# RastoBot-r1.net
KiCad netlist of a schematic drawn in EAGLE
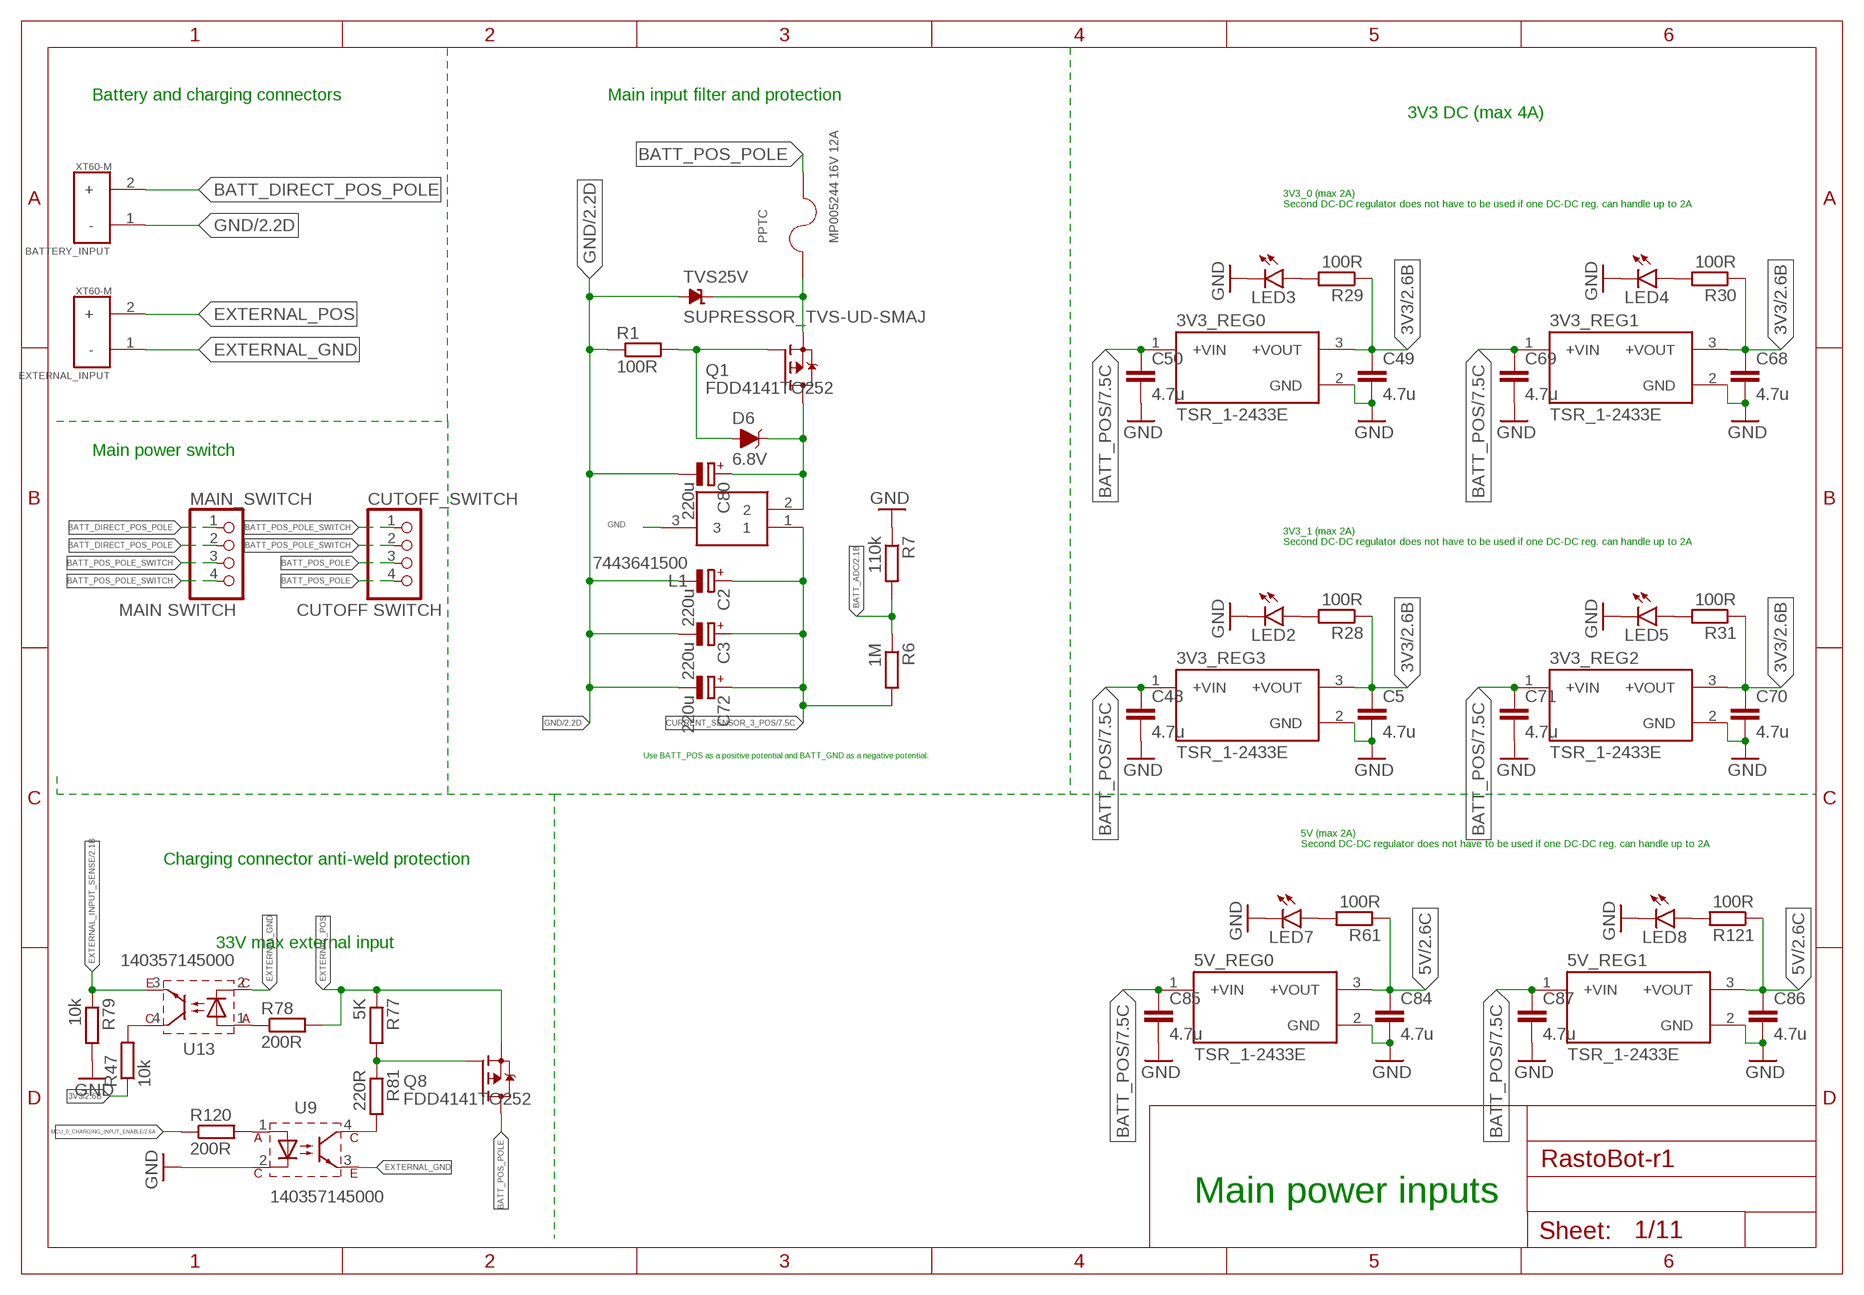
[diagram p0: schematic, sheet 1]
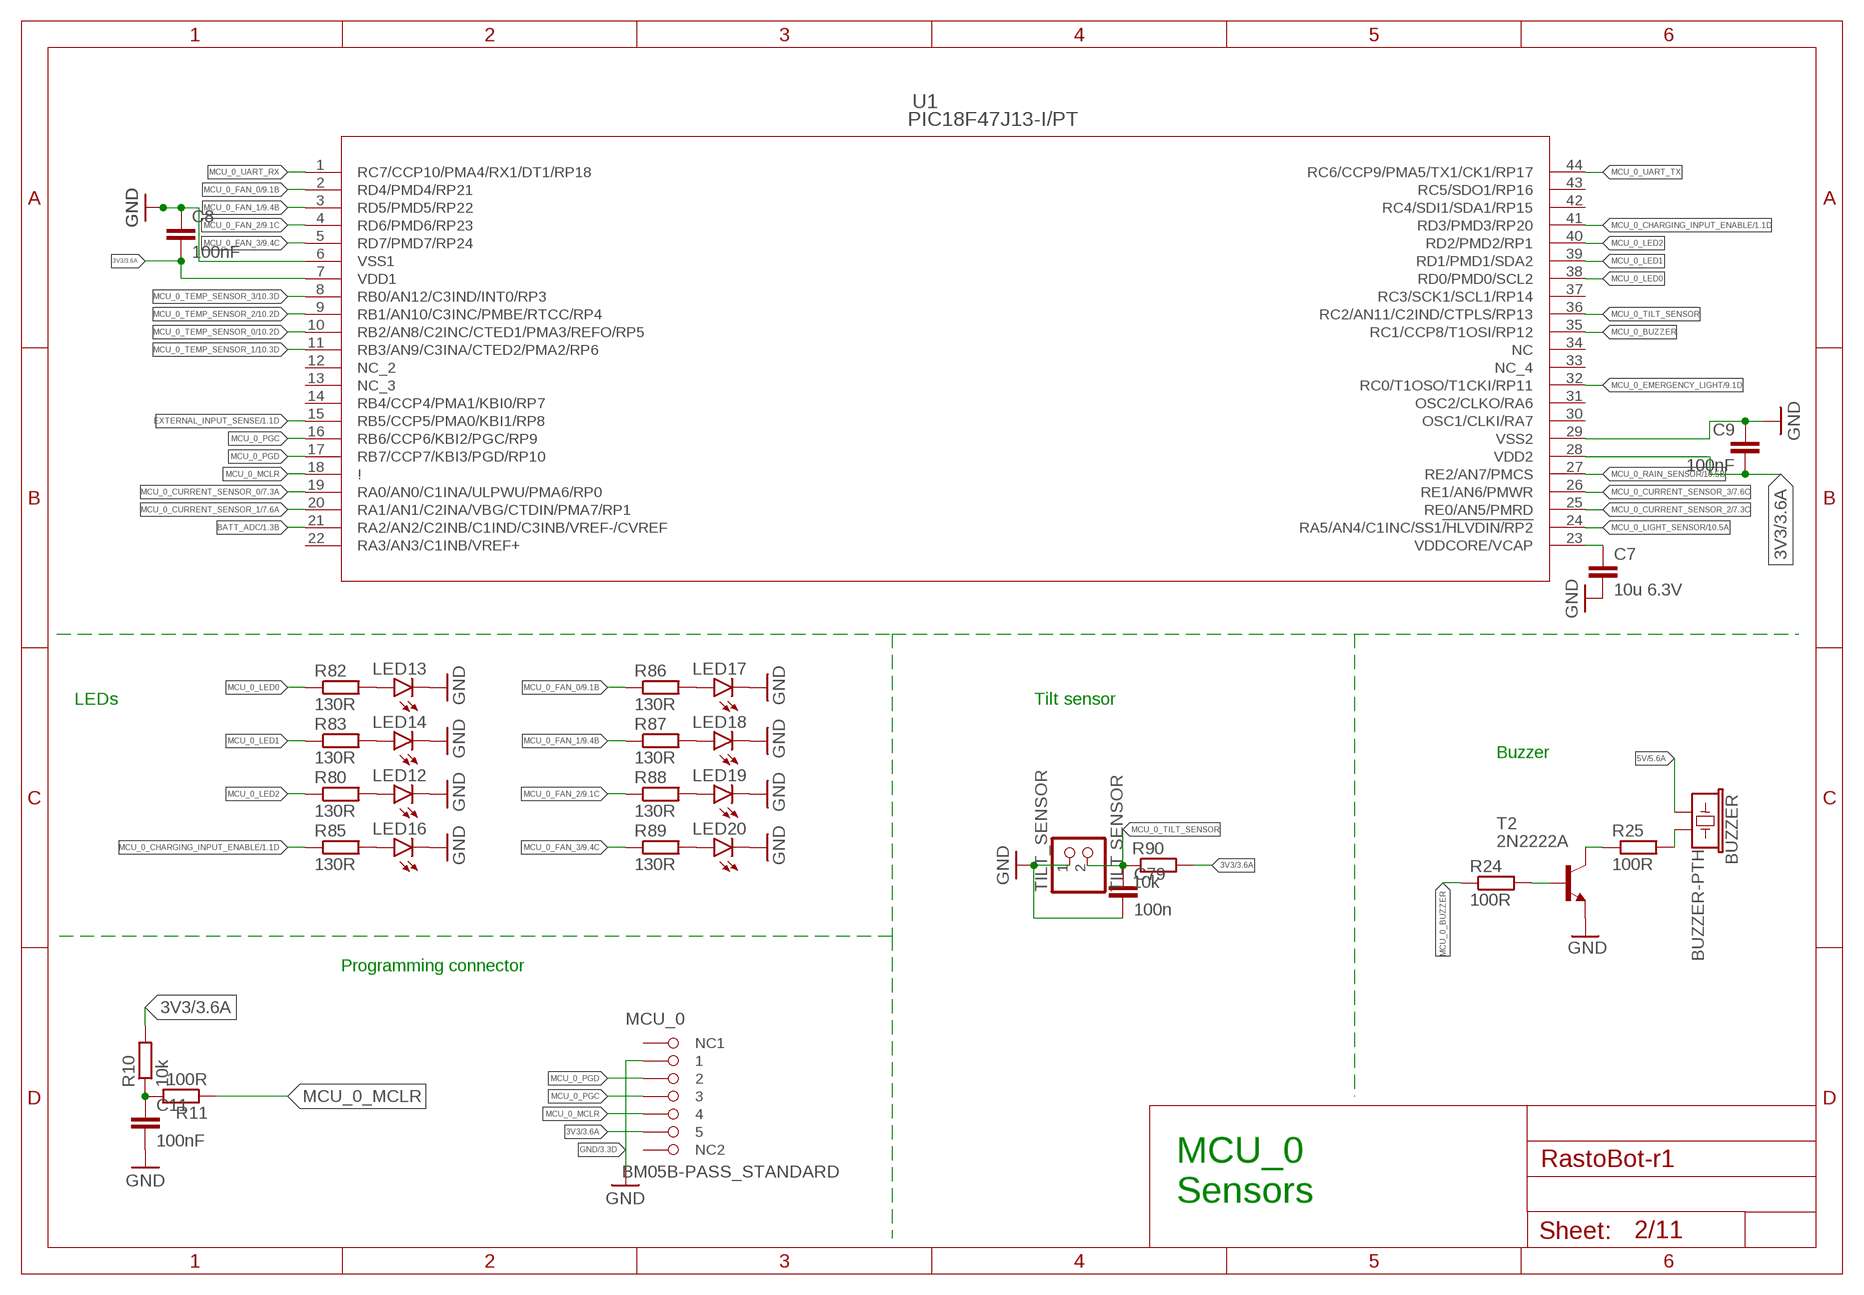
[diagram p1: schematic, sheet 2]
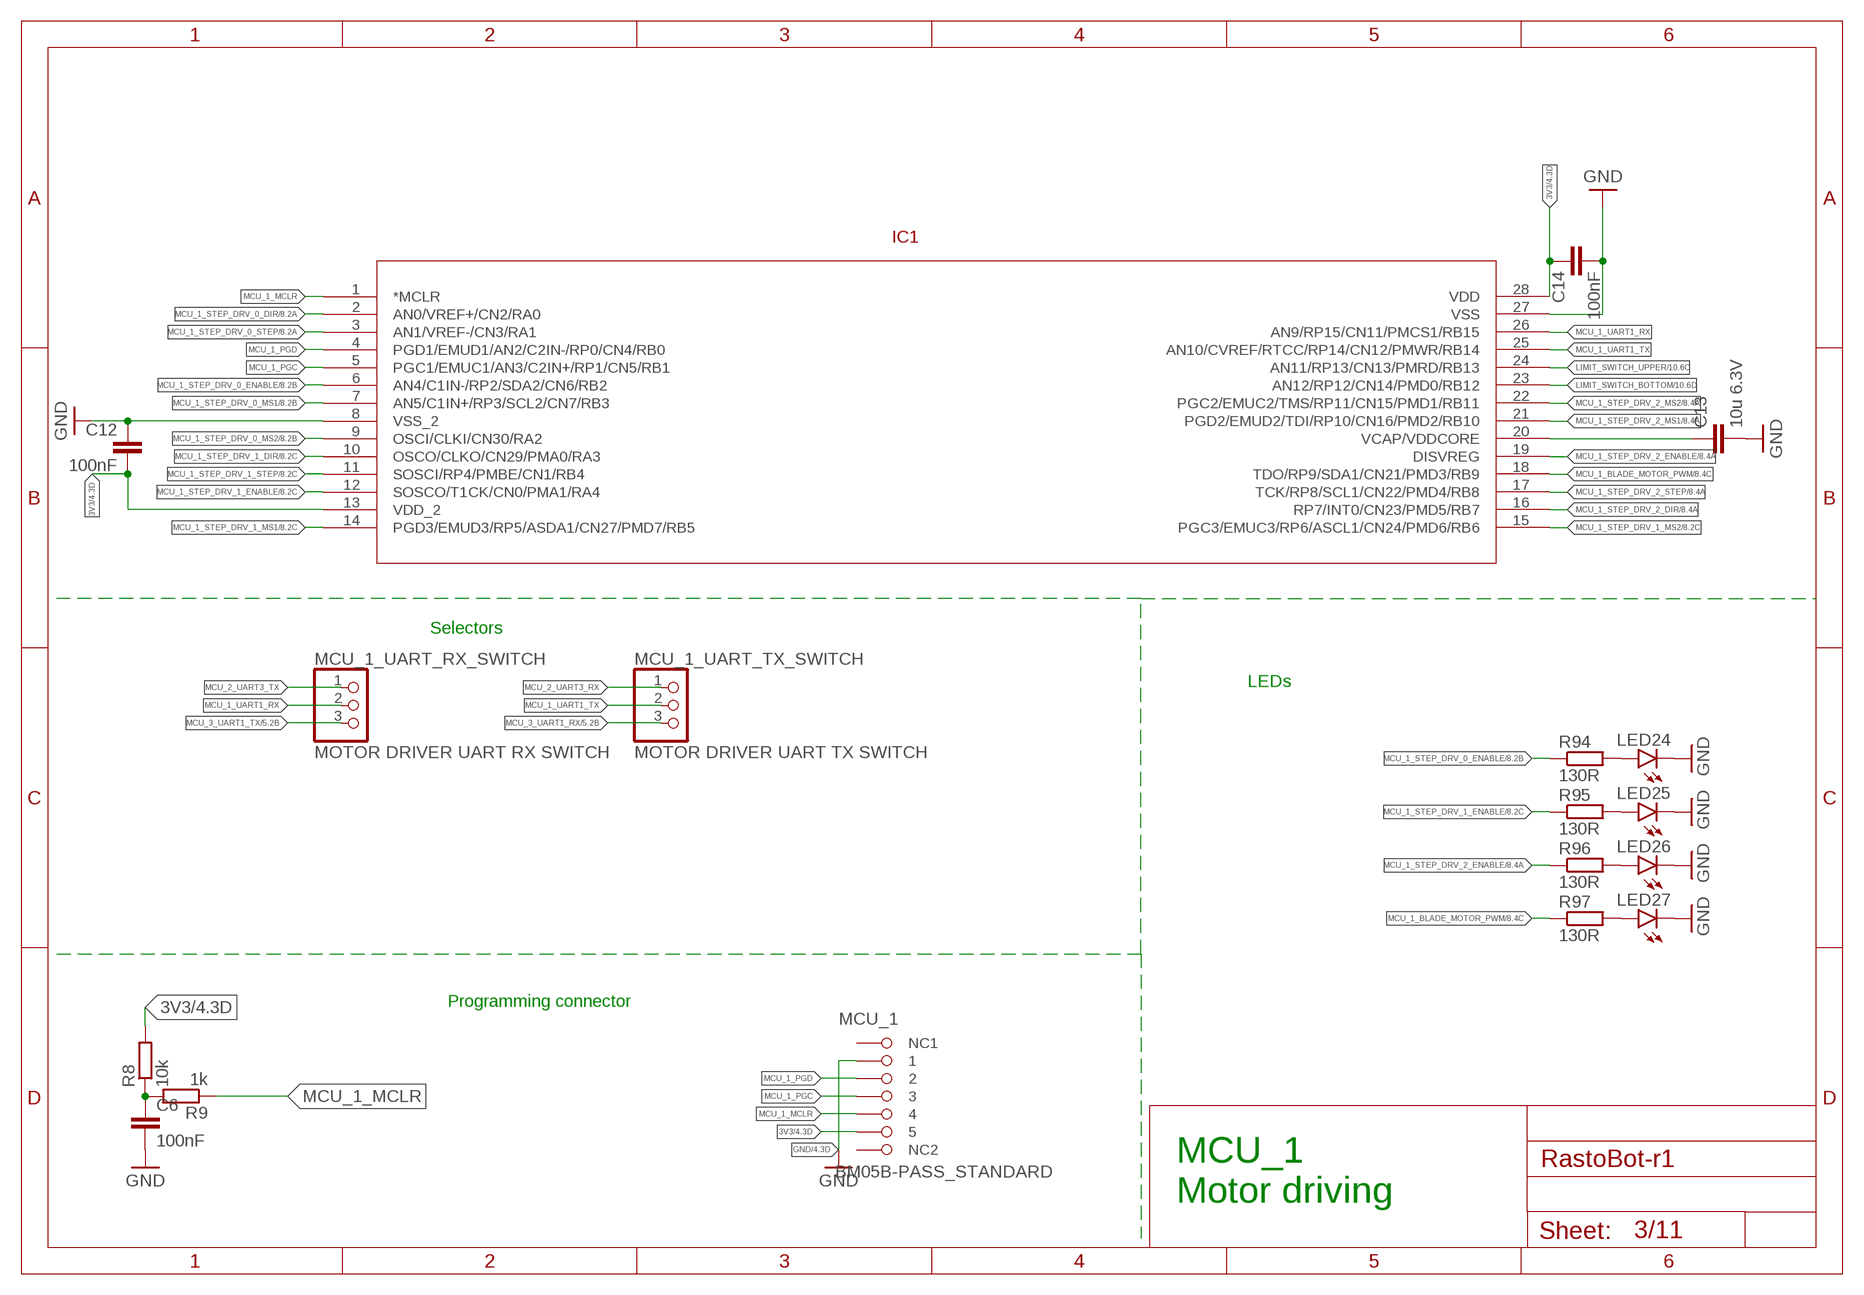
[diagram p2: schematic, sheet 3]
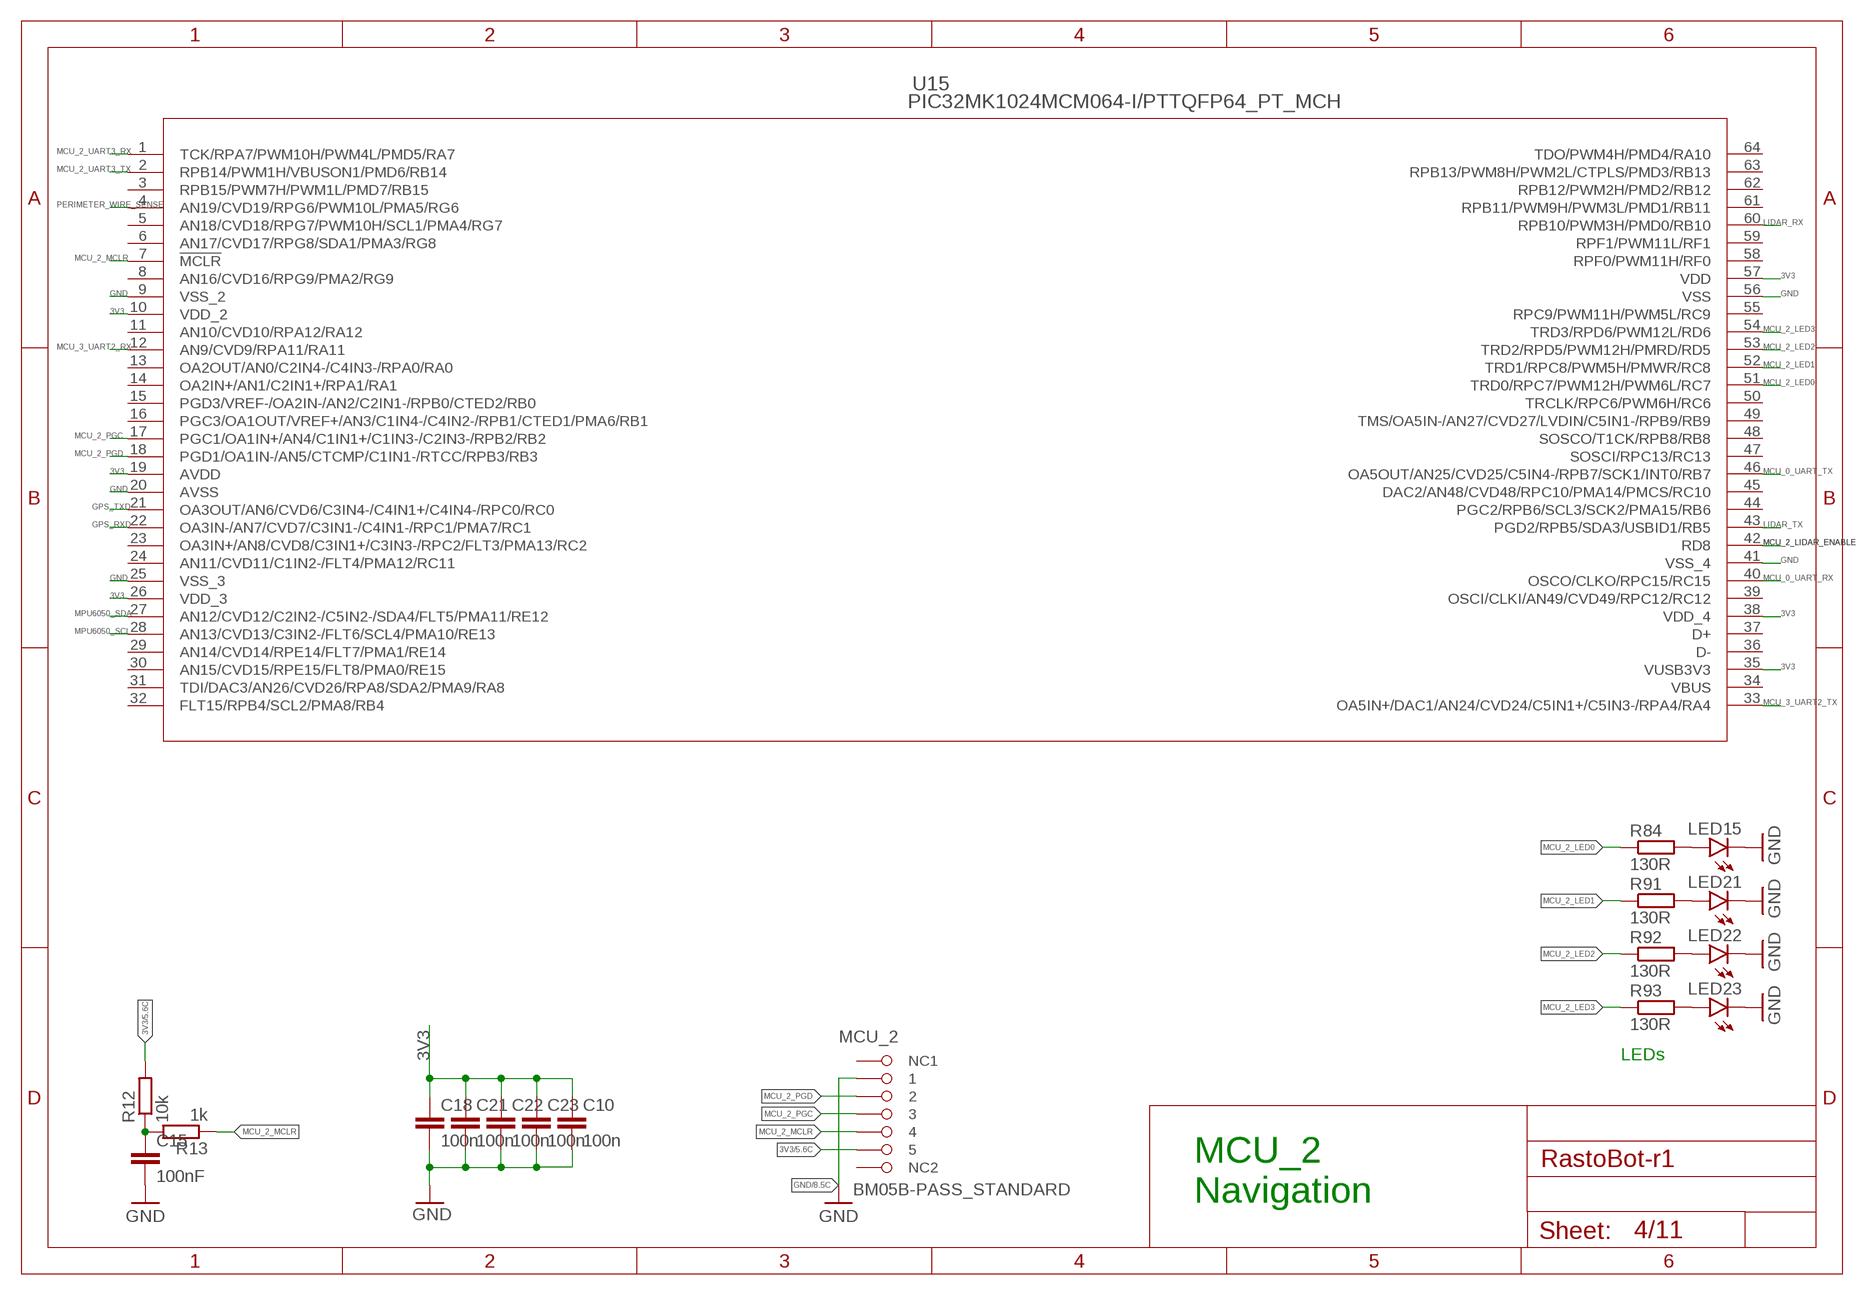
[diagram p3: schematic, sheet 4]
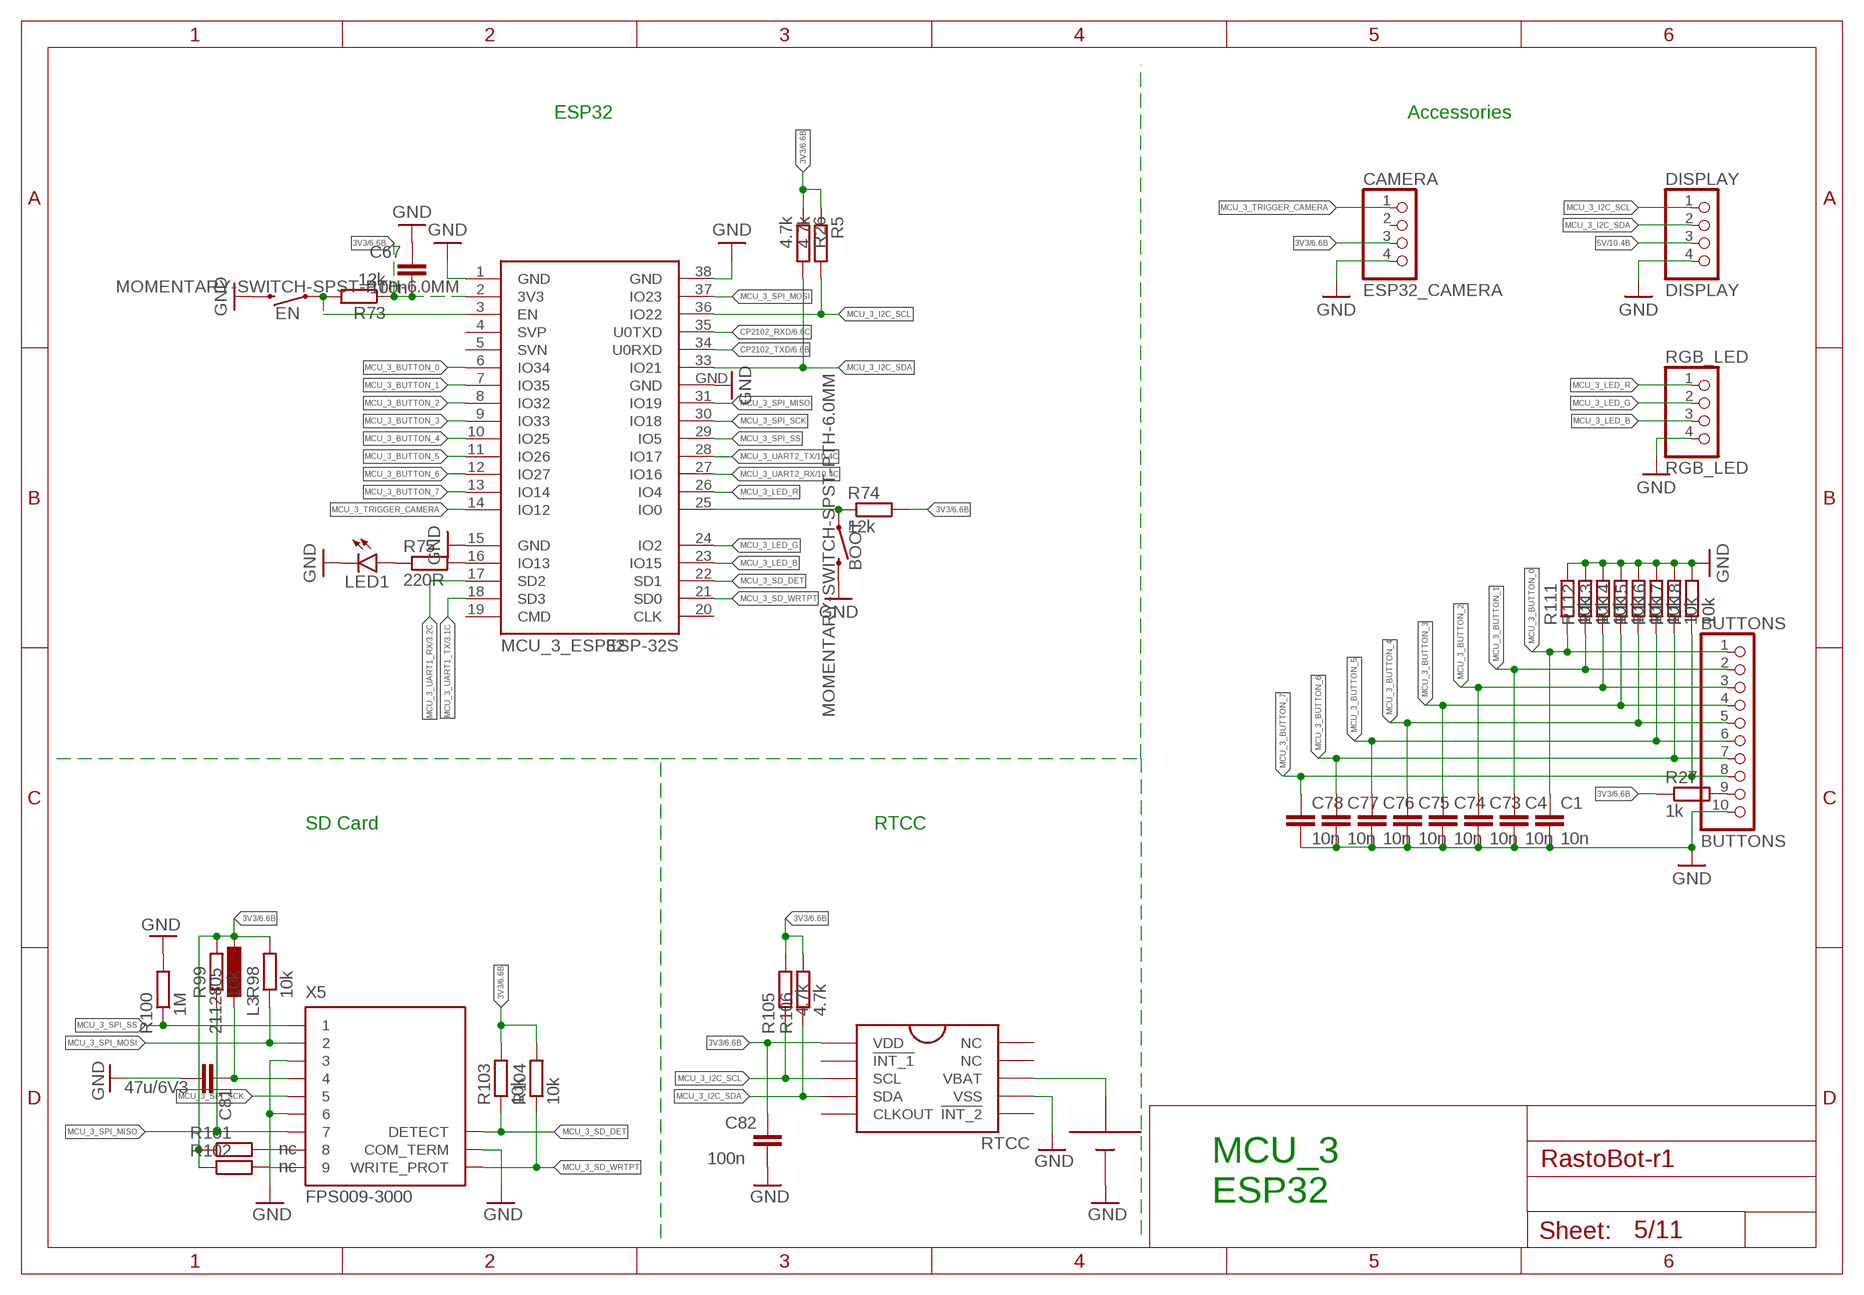
[diagram p4: schematic, sheet 5]
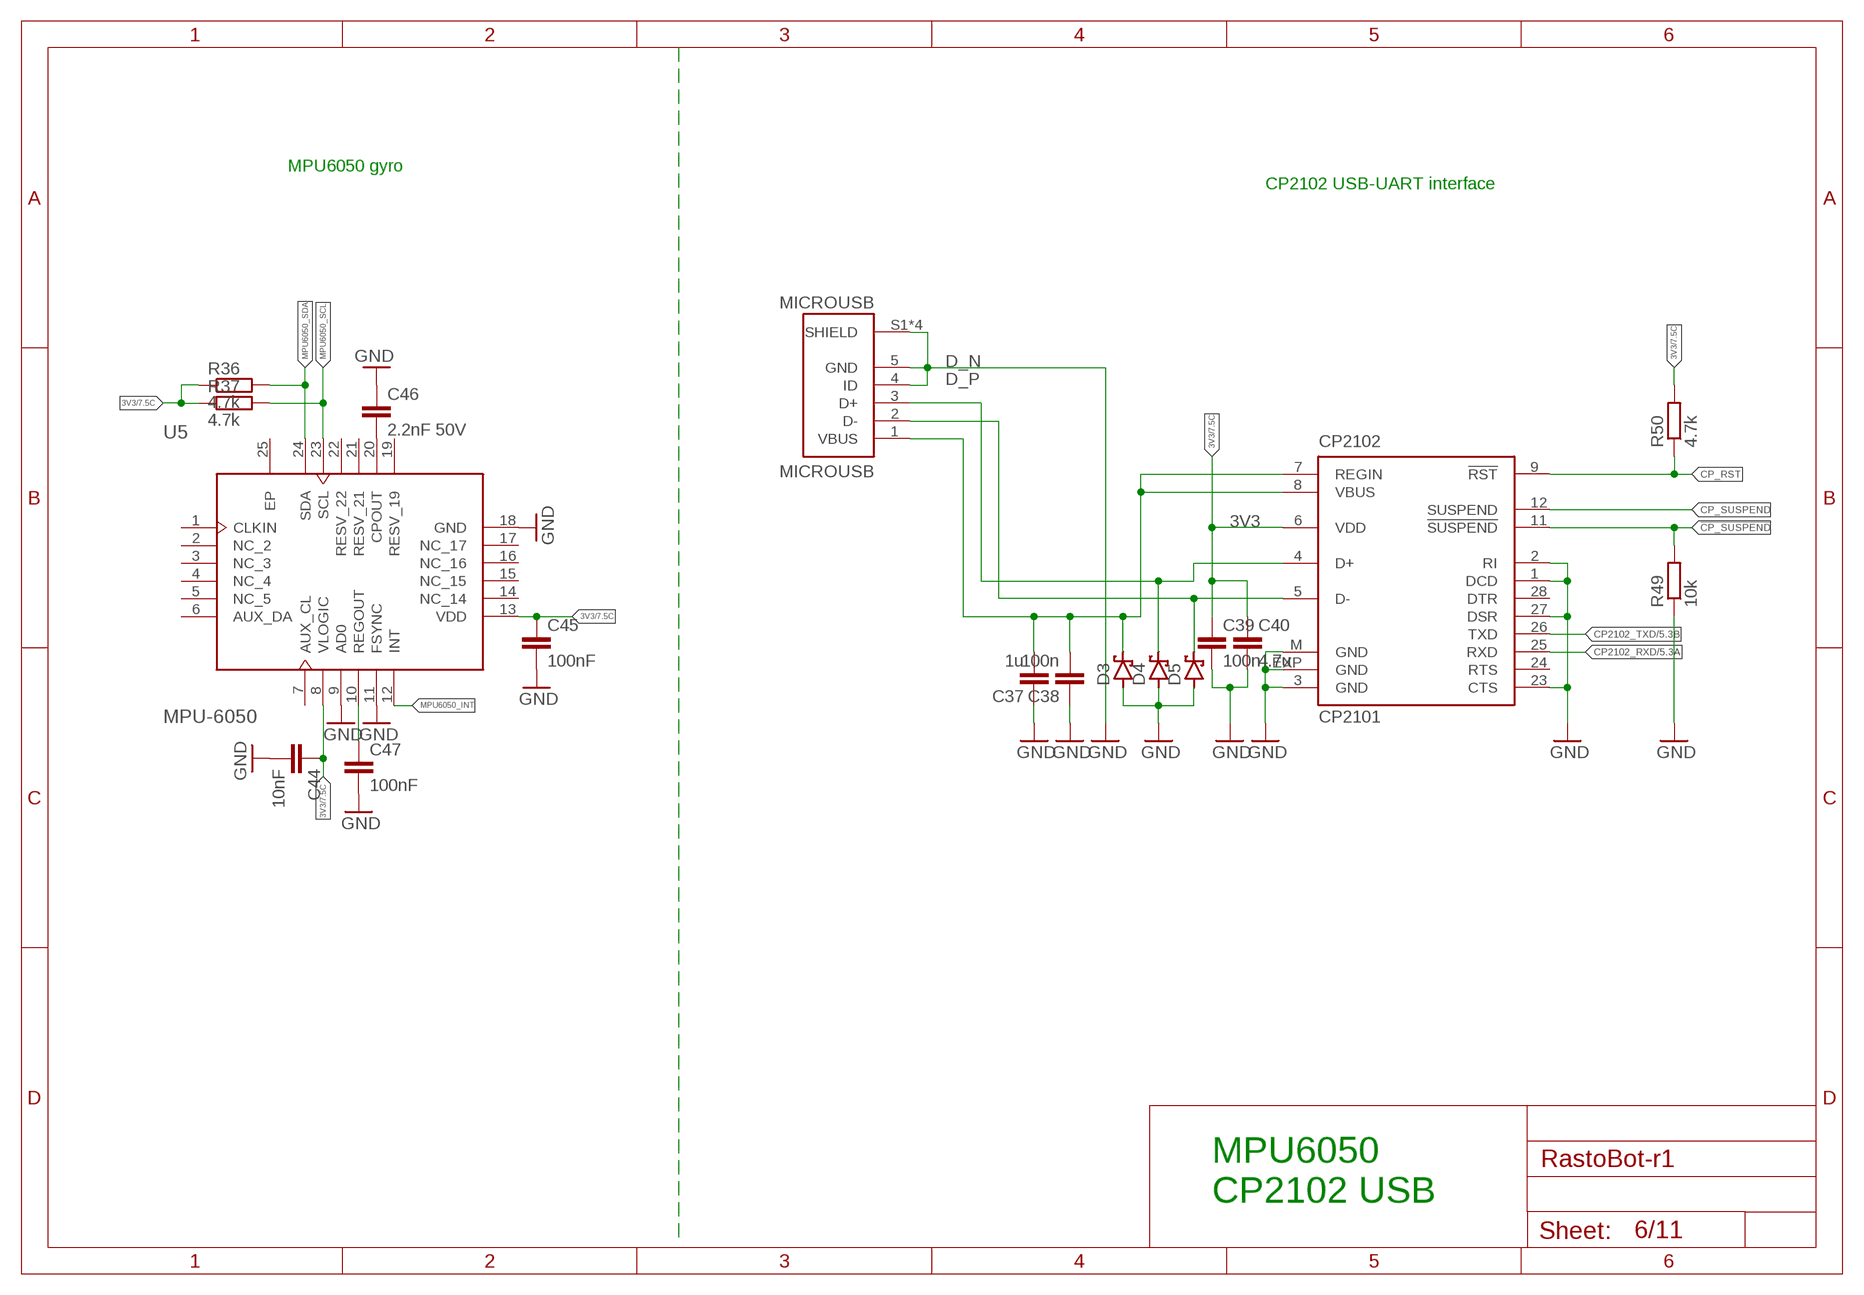
[diagram p5: schematic, sheet 6]
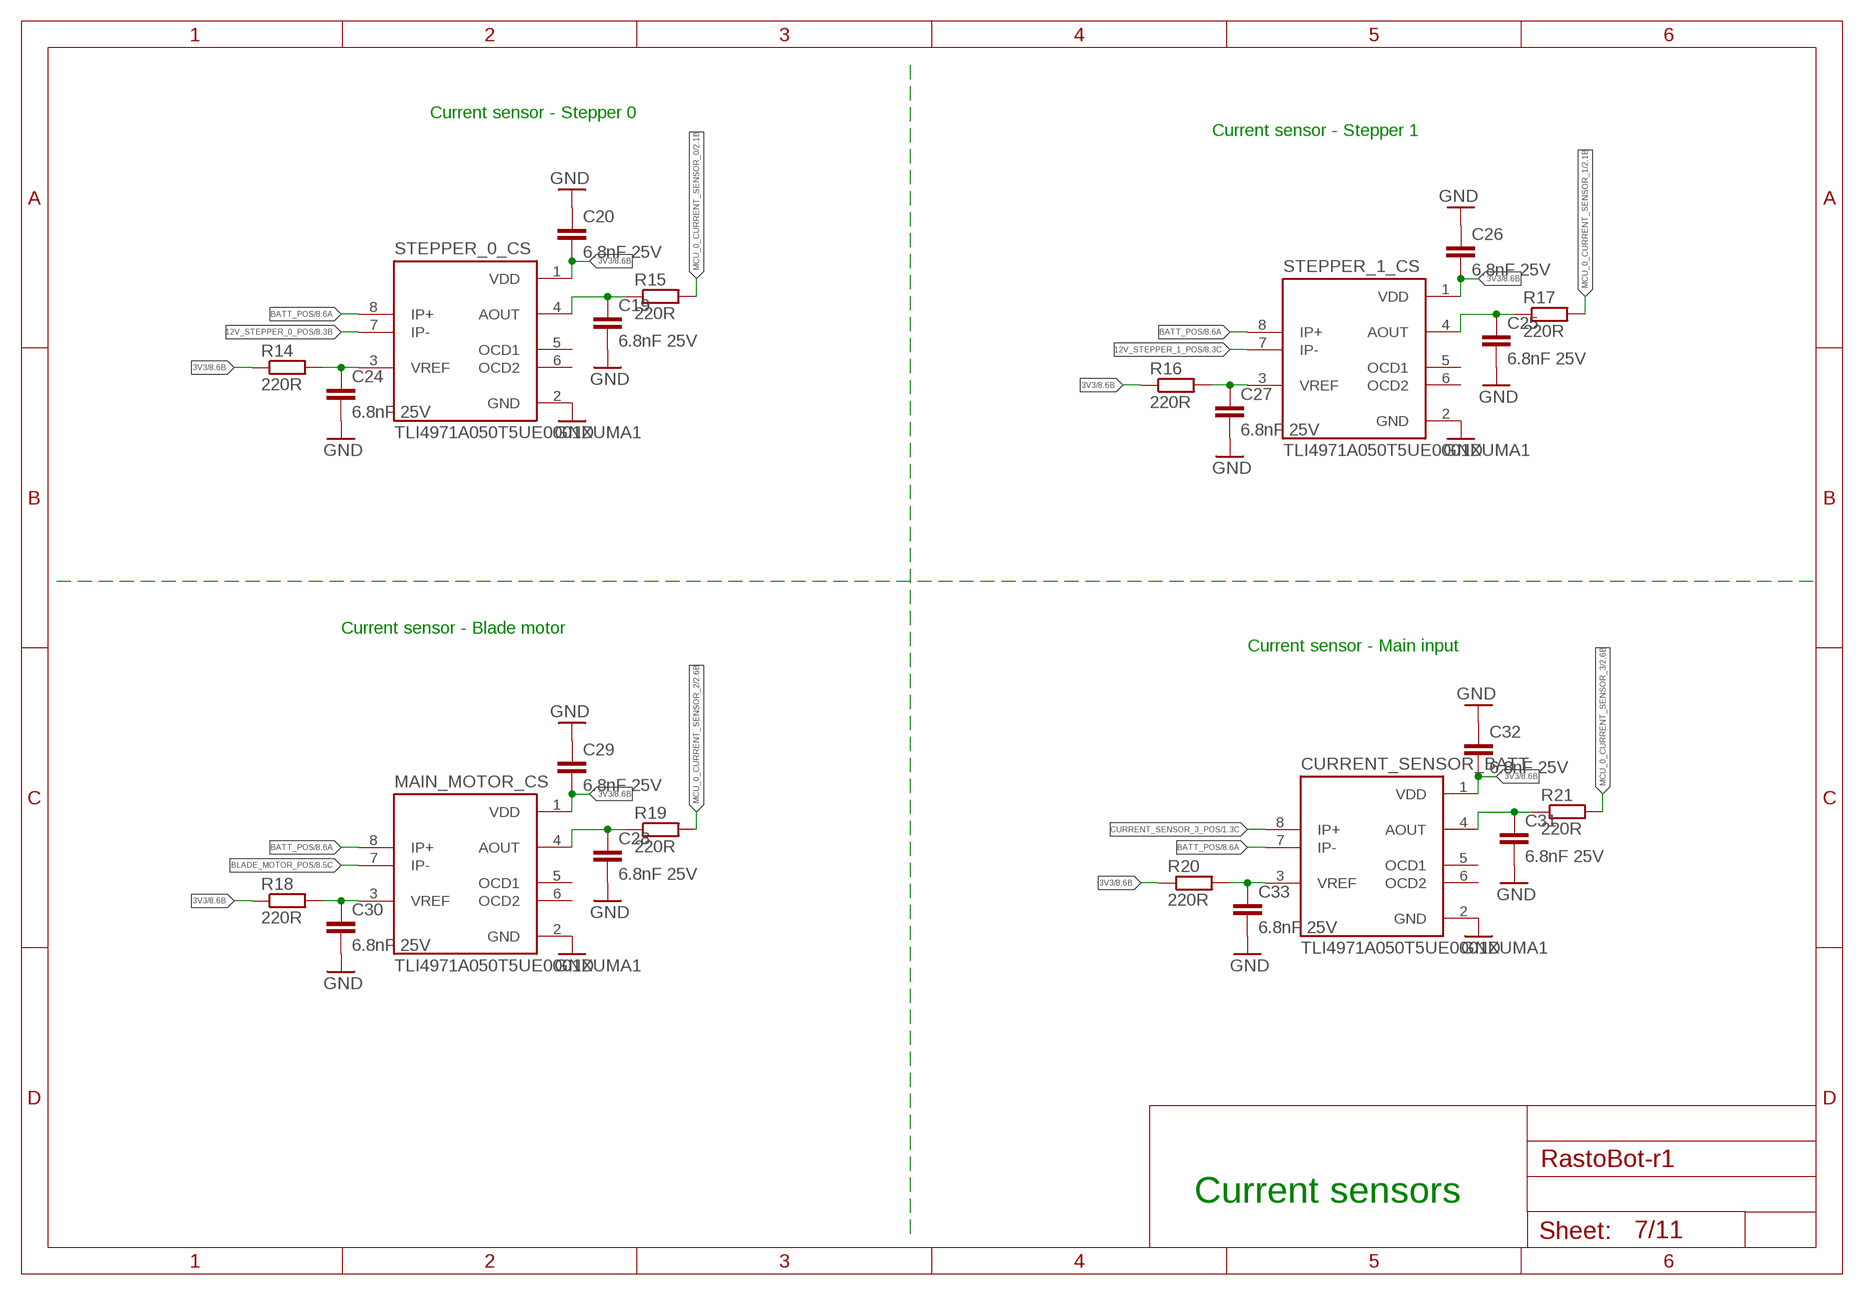
[diagram p6: schematic, sheet 7]
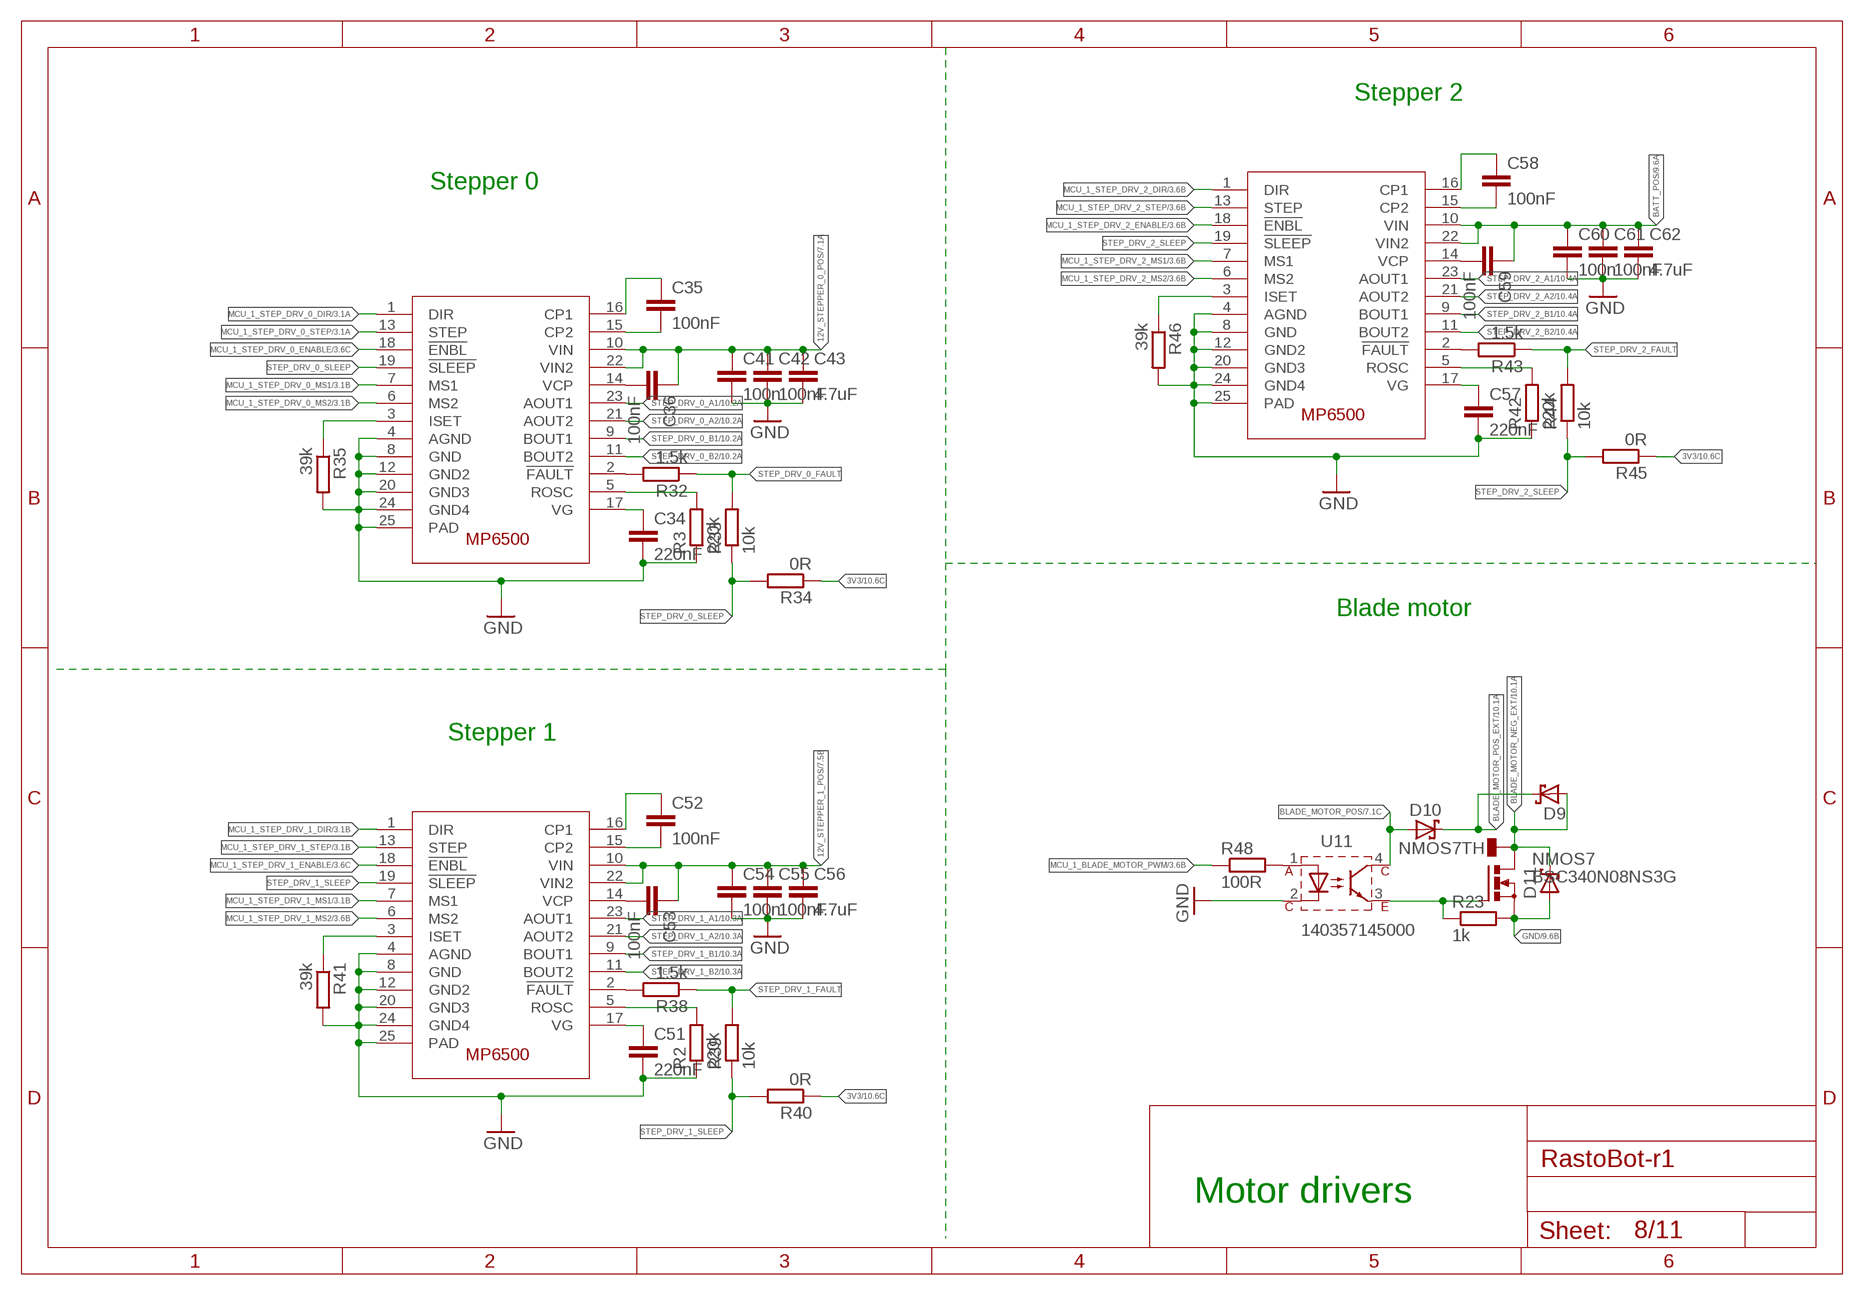
[diagram p7: schematic, sheet 8]
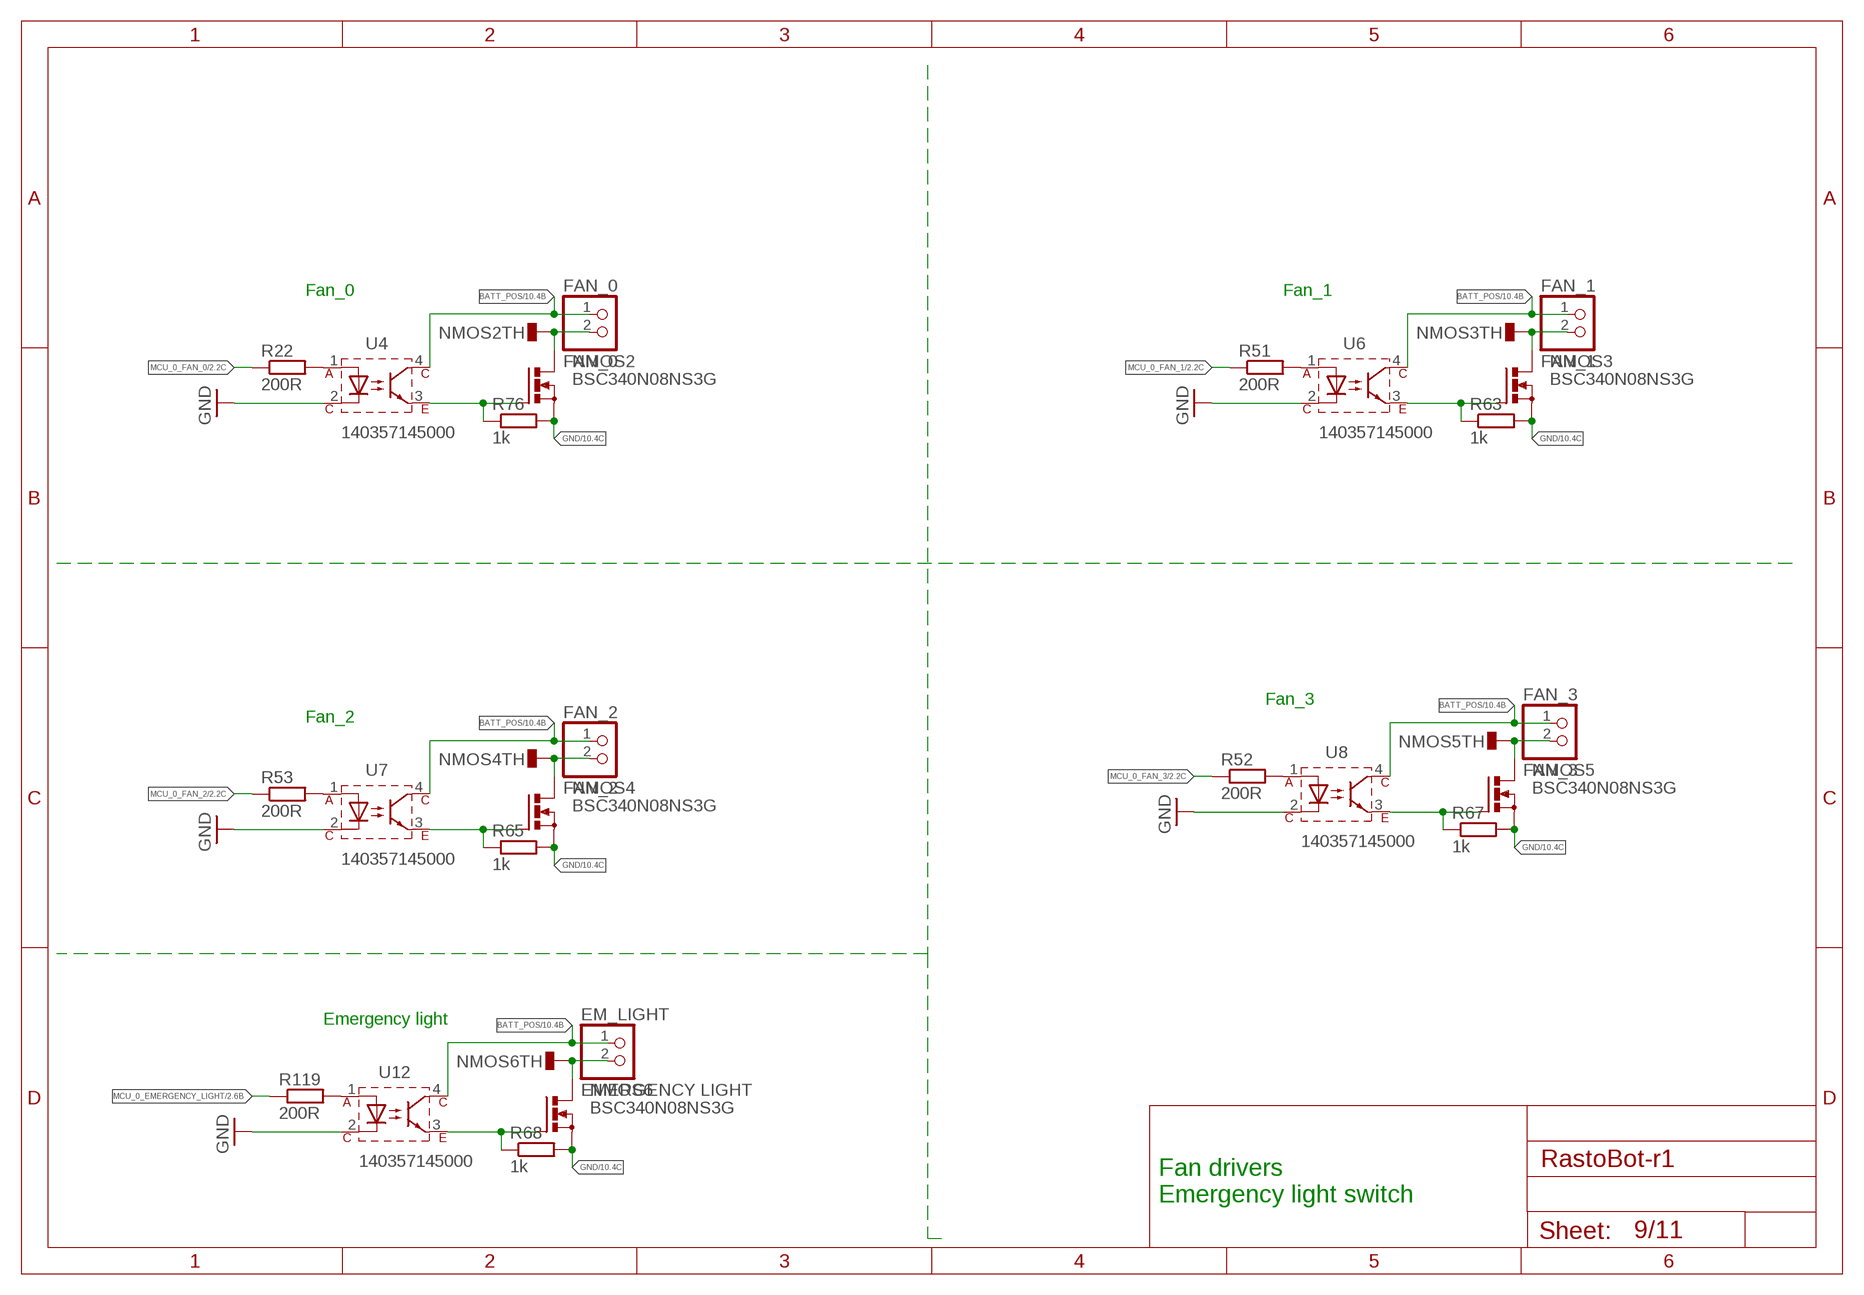
[diagram p8: schematic, sheet 9]
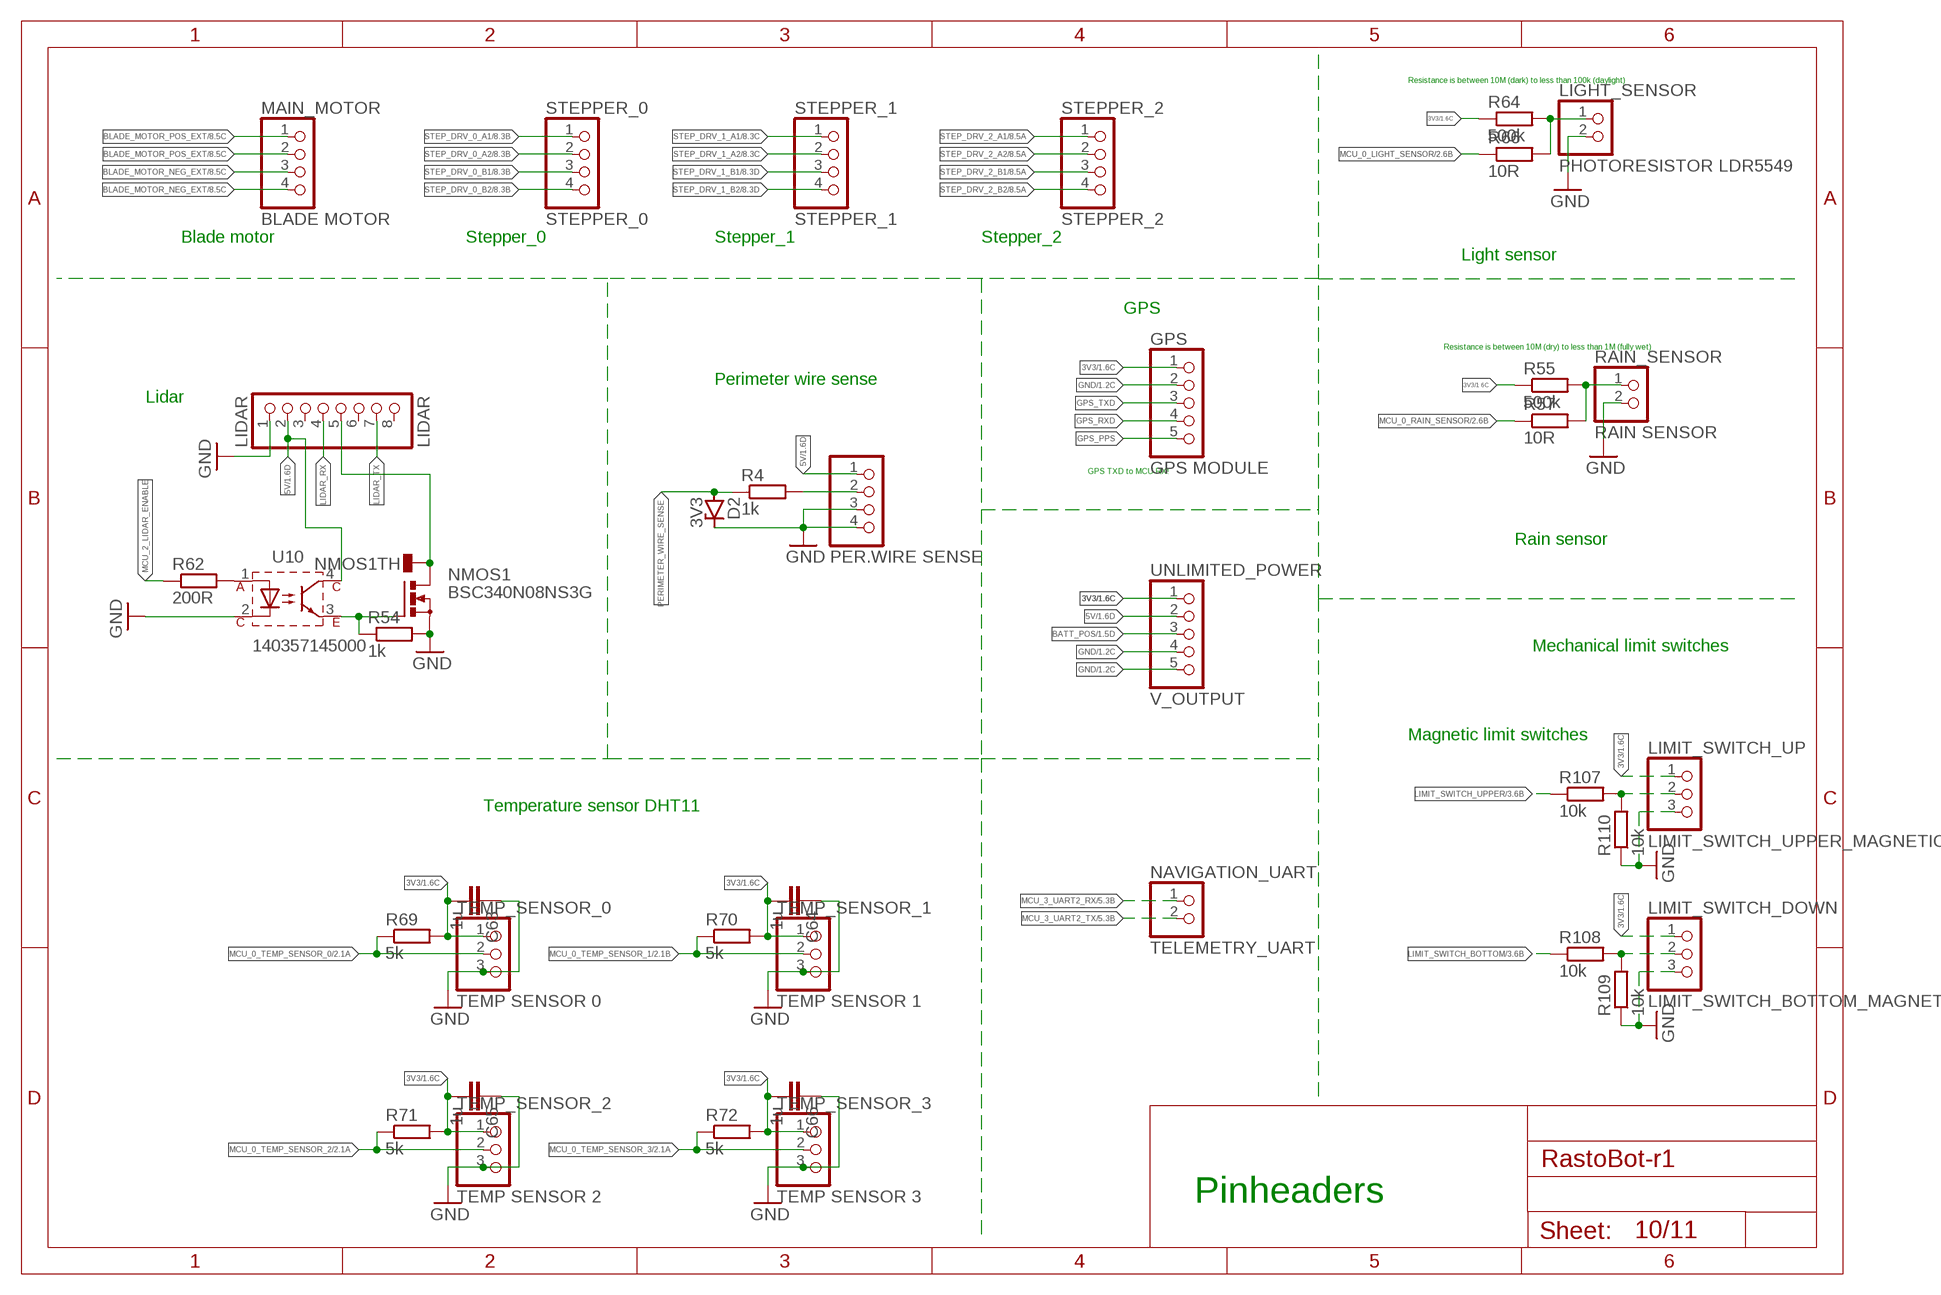
[diagram p9: schematic, sheet 10]
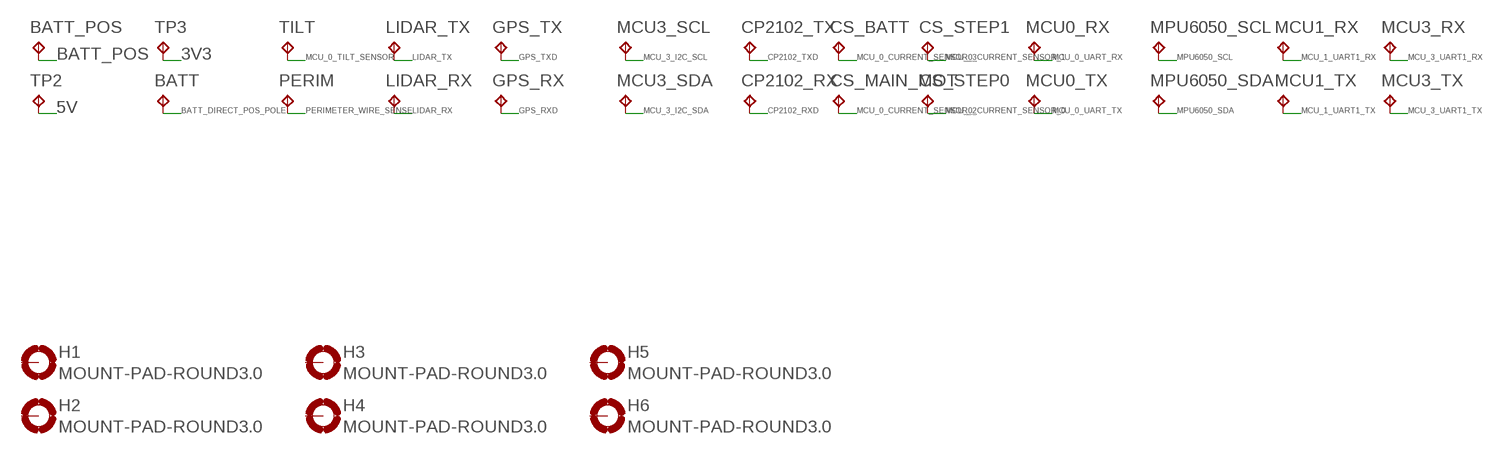
[diagram p10: schematic, sheet 11]

(export (version "E")
  (design (tool "Eeschema 10.0.6"))
  (components
    (comp (ref "BATT")
      (value "TPB1,27")
      (footprint "eagle-import:B1,27")
      (libsource (lib "eagle-import") (part "TPB1,27"))
    )
    (comp (ref "BATT_POS")
      (value "TPB1,27")
      (footprint "eagle-import:B1,27")
      (libsource (lib "eagle-import") (part "TPB1,27"))
    )
    (comp (ref "CP2102_RX")
      (value "TPB1,27")
      (footprint "eagle-import:B1,27")
      (libsource (lib "eagle-import") (part "TPB1,27"))
    )
    (comp (ref "CP2102_TX")
      (value "TPB1,27")
      (footprint "eagle-import:B1,27")
      (libsource (lib "eagle-import") (part "TPB1,27"))
    )
    (comp (ref "CS_BATT")
      (value "TPB1,27")
      (footprint "eagle-import:B1,27")
      (libsource (lib "eagle-import") (part "TPB1,27"))
    )
    (comp (ref "CS_MAIN_MOT")
      (value "TPB1,27")
      (footprint "eagle-import:B1,27")
      (libsource (lib "eagle-import") (part "TPB1,27"))
    )
    (comp (ref "CS_STEP0")
      (value "TPB1,27")
      (footprint "eagle-import:B1,27")
      (libsource (lib "eagle-import") (part "TPB1,27"))
    )
    (comp (ref "CS_STEP1")
      (value "TPB1,27")
      (footprint "eagle-import:B1,27")
      (libsource (lib "eagle-import") (part "TPB1,27"))
    )
    (comp (ref "GPS_RX")
      (value "TPB1,27")
      (footprint "eagle-import:B1,27")
      (libsource (lib "eagle-import") (part "TPB1,27"))
    )
    (comp (ref "GPS_TX")
      (value "TPB1,27")
      (footprint "eagle-import:B1,27")
      (libsource (lib "eagle-import") (part "TPB1,27"))
    )
    (comp (ref "H1")
      (value "MOUNT-PAD-ROUND3.0")
      (footprint "eagle-import:3,0-PAD")
      (libsource (lib "eagle-import") (part "MOUNT-PAD-ROUND3.0"))
    )
    (comp (ref "H2")
      (value "MOUNT-PAD-ROUND3.0")
      (footprint "eagle-import:3,0-PAD")
      (libsource (lib "eagle-import") (part "MOUNT-PAD-ROUND3.0"))
    )
    (comp (ref "H3")
      (value "MOUNT-PAD-ROUND3.0")
      (footprint "eagle-import:3,0-PAD")
      (libsource (lib "eagle-import") (part "MOUNT-PAD-ROUND3.0"))
    )
    (comp (ref "H4")
      (value "MOUNT-PAD-ROUND3.0")
      (footprint "eagle-import:3,0-PAD")
      (libsource (lib "eagle-import") (part "MOUNT-PAD-ROUND3.0"))
    )
    (comp (ref "H5")
      (value "MOUNT-PAD-ROUND3.0")
      (footprint "eagle-import:3,0-PAD")
      (libsource (lib "eagle-import") (part "MOUNT-PAD-ROUND3.0"))
    )
    (comp (ref "H6")
      (value "MOUNT-PAD-ROUND3.0")
      (footprint "eagle-import:3,0-PAD")
      (libsource (lib "eagle-import") (part "MOUNT-PAD-ROUND3.0"))
    )
    (comp (ref "LIDAR_RX")
      (value "TPB1,27")
      (footprint "eagle-import:B1,27")
      (libsource (lib "eagle-import") (part "TPB1,27"))
    )
    (comp (ref "LIDAR_TX")
      (value "TPB1,27")
      (footprint "eagle-import:B1,27")
      (libsource (lib "eagle-import") (part "TPB1,27"))
    )
    (comp (ref "MCU0_RX")
      (value "TPB1,27")
      (footprint "eagle-import:B1,27")
      (libsource (lib "eagle-import") (part "TPB1,27"))
    )
    (comp (ref "MCU0_TX")
      (value "TPB1,27")
      (footprint "eagle-import:B1,27")
      (libsource (lib "eagle-import") (part "TPB1,27"))
    )
    (comp (ref "MCU1_RX")
      (value "TPB1,27")
      (footprint "eagle-import:B1,27")
      (libsource (lib "eagle-import") (part "TPB1,27"))
    )
    (comp (ref "MCU1_TX")
      (value "TPB1,27")
      (footprint "eagle-import:B1,27")
      (libsource (lib "eagle-import") (part "TPB1,27"))
    )
    (comp (ref "MCU3_RX")
      (value "TPB1,27")
      (footprint "eagle-import:B1,27")
      (libsource (lib "eagle-import") (part "TPB1,27"))
    )
    (comp (ref "MCU3_SCL")
      (value "TPB1,27")
      (footprint "eagle-import:B1,27")
      (libsource (lib "eagle-import") (part "TPB1,27"))
    )
    (comp (ref "MCU3_SDA")
      (value "TPB1,27")
      (footprint "eagle-import:B1,27")
      (libsource (lib "eagle-import") (part "TPB1,27"))
    )
    (comp (ref "MCU3_TX")
      (value "TPB1,27")
      (footprint "eagle-import:B1,27")
      (libsource (lib "eagle-import") (part "TPB1,27"))
    )
    (comp (ref "MPU6050_SCL")
      (value "TPB1,27")
      (footprint "eagle-import:B1,27")
      (libsource (lib "eagle-import") (part "TPB1,27"))
    )
    (comp (ref "MPU6050_SDA")
      (value "TPB1,27")
      (footprint "eagle-import:B1,27")
      (libsource (lib "eagle-import") (part "TPB1,27"))
    )
    (comp (ref "PERIM")
      (value "TPB1,27")
      (footprint "eagle-import:B1,27")
      (libsource (lib "eagle-import") (part "TPB1,27"))
    )
    (comp (ref "TILT")
      (value "TPB1,27")
      (footprint "eagle-import:B1,27")
      (libsource (lib "eagle-import") (part "TPB1,27"))
    )
    (comp (ref "TP2")
      (value "TPB1,27")
      (footprint "eagle-import:B1,27")
      (libsource (lib "eagle-import") (part "TPB1,27"))
    )
    (comp (ref "TP3")
      (value "TPB1,27")
      (footprint "eagle-import:B1,27")
      (libsource (lib "eagle-import") (part "TPB1,27"))
    )
    (comp (ref "C34")
      (value "220nF")
      (footprint "eagle-import:C0603")
      (libsource (lib "eagle-import") (part "rcl_334_C-EUC0603"))
    )
    (comp (ref "C35")
      (value "100nF")
      (footprint "eagle-import:C0603")
      (libsource (lib "eagle-import") (part "rcl_334_C-EUC0603"))
    )
    (comp (ref "C36")
      (value "100nF")
      (footprint "eagle-import:C0603")
      (libsource (lib "eagle-import") (part "rcl_334_C-EUC0603"))
    )
    (comp (ref "C41")
      (value "100n")
      (footprint "eagle-import:C0603")
      (libsource (lib "eagle-import") (part "rcl_334_C-EUC0603"))
    )
    (comp (ref "C42")
      (value "100nF")
      (footprint "eagle-import:C0603")
      (libsource (lib "eagle-import") (part "rcl_334_C-EUC0603"))
    )
    (comp (ref "C43")
      (value "4.7uF")
      (footprint "eagle-import:C0603")
      (libsource (lib "eagle-import") (part "rcl_334_C-EUC0603"))
    )
    (comp (ref "C51")
      (value "220nF")
      (footprint "eagle-import:C0603")
      (libsource (lib "eagle-import") (part "rcl_334_C-EUC0603"))
    )
    (comp (ref "C52")
      (value "100nF")
      (footprint "eagle-import:C0603")
      (libsource (lib "eagle-import") (part "rcl_334_C-EUC0603"))
    )
    (comp (ref "C53")
      (value "100nF")
      (footprint "eagle-import:C0603")
      (libsource (lib "eagle-import") (part "rcl_334_C-EUC0603"))
    )
    (comp (ref "C54")
      (value "100n")
      (footprint "eagle-import:C0603")
      (libsource (lib "eagle-import") (part "rcl_334_C-EUC0603"))
    )
    (comp (ref "C55")
      (value "100nF")
      (footprint "eagle-import:C0603")
      (libsource (lib "eagle-import") (part "rcl_334_C-EUC0603"))
    )
    (comp (ref "C56")
      (value "4.7uF")
      (footprint "eagle-import:C0603")
      (libsource (lib "eagle-import") (part "rcl_334_C-EUC0603"))
    )
    (comp (ref "C57")
      (value "220nF")
      (footprint "eagle-import:C0603")
      (libsource (lib "eagle-import") (part "rcl_334_C-EUC0603"))
    )
    (comp (ref "C58")
      (value "100nF")
      (footprint "eagle-import:C0603")
      (libsource (lib "eagle-import") (part "rcl_334_C-EUC0603"))
    )
    (comp (ref "C59")
      (value "100nF")
      (footprint "eagle-import:C0603")
      (libsource (lib "eagle-import") (part "rcl_334_C-EUC0603"))
    )
    (comp (ref "C60")
      (value "100n")
      (footprint "eagle-import:C0603")
      (libsource (lib "eagle-import") (part "rcl_334_C-EUC0603"))
    )
    (comp (ref "C61")
      (value "100nF")
      (footprint "eagle-import:C0603")
      (libsource (lib "eagle-import") (part "rcl_334_C-EUC0603"))
    )
    (comp (ref "C62")
      (value "4.7uF")
      (footprint "eagle-import:C0603")
      (libsource (lib "eagle-import") (part "rcl_334_C-EUC0603"))
    )
    (comp (ref "D9")
      (value "SCHOTTKY-DIODEAG")
      (footprint "eagle-import:AG")
      (libsource (lib "eagle-import") (part "SCHOTTKY-DIODEAG"))
    )
    (comp (ref "D10")
      (value "SCHOTTKY-DIODEAG")
      (footprint "eagle-import:AG")
      (libsource (lib "eagle-import") (part "SCHOTTKY-DIODEAG"))
    )
    (comp (ref "D11")
      (value "SCHOTTKY-DIODEAG")
      (footprint "eagle-import:AG")
      (libsource (lib "eagle-import") (part "SCHOTTKY-DIODEAG"))
    )
    (comp (ref "NMOS7")
      (value "BSC340N08NS3G")
      (footprint "eagle-import:PG-TDSON-8")
      (libsource (lib "eagle-import") (part "BSC340N08NS3G"))
    )
    (comp (ref "R2")
      (value "220k")
      (footprint "eagle-import:R0603")
      (libsource (lib "eagle-import") (part "rcl_334_R-EU_R0603"))
    )
    (comp (ref "R3")
      (value "220k")
      (footprint "eagle-import:R0603")
      (libsource (lib "eagle-import") (part "rcl_334_R-EU_R0603"))
    )
    (comp (ref "R23")
      (value "1k")
      (footprint "eagle-import:R0805")
      (libsource (lib "eagle-import") (part "rcl_334_R-EU_R0805"))
    )
    (comp (ref "R32")
      (value "1.5k")
      (footprint "eagle-import:R0603")
      (libsource (lib "eagle-import") (part "rcl_334_R-EU_R0603"))
    )
    (comp (ref "R33")
      (value "10k")
      (footprint "eagle-import:R0603")
      (libsource (lib "eagle-import") (part "rcl_334_R-EU_R0603"))
    )
    (comp (ref "R34")
      (value "0R")
      (footprint "eagle-import:R0603")
      (libsource (lib "eagle-import") (part "rcl_334_R-EU_R0603"))
    )
    (comp (ref "R35")
      (value "39k")
      (footprint "eagle-import:R0603")
      (libsource (lib "eagle-import") (part "rcl_334_R-EU_R0603"))
    )
    (comp (ref "R38")
      (value "1.5k")
      (footprint "eagle-import:R0603")
      (libsource (lib "eagle-import") (part "rcl_334_R-EU_R0603"))
    )
    (comp (ref "R39")
      (value "10k")
      (footprint "eagle-import:R0603")
      (libsource (lib "eagle-import") (part "rcl_334_R-EU_R0603"))
    )
    (comp (ref "R40")
      (value "0R")
      (footprint "eagle-import:R0603")
      (libsource (lib "eagle-import") (part "rcl_334_R-EU_R0603"))
    )
    (comp (ref "R41")
      (value "39k")
      (footprint "eagle-import:R0603")
      (libsource (lib "eagle-import") (part "rcl_334_R-EU_R0603"))
    )
    (comp (ref "R42")
      (value "220k")
      (footprint "eagle-import:R0603")
      (libsource (lib "eagle-import") (part "rcl_334_R-EU_R0603"))
    )
    (comp (ref "R43")
      (value "1.5k")
      (footprint "eagle-import:R0603")
      (libsource (lib "eagle-import") (part "rcl_334_R-EU_R0603"))
    )
    (comp (ref "R44")
      (value "10k")
      (footprint "eagle-import:R0603")
      (libsource (lib "eagle-import") (part "rcl_334_R-EU_R0603"))
    )
    (comp (ref "R45")
      (value "0R")
      (footprint "eagle-import:R0603")
      (libsource (lib "eagle-import") (part "rcl_334_R-EU_R0603"))
    )
    (comp (ref "R46")
      (value "39k")
      (footprint "eagle-import:R0603")
      (libsource (lib "eagle-import") (part "rcl_334_R-EU_R0603"))
    )
    (comp (ref "R48")
      (value "100R")
      (footprint "eagle-import:R0805")
      (libsource (lib "eagle-import") (part "rcl_334_R-EU_R0805"))
    )
    (comp (ref "SD1")
      (value "MP6500")
      (footprint "eagle-import:QFN65P500X500X100-25N")
      (libsource (lib "eagle-import") (part "MP6500"))
    )
    (comp (ref "SD2")
      (value "MP6500")
      (footprint "eagle-import:QFN65P500X500X100-25N")
      (libsource (lib "eagle-import") (part "MP6500"))
    )
    (comp (ref "SD3")
      (value "MP6500")
      (footprint "eagle-import:QFN65P500X500X100-25N")
      (libsource (lib "eagle-import") (part "MP6500"))
    )
    (comp (ref "U11")
      (value "140357145000")
      (footprint "eagle-import:WL-OCPT_SOP4")
      (libsource (lib "eagle-import") (part "WL-OCPT_SERIES_357_140357145000"))
    )
    (comp (ref "C6")
      (value "100nF")
      (footprint "eagle-import:C0603")
      (libsource (lib "eagle-import") (part "rcl_334_C-EUC0603"))
    )
    (comp (ref "C12")
      (value "100nF")
      (footprint "eagle-import:C0603")
      (libsource (lib "eagle-import") (part "rcl_334_C-EUC0603"))
    )
    (comp (ref "C13")
      (value "10u 6.3V")
      (footprint "eagle-import:C1206")
      (libsource (lib "eagle-import") (part "rcl_334_C-EUC1206"))
    )
    (comp (ref "C14")
      (value "100nF")
      (footprint "eagle-import:C0603")
      (libsource (lib "eagle-import") (part "rcl_334_C-EUC0603"))
    )
    (comp (ref "IC1")
      (value "PIC24FJ32GA002-X")
      (footprint "eagle-import:SPDIP28_300MC")
      (libsource (lib "eagle-import") (part "PIC24FJ32GA002-X"))
    )
    (comp (ref "LED24")
      (value "LEDSML0805")
      (footprint "eagle-import:SML0805")
      (libsource (lib "eagle-import") (part "LEDSML0805"))
    )
    (comp (ref "LED25")
      (value "LEDSML0805")
      (footprint "eagle-import:SML0805")
      (libsource (lib "eagle-import") (part "LEDSML0805"))
    )
    (comp (ref "LED26")
      (value "LEDSML0805")
      (footprint "eagle-import:SML0805")
      (libsource (lib "eagle-import") (part "LEDSML0805"))
    )
    (comp (ref "LED27")
      (value "LEDSML0805")
      (footprint "eagle-import:SML0805")
      (libsource (lib "eagle-import") (part "LEDSML0805"))
    )
    (comp (ref "MCU_1")
      (value "BM05B-PASS_STANDARD")
      (footprint "eagle-import:BM05B-PASS")
      (libsource (lib "eagle-import") (part "BM05B-PASS_STANDARD"))
    )
    (comp (ref "MCU_1_UART_RX_SWITCH")
      (value "MOTOR DRIVER UART RX SWITCH")
      (footprint "eagle-import:1X03")
      (libsource (lib "eagle-import") (part "PINHD-1X3"))
    )
    (comp (ref "MCU_1_UART_TX_SWITCH")
      (value "MOTOR DRIVER UART TX SWITCH")
      (footprint "eagle-import:1X03")
      (libsource (lib "eagle-import") (part "PINHD-1X3"))
    )
    (comp (ref "R8")
      (value "10k")
      (footprint "eagle-import:R0805")
      (libsource (lib "eagle-import") (part "rcl_334_R-EU_R0805"))
    )
    (comp (ref "R9")
      (value "1k")
      (footprint "eagle-import:R0805")
      (libsource (lib "eagle-import") (part "rcl_334_R-EU_R0805"))
    )
    (comp (ref "R94")
      (value "130R")
      (footprint "eagle-import:R0603")
      (libsource (lib "eagle-import") (part "rcl_334_R-EU_R0603"))
    )
    (comp (ref "R95")
      (value "130R")
      (footprint "eagle-import:R0603")
      (libsource (lib "eagle-import") (part "rcl_334_R-EU_R0603"))
    )
    (comp (ref "R96")
      (value "130R")
      (footprint "eagle-import:R0603")
      (libsource (lib "eagle-import") (part "rcl_334_R-EU_R0603"))
    )
    (comp (ref "R97")
      (value "130R")
      (footprint "eagle-import:R0603")
      (libsource (lib "eagle-import") (part "rcl_334_R-EU_R0603"))
    )
    (comp (ref "3V3_REG0")
      (value "TSR_1-2433E")
      (footprint "eagle-import:CONV_TSR_1-2433E")
      (fields (field (name "MF") "Traco Power") (field (name "MP") "TSR 1-2433E"))
      (libsource (lib "eagle-import") (part "TSR_1-2433E"))
    )
    (comp (ref "3V3_REG1")
      (value "TSR_1-2433E")
      (footprint "eagle-import:CONV_TSR_1-2433E")
      (fields (field (name "MF") "Traco Power") (field (name "MP") "TSR 1-2433E"))
      (libsource (lib "eagle-import") (part "TSR_1-2433E"))
    )
    (comp (ref "3V3_REG2")
      (value "TSR_1-2433E")
      (footprint "eagle-import:CONV_TSR_1-2433E")
      (fields (field (name "MF") "Traco Power") (field (name "MP") "TSR 1-2433E"))
      (libsource (lib "eagle-import") (part "TSR_1-2433E"))
    )
    (comp (ref "3V3_REG3")
      (value "TSR_1-2433E")
      (footprint "eagle-import:CONV_TSR_1-2433E")
      (fields (field (name "MF") "Traco Power") (field (name "MP") "TSR 1-2433E"))
      (libsource (lib "eagle-import") (part "TSR_1-2433E"))
    )
    (comp (ref "5V_REG0")
      (value "TSR_1-2433E")
      (footprint "eagle-import:CONV_TSR_1-2433E")
      (fields (field (name "MF") "Traco Power") (field (name "MP") "TSR 1-2433E"))
      (libsource (lib "eagle-import") (part "TSR_1-2433E"))
    )
    (comp (ref "5V_REG1")
      (value "TSR_1-2433E")
      (footprint "eagle-import:CONV_TSR_1-2433E")
      (fields (field (name "MF") "Traco Power") (field (name "MP") "TSR 1-2433E"))
      (libsource (lib "eagle-import") (part "TSR_1-2433E"))
    )
    (comp (ref "BATTERY_INPUT")
      (value "XT60-M")
      (footprint "eagle-import:AMASS_XT60-M")
      (fields (field (name "MF") "AMASS"))
      (libsource (lib "eagle-import") (part "XT60-M"))
    )
    (comp (ref "C2")
      (value "220u")
      (footprint "eagle-import:E2,5-5")
      (libsource (lib "eagle-import") (part "CPOL-EUE2.5-5"))
    )
    (comp (ref "C3")
      (value "220u")
      (footprint "eagle-import:E2,5-5")
      (libsource (lib "eagle-import") (part "CPOL-EUE2.5-5"))
    )
    (comp (ref "C5")
      (value "4.7u")
      (footprint "eagle-import:C1206")
      (libsource (lib "eagle-import") (part "rcl_334_C-EUC1206"))
    )
    (comp (ref "C48")
      (value "4.7u")
      (footprint "eagle-import:C1206")
      (libsource (lib "eagle-import") (part "rcl_334_C-EUC1206"))
    )
    (comp (ref "C49")
      (value "4.7u")
      (footprint "eagle-import:C1206")
      (libsource (lib "eagle-import") (part "rcl_334_C-EUC1206"))
    )
    (comp (ref "C50")
      (value "4.7u")
      (footprint "eagle-import:C1206")
      (libsource (lib "eagle-import") (part "rcl_334_C-EUC1206"))
    )
    (comp (ref "C68")
      (value "4.7u")
      (footprint "eagle-import:C1206")
      (libsource (lib "eagle-import") (part "rcl_334_C-EUC1206"))
    )
    (comp (ref "C69")
      (value "4.7u")
      (footprint "eagle-import:C1206")
      (libsource (lib "eagle-import") (part "rcl_334_C-EUC1206"))
    )
    (comp (ref "C70")
      (value "4.7u")
      (footprint "eagle-import:C1206")
      (libsource (lib "eagle-import") (part "rcl_334_C-EUC1206"))
    )
    (comp (ref "C71")
      (value "4.7u")
      (footprint "eagle-import:C1206")
      (libsource (lib "eagle-import") (part "rcl_334_C-EUC1206"))
    )
    (comp (ref "C72")
      (value "220u")
      (footprint "eagle-import:E2,5-5")
      (libsource (lib "eagle-import") (part "CPOL-EUE2.5-5"))
    )
    (comp (ref "C80")
      (value "220u")
      (footprint "eagle-import:E2,5-5")
      (libsource (lib "eagle-import") (part "CPOL-EUE2.5-5"))
    )
    (comp (ref "C84")
      (value "4.7u")
      (footprint "eagle-import:C1206")
      (libsource (lib "eagle-import") (part "rcl_334_C-EUC1206"))
    )
    (comp (ref "C85")
      (value "4.7u")
      (footprint "eagle-import:C1206")
      (libsource (lib "eagle-import") (part "rcl_334_C-EUC1206"))
    )
    (comp (ref "C86")
      (value "4.7u")
      (footprint "eagle-import:C1206")
      (libsource (lib "eagle-import") (part "rcl_334_C-EUC1206"))
    )
    (comp (ref "C87")
      (value "4.7u")
      (footprint "eagle-import:C1206")
      (libsource (lib "eagle-import") (part "rcl_334_C-EUC1206"))
    )
    (comp (ref "CUTOFF_SWITCH")
      (value "CUTOFF SWITCH")
      (footprint "eagle-import:1X04")
      (libsource (lib "eagle-import") (part "PINHD-1X4"))
    )
    (comp (ref "D6")
      (value "6.8V")
      (footprint "eagle-import:SOD-323")
      (libsource (lib "eagle-import") (part "DIODE-ZENER-BZT52C3V6S"))
    )
    (comp (ref "EXTERNAL_INPUT")
      (value "XT60-M")
      (footprint "eagle-import:AMASS_XT60-M")
      (fields (field (name "MF") "AMASS"))
      (libsource (lib "eagle-import") (part "XT60-M"))
    )
    (comp (ref "L1")
      (value "7443641500")
      (footprint "eagle-import:74436413300")
      (fields (field (name "MOUSER_PART_NUMBER") "710-7443641500"))
      (libsource (lib "eagle-import") (part "7443641500"))
    )
    (comp (ref "LED2")
      (value "LEDSML0805")
      (footprint "eagle-import:SML0805")
      (libsource (lib "eagle-import") (part "LEDSML0805"))
    )
    (comp (ref "LED3")
      (value "LEDSML0805")
      (footprint "eagle-import:SML0805")
      (libsource (lib "eagle-import") (part "LEDSML0805"))
    )
    (comp (ref "LED4")
      (value "LEDSML0805")
      (footprint "eagle-import:SML0805")
      (libsource (lib "eagle-import") (part "LEDSML0805"))
    )
    (comp (ref "LED5")
      (value "LEDSML0805")
      (footprint "eagle-import:SML0805")
      (libsource (lib "eagle-import") (part "LEDSML0805"))
    )
    (comp (ref "LED7")
      (value "LEDSML0805")
      (footprint "eagle-import:SML0805")
      (libsource (lib "eagle-import") (part "LEDSML0805"))
    )
    (comp (ref "LED8")
      (value "LEDSML0805")
      (footprint "eagle-import:SML0805")
      (libsource (lib "eagle-import") (part "LEDSML0805"))
    )
    (comp (ref "MAIN_SWITCH")
      (value "MAIN SWITCH")
      (footprint "eagle-import:1X04")
      (libsource (lib "eagle-import") (part "PINHD-1X4"))
    )
    (comp (ref "PPTC")
      (value "MP005244 16V 12A")
      (footprint "eagle-import:FUSE_0ZCF0075AF2C")
      (fields (field (name "MF") "Bel Fuse") (field (name "MP") "0ZCF0075AF2C"))
      (libsource (lib "eagle-import") (part "0ZCF0075AF2C"))
    )
    (comp (ref "Q1")
      (value "FDD4141TO252")
      (footprint "eagle-import:TO252")
      (libsource (lib "eagle-import") (part "FDD4141TO252"))
    )
    (comp (ref "Q8")
      (value "FDD4141TO252")
      (footprint "eagle-import:TO252")
      (libsource (lib "eagle-import") (part "FDD4141TO252"))
    )
    (comp (ref "R1")
      (value "100R")
      (footprint "eagle-import:R0805")
      (libsource (lib "eagle-import") (part "rcl_334_R-EU_R0805"))
    )
    (comp (ref "R6")
      (value "1M")
      (footprint "eagle-import:R0805")
      (libsource (lib "eagle-import") (part "rcl_334_R-EU_R0805"))
    )
    (comp (ref "R7")
      (value "110k")
      (footprint "eagle-import:R0805")
      (libsource (lib "eagle-import") (part "rcl_334_R-EU_R0805"))
    )
    (comp (ref "R28")
      (value "100R")
      (footprint "eagle-import:R0603")
      (libsource (lib "eagle-import") (part "rcl_334_R-EU_R0603"))
    )
    (comp (ref "R29")
      (value "100R")
      (footprint "eagle-import:R0603")
      (libsource (lib "eagle-import") (part "rcl_334_R-EU_R0603"))
    )
    (comp (ref "R30")
      (value "100R")
      (footprint "eagle-import:R0603")
      (libsource (lib "eagle-import") (part "rcl_334_R-EU_R0603"))
    )
    (comp (ref "R31")
      (value "100R")
      (footprint "eagle-import:R0603")
      (libsource (lib "eagle-import") (part "rcl_334_R-EU_R0603"))
    )
    (comp (ref "R47")
      (value "10k")
      (footprint "eagle-import:R0805")
      (libsource (lib "eagle-import") (part "rcl_334_R-EU_R0805"))
    )
    (comp (ref "R61")
      (value "100R")
      (footprint "eagle-import:R0603")
      (libsource (lib "eagle-import") (part "rcl_334_R-EU_R0603"))
    )
    (comp (ref "R77")
      (value "5K")
      (footprint "eagle-import:R0805")
      (libsource (lib "eagle-import") (part "rcl_334_R-EU_R0805"))
    )
    (comp (ref "R78")
      (value "200R")
      (footprint "eagle-import:R0805")
      (libsource (lib "eagle-import") (part "rcl_334_R-EU_R0805"))
    )
    (comp (ref "R79")
      (value "10k")
      (footprint "eagle-import:R0805")
      (libsource (lib "eagle-import") (part "rcl_334_R-EU_R0805"))
    )
    (comp (ref "R81")
      (value "220R")
      (footprint "eagle-import:R0805")
      (libsource (lib "eagle-import") (part "rcl_334_R-EU_R0805"))
    )
    (comp (ref "R120")
      (value "200R")
      (footprint "eagle-import:R0805")
      (libsource (lib "eagle-import") (part "rcl_334_R-EU_R0805"))
    )
    (comp (ref "R121")
      (value "100R")
      (footprint "eagle-import:R0603")
      (libsource (lib "eagle-import") (part "rcl_334_R-EU_R0603"))
    )
    (comp (ref "TVS25V")
      (value "SUPRESSOR_TVS-UD-SMAJ")
      (footprint "eagle-import:SUPRESSOR_SMAJ")
      (libsource (lib "eagle-import") (part "SUPRESSOR_TVS-UD-SMAJ"))
    )
    (comp (ref "U9")
      (value "140357145000")
      (footprint "eagle-import:WL-OCPT_SOP4")
      (libsource (lib "eagle-import") (part "WL-OCPT_SERIES_357_140357145000"))
    )
    (comp (ref "U13")
      (value "140357145000")
      (footprint "eagle-import:WL-OCPT_SOP4")
      (libsource (lib "eagle-import") (part "WL-OCPT_SERIES_357_140357145000"))
    )
    (comp (ref "BATT1")
      (value "SMTU2032LF")
      (footprint "eagle-import:SMTU2032LF")
      (libsource (lib "eagle-import") (part "SMTU2032LF"))
    )
    (comp (ref "BOOT")
      (value "MOMENTARY-SWITCH-SPST-PTH-6.0MM")
      (footprint "eagle-import:TACTILE_SWITCH_PTH_6.0MM")
      (libsource (lib "eagle-import") (part "MOMENTARY-SWITCH-SPST-PTH-6.0MM"))
    )
    (comp (ref "BUTTONS")
      (value "BUTTONS")
      (footprint "eagle-import:1X10")
      (libsource (lib "eagle-import") (part "PINHD-1X10"))
    )
    (comp (ref "C1")
      (value "10n")
      (footprint "eagle-import:C0603")
      (libsource (lib "eagle-import") (part "rcl_334_C-EUC0603"))
    )
    (comp (ref "C4")
      (value "10n")
      (footprint "eagle-import:C0603")
      (libsource (lib "eagle-import") (part "rcl_334_C-EUC0603"))
    )
    (comp (ref "C67")
      (value "100n")
      (footprint "eagle-import:C0603")
      (libsource (lib "eagle-import") (part "C-EUC0603"))
    )
    (comp (ref "C73")
      (value "10n")
      (footprint "eagle-import:C0603")
      (libsource (lib "eagle-import") (part "rcl_334_C-EUC0603"))
    )
    (comp (ref "C74")
      (value "10n")
      (footprint "eagle-import:C0603")
      (libsource (lib "eagle-import") (part "rcl_334_C-EUC0603"))
    )
    (comp (ref "C75")
      (value "10n")
      (footprint "eagle-import:C0603")
      (libsource (lib "eagle-import") (part "rcl_334_C-EUC0603"))
    )
    (comp (ref "C76")
      (value "10n")
      (footprint "eagle-import:C0603")
      (libsource (lib "eagle-import") (part "rcl_334_C-EUC0603"))
    )
    (comp (ref "C77")
      (value "10n")
      (footprint "eagle-import:C0603")
      (libsource (lib "eagle-import") (part "rcl_334_C-EUC0603"))
    )
    (comp (ref "C78")
      (value "10n")
      (footprint "eagle-import:C0603")
      (libsource (lib "eagle-import") (part "rcl_334_C-EUC0603"))
    )
    (comp (ref "C81")
      (value "47u/6V3")
      (footprint "eagle-import:C1206")
      (libsource (lib "eagle-import") (part "C-EUC1206"))
    )
    (comp (ref "C82")
      (value "100n")
      (footprint "eagle-import:C0603")
      (libsource (lib "eagle-import") (part "C-EUC0603"))
    )
    (comp (ref "CAMERA")
      (value "ESP32_CAMERA")
      (footprint "eagle-import:1X04")
      (libsource (lib "eagle-import") (part "PINHD-1X4"))
    )
    (comp (ref "DISPLAY")
      (value "DISPLAY")
      (footprint "eagle-import:1X04")
      (libsource (lib "eagle-import") (part "PINHD-1X4"))
    )
    (comp (ref "EN")
      (value "MOMENTARY-SWITCH-SPST-PTH-6.0MM")
      (footprint "eagle-import:TACTILE_SWITCH_PTH_6.0MM")
      (libsource (lib "eagle-import") (part "MOMENTARY-SWITCH-SPST-PTH-6.0MM"))
    )
    (comp (ref "L3")
      (value "2112805")
      (footprint "eagle-import:L2825P")
      (libsource (lib "eagle-import") (part "L-EUL2825P"))
    )
    (comp (ref "LED1")
      (value "LEDSML0805")
      (footprint "eagle-import:SML0805")
      (libsource (lib "eagle-import") (part "LEDSML0805"))
    )
    (comp (ref "MCU_3_ESP32")
      (value "ESP-32S")
      (footprint "eagle-import:ESP-32S")
      (fields (field (name "MF") "Olimex LTD"))
      (libsource (lib "eagle-import") (part "ESP-32S"))
    )
    (comp (ref "R5")
      (value "4.7k")
      (footprint "eagle-import:R0603")
      (libsource (lib "eagle-import") (part "rcl_334_R-EU_R0603"))
    )
    (comp (ref "R26")
      (value "4.7k")
      (footprint "eagle-import:R0603")
      (libsource (lib "eagle-import") (part "rcl_334_R-EU_R0603"))
    )
    (comp (ref "R27")
      (value "1k")
      (footprint "eagle-import:R0603")
      (libsource (lib "eagle-import") (part "rcl_334_R-EU_R0603"))
    )
    (comp (ref "R73")
      (value "12k")
      (footprint "eagle-import:R0805")
      (libsource (lib "eagle-import") (part "rcl_334_R-EU_R0805"))
    )
    (comp (ref "R74")
      (value "12k")
      (footprint "eagle-import:R0805")
      (libsource (lib "eagle-import") (part "rcl_334_R-EU_R0805"))
    )
    (comp (ref "R75")
      (value "220R")
      (footprint "eagle-import:R0805")
      (libsource (lib "eagle-import") (part "rcl_334_R-EU_R0805"))
    )
    (comp (ref "R98")
      (value "10k")
      (footprint "eagle-import:R0603")
      (libsource (lib "eagle-import") (part "R-EU_R0603"))
    )
    (comp (ref "R99")
      (value "10k")
      (footprint "eagle-import:R0603")
      (libsource (lib "eagle-import") (part "R-EU_R0603"))
    )
    (comp (ref "R100")
      (value "1M")
      (footprint "eagle-import:R0603")
      (libsource (lib "eagle-import") (part "R-EU_R0603"))
    )
    (comp (ref "R101")
      (value "nc")
      (footprint "eagle-import:R0603")
      (libsource (lib "eagle-import") (part "R-EU_R0603"))
    )
    (comp (ref "R102")
      (value "nc")
      (footprint "eagle-import:R0603")
      (libsource (lib "eagle-import") (part "R-EU_R0603"))
    )
    (comp (ref "R103")
      (value "10k")
      (footprint "eagle-import:R0603")
      (libsource (lib "eagle-import") (part "R-EU_R0603"))
    )
    (comp (ref "R104")
      (value "10k")
      (footprint "eagle-import:R0603")
      (libsource (lib "eagle-import") (part "R-EU_R0603"))
    )
    (comp (ref "R105")
      (value "4.7k")
      (footprint "eagle-import:R0603")
      (libsource (lib "eagle-import") (part "R-EU_R0603"))
    )
    (comp (ref "R106")
      (value "4.7k")
      (footprint "eagle-import:R0603")
      (libsource (lib "eagle-import") (part "R-EU_R0603"))
    )
    (comp (ref "R111")
      (value "10k")
      (footprint "eagle-import:R0603")
      (libsource (lib "eagle-import") (part "rcl_334_R-EU_R0603"))
    )
    (comp (ref "R112")
      (value "10k")
      (footprint "eagle-import:R0603")
      (libsource (lib "eagle-import") (part "rcl_334_R-EU_R0603"))
    )
    (comp (ref "R113")
      (value "10k")
      (footprint "eagle-import:R0603")
      (libsource (lib "eagle-import") (part "rcl_334_R-EU_R0603"))
    )
    (comp (ref "R114")
      (value "10k")
      (footprint "eagle-import:R0603")
      (libsource (lib "eagle-import") (part "rcl_334_R-EU_R0603"))
    )
    (comp (ref "R115")
      (value "10k")
      (footprint "eagle-import:R0603")
      (libsource (lib "eagle-import") (part "rcl_334_R-EU_R0603"))
    )
    (comp (ref "R116")
      (value "10k")
      (footprint "eagle-import:R0603")
      (libsource (lib "eagle-import") (part "rcl_334_R-EU_R0603"))
    )
    (comp (ref "R117")
      (value "10k")
      (footprint "eagle-import:R0603")
      (libsource (lib "eagle-import") (part "rcl_334_R-EU_R0603"))
    )
    (comp (ref "R118")
      (value "10k")
      (footprint "eagle-import:R0603")
      (libsource (lib "eagle-import") (part "rcl_334_R-EU_R0603"))
    )
    (comp (ref "RGB_LED")
      (value "RGB_LED")
      (footprint "eagle-import:1X04")
      (libsource (lib "eagle-import") (part "PINHD-1X4"))
    )
    (comp (ref "RTCC")
      (value "AB-RTCMC-32.768KHZ-B5ZE-S3-T")
      (footprint "eagle-import:AB-RTCMC-32.768KHZ-B5ZE-S3-T")
      (libsource (lib "eagle-import") (part "AB-RTCMC-32.768KHZ-B5ZE-S3-T"))
    )
    (comp (ref "X5")
      (value "FPS009-3000")
      (footprint "eagle-import:FPS009-3000")
      (libsource (lib "eagle-import") (part "FPS009-3000"))
    )
    (comp (ref "C37")
      (value "1u")
      (footprint "eagle-import:C0603")
      (libsource (lib "eagle-import") (part "rcl@1_C-EUC0603"))
    )
    (comp (ref "C38")
      (value "100n")
      (footprint "eagle-import:C0603")
      (libsource (lib "eagle-import") (part "rcl@1_C-EUC0603"))
    )
    (comp (ref "C39")
      (value "100n")
      (footprint "eagle-import:C0603")
      (libsource (lib "eagle-import") (part "rcl@1_C-EUC0603"))
    )
    (comp (ref "C40")
      (value "4.7u")
      (footprint "eagle-import:C0603")
      (libsource (lib "eagle-import") (part "rcl@1_C-EUC0603"))
    )
    (comp (ref "C44")
      (value "10nF")
      (footprint "eagle-import:C0603")
      (libsource (lib "eagle-import") (part "rcl_334_C-EUC0603"))
    )
    (comp (ref "C45")
      (value "100nF")
      (footprint "eagle-import:C0603")
      (libsource (lib "eagle-import") (part "rcl_334_C-EUC0603"))
    )
    (comp (ref "C46")
      (value "2.2nF 50V")
      (footprint "eagle-import:C0603")
      (libsource (lib "eagle-import") (part "rcl_334_C-EUC0603"))
    )
    (comp (ref "C47")
      (value "100nF")
      (footprint "eagle-import:C0603")
      (libsource (lib "eagle-import") (part "rcl_334_C-EUC0603"))
    )
    (comp (ref "CP2102")
      (value "CP2101")
      (footprint "eagle-import:MLP28")
      (fields (field (name "MF") "FARNELL") (field (name "MPN") "CP2102-GM"))
      (libsource (lib "eagle-import") (part "CP2101"))
    )
    (comp (ref "D3")
      (value "BAT60J")
      (footprint "eagle-import:SOD323_ST")
      (libsource (lib "eagle-import") (part "BAT60J"))
    )
    (comp (ref "D4")
      (value "BAT60J")
      (footprint "eagle-import:SOD323_ST")
      (libsource (lib "eagle-import") (part "BAT60J"))
    )
    (comp (ref "D5")
      (value "BAT60J")
      (footprint "eagle-import:SOD323_ST")
      (libsource (lib "eagle-import") (part "BAT60J"))
    )
    (comp (ref "MICROUSB")
      (value "MICROUSB")
      (footprint "eagle-import:MOLEX_47642-0001")
      (fields (field (name "MF") "Molex") (field (name "MP") "47642-0001"))
      (libsource (lib "eagle-import") (part "MICROUSB"))
    )
    (comp (ref "R36")
      (value "4.7k")
      (footprint "eagle-import:R0603")
      (libsource (lib "eagle-import") (part "rcl_334_R-EU_R0603"))
    )
    (comp (ref "R37")
      (value "4.7k")
      (footprint "eagle-import:R0603")
      (libsource (lib "eagle-import") (part "rcl_334_R-EU_R0603"))
    )
    (comp (ref "R49")
      (value "10k")
      (footprint "eagle-import:R0603")
      (libsource (lib "eagle-import") (part "rcl@1_R-EU_R0603"))
    )
    (comp (ref "R50")
      (value "4.7k")
      (footprint "eagle-import:R0603")
      (libsource (lib "eagle-import") (part "rcl@1_R-EU_R0603"))
    )
    (comp (ref "U5")
      (value "MPU-6050")
      (footprint "eagle-import:24-VFQFN")
      (fields
        (field (name "DIGIKEY_PART_NUMBER") "1428-1007-1-ND")
        (field (name "MANUFACTURER") "TDK InvenSense")
        (field (name "CREATED_BY") "PCBLayout.com")
      )
      (libsource (lib "eagle-import") (part "MPU-6050"))
    )
    (comp (ref "C10")
      (value "100n")
      (footprint "eagle-import:C0603")
      (libsource (lib "eagle-import") (part "C-EUC0603"))
    )
    (comp (ref "C15")
      (value "100nF")
      (footprint "eagle-import:C0603")
      (libsource (lib "eagle-import") (part "rcl_334_C-EUC0603"))
    )
    (comp (ref "C18")
      (value "100n")
      (footprint "eagle-import:C0603")
      (libsource (lib "eagle-import") (part "C-EUC0603"))
    )
    (comp (ref "C21")
      (value "100n")
      (footprint "eagle-import:C0603")
      (libsource (lib "eagle-import") (part "C-EUC0603"))
    )
    (comp (ref "C22")
      (value "100n")
      (footprint "eagle-import:C0603")
      (libsource (lib "eagle-import") (part "C-EUC0603"))
    )
    (comp (ref "C23")
      (value "100n")
      (footprint "eagle-import:C0603")
      (libsource (lib "eagle-import") (part "C-EUC0603"))
    )
    (comp (ref "LED15")
      (value "LEDSML0805")
      (footprint "eagle-import:SML0805")
      (libsource (lib "eagle-import") (part "LEDSML0805"))
    )
    (comp (ref "LED21")
      (value "LEDSML0805")
      (footprint "eagle-import:SML0805")
      (libsource (lib "eagle-import") (part "LEDSML0805"))
    )
    (comp (ref "LED22")
      (value "LEDSML0805")
      (footprint "eagle-import:SML0805")
      (libsource (lib "eagle-import") (part "LEDSML0805"))
    )
    (comp (ref "LED23")
      (value "LEDSML0805")
      (footprint "eagle-import:SML0805")
      (libsource (lib "eagle-import") (part "LEDSML0805"))
    )
    (comp (ref "MCU_2")
      (value "BM05B-PASS_STANDARD")
      (footprint "eagle-import:BM05B-PASS")
      (libsource (lib "eagle-import") (part "BM05B-PASS_STANDARD"))
    )
    (comp (ref "R12")
      (value "10k")
      (footprint "eagle-import:R0805")
      (libsource (lib "eagle-import") (part "rcl_334_R-EU_R0805"))
    )
    (comp (ref "R13")
      (value "1k")
      (footprint "eagle-import:R0805")
      (libsource (lib "eagle-import") (part "rcl_334_R-EU_R0805"))
    )
    (comp (ref "R84")
      (value "130R")
      (footprint "eagle-import:R0603")
      (libsource (lib "eagle-import") (part "rcl_334_R-EU_R0603"))
    )
    (comp (ref "R91")
      (value "130R")
      (footprint "eagle-import:R0603")
      (libsource (lib "eagle-import") (part "rcl_334_R-EU_R0603"))
    )
    (comp (ref "R92")
      (value "130R")
      (footprint "eagle-import:R0603")
      (libsource (lib "eagle-import") (part "rcl_334_R-EU_R0603"))
    )
    (comp (ref "R93")
      (value "130R")
      (footprint "eagle-import:R0603")
      (libsource (lib "eagle-import") (part "rcl_334_R-EU_R0603"))
    )
    (comp (ref "U15")
      (value "PIC32MK1024MCM064-I/PTTQFP64_PT_MCH")
      (footprint "eagle-import:TQFP64_PT_MCH")
      (fields
        (field (name "MANUFACTURER_PART_NUMBER") "PIC32MK1024MCM064-I/PT")
        (field (name "COPYRIGHT") "Copyright (C) 2022 Ultra Librarian. All rights reserved.")
      )
      (libsource (lib "eagle-import") (part "PIC32MK1024MCM064-I/PTTQFP64_PT_MCH"))
    )
    (comp (ref "C63")
      (value "1u")
      (footprint "eagle-import:C0603")
      (libsource (lib "eagle-import") (part "rcl@1_C-EUC0603"))
    )
    (comp (ref "C64")
      (value "1u")
      (footprint "eagle-import:C0603")
      (libsource (lib "eagle-import") (part "rcl@1_C-EUC0603"))
    )
    (comp (ref "C65")
      (value "1u")
      (footprint "eagle-import:C0603")
      (libsource (lib "eagle-import") (part "rcl@1_C-EUC0603"))
    )
    (comp (ref "C66")
      (value "1u")
      (footprint "eagle-import:C0603")
      (libsource (lib "eagle-import") (part "rcl@1_C-EUC0603"))
    )
    (comp (ref "D2")
      (value "3V3")
      (footprint "eagle-import:SOD80C")
      (libsource (lib "eagle-import") (part "ZENER-DIODESOD80C"))
    )
    (comp (ref "GPS")
      (value "GPS MODULE")
      (footprint "eagle-import:1X05")
      (libsource (lib "eagle-import") (part "PINHD-1X5"))
    )
    (comp (ref "LIDAR")
      (value "LIDAR")
      (footprint "eagle-import:1X08")
      (libsource (lib "eagle-import") (part "PINHD-1X8"))
    )
    (comp (ref "LIGHT_SENSOR")
      (value "PHOTORESISTOR LDR5549")
      (footprint "eagle-import:1X02")
      (libsource (lib "eagle-import") (part "PINHD-1X2"))
    )
    (comp (ref "LIMIT_SWITCH_DOWN")
      (value "LIMIT_SWITCH_BOTTOM_MAGNETIC")
      (footprint "eagle-import:1X03")
      (libsource (lib "eagle-import") (part "PINHD-1X3"))
    )
    (comp (ref "LIMIT_SWITCH_UP")
      (value "LIMIT_SWITCH_UPPER_MAGNETIC")
      (footprint "eagle-import:1X03")
      (libsource (lib "eagle-import") (part "PINHD-1X3"))
    )
    (comp (ref "MAIN_MOTOR")
      (value "BLADE MOTOR")
      (footprint "eagle-import:1X04")
      (libsource (lib "eagle-import") (part "PINHD-1X4"))
    )
    (comp (ref "NAVIGATION_UART")
      (value "TELEMETRY_UART")
      (footprint "eagle-import:1X02")
      (libsource (lib "eagle-import") (part "PINHD-1X2"))
    )
    (comp (ref "NMOS1")
      (value "BSC340N08NS3G")
      (footprint "eagle-import:PG-TDSON-8")
      (libsource (lib "eagle-import") (part "BSC340N08NS3G"))
    )
    (comp (ref "PERIMETER_WIRE")
      (value "PER.WIRE SENSE")
      (footprint "eagle-import:1X04")
      (libsource (lib "eagle-import") (part "PINHD-1X4"))
    )
    (comp (ref "R4")
      (value "1k")
      (footprint "eagle-import:R0805")
      (libsource (lib "eagle-import") (part "rcl_334_R-EU_R0805"))
    )
    (comp (ref "R54")
      (value "1k")
      (footprint "eagle-import:R0805")
      (libsource (lib "eagle-import") (part "rcl_334_R-EU_R0805"))
    )
    (comp (ref "R55")
      (value "500k")
      (footprint "eagle-import:R0805")
      (libsource (lib "eagle-import") (part "rcl_334_R-EU_R0805"))
    )
    (comp (ref "R57")
      (value "10R")
      (footprint "eagle-import:R0805")
      (libsource (lib "eagle-import") (part "rcl_334_R-EU_R0805"))
    )
    (comp (ref "R62")
      (value "200R")
      (footprint "eagle-import:R0805")
      (libsource (lib "eagle-import") (part "rcl_334_R-EU_R0805"))
    )
    (comp (ref "R64")
      (value "500k")
      (footprint "eagle-import:R0805")
      (libsource (lib "eagle-import") (part "rcl_334_R-EU_R0805"))
    )
    (comp (ref "R66")
      (value "10R")
      (footprint "eagle-import:R0805")
      (libsource (lib "eagle-import") (part "rcl_334_R-EU_R0805"))
    )
    (comp (ref "R69")
      (value "5k")
      (footprint "eagle-import:R0805")
      (libsource (lib "eagle-import") (part "rcl_334_R-EU_R0805"))
    )
    (comp (ref "R70")
      (value "5k")
      (footprint "eagle-import:R0805")
      (libsource (lib "eagle-import") (part "rcl_334_R-EU_R0805"))
    )
    (comp (ref "R71")
      (value "5k")
      (footprint "eagle-import:R0805")
      (libsource (lib "eagle-import") (part "rcl_334_R-EU_R0805"))
    )
    (comp (ref "R72")
      (value "5k")
      (footprint "eagle-import:R0805")
      (libsource (lib "eagle-import") (part "rcl_334_R-EU_R0805"))
    )
    (comp (ref "R107")
      (value "10k")
      (footprint "eagle-import:R0805")
      (libsource (lib "eagle-import") (part "rcl_334_R-EU_R0805"))
    )
    (comp (ref "R108")
      (value "10k")
      (footprint "eagle-import:R0805")
      (libsource (lib "eagle-import") (part "rcl_334_R-EU_R0805"))
    )
    (comp (ref "R109")
      (value "10k")
      (footprint "eagle-import:R0805")
      (libsource (lib "eagle-import") (part "rcl_334_R-EU_R0805"))
    )
    (comp (ref "R110")
      (value "10k")
      (footprint "eagle-import:R0805")
      (libsource (lib "eagle-import") (part "rcl_334_R-EU_R0805"))
    )
    (comp (ref "RAIN_SENSOR")
      (value "RAIN SENSOR")
      (footprint "eagle-import:1X02")
      (libsource (lib "eagle-import") (part "PINHD-1X2"))
    )
    (comp (ref "STEPPER_0")
      (value "STEPPER_0")
      (footprint "eagle-import:1X04")
      (libsource (lib "eagle-import") (part "PINHD-1X4"))
    )
    (comp (ref "STEPPER_1")
      (value "STEPPER_1")
      (footprint "eagle-import:1X04")
      (libsource (lib "eagle-import") (part "PINHD-1X4"))
    )
    (comp (ref "STEPPER_2")
      (value "STEPPER_2")
      (footprint "eagle-import:1X04")
      (libsource (lib "eagle-import") (part "PINHD-1X4"))
    )
    (comp (ref "TEMP_SENSOR_0")
      (value "TEMP SENSOR 0")
      (footprint "eagle-import:1X03")
      (libsource (lib "eagle-import") (part "PINHD-1X3"))
    )
    (comp (ref "TEMP_SENSOR_1")
      (value "TEMP SENSOR 1")
      (footprint "eagle-import:1X03")
      (libsource (lib "eagle-import") (part "PINHD-1X3"))
    )
    (comp (ref "TEMP_SENSOR_2")
      (value "TEMP SENSOR 2")
      (footprint "eagle-import:1X03")
      (libsource (lib "eagle-import") (part "PINHD-1X3"))
    )
    (comp (ref "TEMP_SENSOR_3")
      (value "TEMP SENSOR 3")
      (footprint "eagle-import:1X03")
      (libsource (lib "eagle-import") (part "PINHD-1X3"))
    )
    (comp (ref "U10")
      (value "140357145000")
      (footprint "eagle-import:WL-OCPT_SOP4")
      (libsource (lib "eagle-import") (part "WL-OCPT_SERIES_357_140357145000"))
    )
    (comp (ref "UNLIMITED_POWER")
      (value "V_OUTPUT")
      (footprint "eagle-import:1X05")
      (libsource (lib "eagle-import") (part "PINHD-1X5"))
    )
    (comp (ref "C19")
      (value "6.8nF 25V")
      (footprint "eagle-import:C0603")
      (libsource (lib "eagle-import") (part "rcl_334_C-EUC0603"))
    )
    (comp (ref "C20")
      (value "6.8nF 25V")
      (footprint "eagle-import:C0603")
      (libsource (lib "eagle-import") (part "rcl_334_C-EUC0603"))
    )
    (comp (ref "C24")
      (value "6.8nF 25V")
      (footprint "eagle-import:C0603")
      (libsource (lib "eagle-import") (part "rcl_334_C-EUC0603"))
    )
    (comp (ref "C25")
      (value "6.8nF 25V")
      (footprint "eagle-import:C0603")
      (libsource (lib "eagle-import") (part "rcl_334_C-EUC0603"))
    )
    (comp (ref "C26")
      (value "6.8nF 25V")
      (footprint "eagle-import:C0603")
      (libsource (lib "eagle-import") (part "rcl_334_C-EUC0603"))
    )
    (comp (ref "C27")
      (value "6.8nF 25V")
      (footprint "eagle-import:C0603")
      (libsource (lib "eagle-import") (part "rcl_334_C-EUC0603"))
    )
    (comp (ref "C28")
      (value "6.8nF 25V")
      (footprint "eagle-import:C0603")
      (libsource (lib "eagle-import") (part "rcl_334_C-EUC0603"))
    )
    (comp (ref "C29")
      (value "6.8nF 25V")
      (footprint "eagle-import:C0603")
      (libsource (lib "eagle-import") (part "rcl_334_C-EUC0603"))
    )
    (comp (ref "C30")
      (value "6.8nF 25V")
      (footprint "eagle-import:C0603")
      (libsource (lib "eagle-import") (part "rcl_334_C-EUC0603"))
    )
    (comp (ref "C31")
      (value "6.8nF 25V")
      (footprint "eagle-import:C0603")
      (libsource (lib "eagle-import") (part "rcl_334_C-EUC0603"))
    )
    (comp (ref "C32")
      (value "6.8nF 25V")
      (footprint "eagle-import:C0603")
      (libsource (lib "eagle-import") (part "rcl_334_C-EUC0603"))
    )
    (comp (ref "C33")
      (value "6.8nF 25V")
      (footprint "eagle-import:C0603")
      (libsource (lib "eagle-import") (part "rcl_334_C-EUC0603"))
    )
    (comp (ref "CURRENT_SENSOR_BATT")
      (value "TLI4971A050T5UE0001XUMA1")
      (footprint "eagle-import:IC_TLI4971A050T5UE0001XUMA1")
      (fields (field (name "MF") "Infineon Technologies"))
      (libsource (lib "eagle-import") (part "TLI4971A050T5UE0001XUMA1"))
    )
    (comp (ref "MAIN_MOTOR_CS")
      (value "TLI4971A050T5UE0001XUMA1")
      (footprint "eagle-import:IC_TLI4971A050T5UE0001XUMA1")
      (fields (field (name "MF") "Infineon Technologies"))
      (libsource (lib "eagle-import") (part "TLI4971A050T5UE0001XUMA1"))
    )
    (comp (ref "R14")
      (value "220R")
      (footprint "eagle-import:R0805")
      (libsource (lib "eagle-import") (part "rcl_334_R-EU_R0805"))
    )
    (comp (ref "R15")
      (value "220R")
      (footprint "eagle-import:R0805")
      (libsource (lib "eagle-import") (part "rcl_334_R-EU_R0805"))
    )
    (comp (ref "R16")
      (value "220R")
      (footprint "eagle-import:R0805")
      (libsource (lib "eagle-import") (part "rcl_334_R-EU_R0805"))
    )
    (comp (ref "R17")
      (value "220R")
      (footprint "eagle-import:R0805")
      (libsource (lib "eagle-import") (part "rcl_334_R-EU_R0805"))
    )
    (comp (ref "R18")
      (value "220R")
      (footprint "eagle-import:R0805")
      (libsource (lib "eagle-import") (part "rcl_334_R-EU_R0805"))
    )
    (comp (ref "R19")
      (value "220R")
      (footprint "eagle-import:R0805")
      (libsource (lib "eagle-import") (part "rcl_334_R-EU_R0805"))
    )
    (comp (ref "R20")
      (value "220R")
      (footprint "eagle-import:R0805")
      (libsource (lib "eagle-import") (part "rcl_334_R-EU_R0805"))
    )
    (comp (ref "R21")
      (value "220R")
      (footprint "eagle-import:R0805")
      (libsource (lib "eagle-import") (part "rcl_334_R-EU_R0805"))
    )
    (comp (ref "STEPPER_0_CS")
      (value "TLI4971A050T5UE0001XUMA1")
      (footprint "eagle-import:IC_TLI4971A050T5UE0001XUMA1")
      (fields (field (name "MF") "Infineon Technologies"))
      (libsource (lib "eagle-import") (part "TLI4971A050T5UE0001XUMA1"))
    )
    (comp (ref "STEPPER_1_CS")
      (value "TLI4971A050T5UE0001XUMA1")
      (footprint "eagle-import:IC_TLI4971A050T5UE0001XUMA1")
      (fields (field (name "MF") "Infineon Technologies"))
      (libsource (lib "eagle-import") (part "TLI4971A050T5UE0001XUMA1"))
    )
    (comp (ref "EM_LIGHT")
      (value "EMERGENCY LIGHT")
      (footprint "eagle-import:1X02")
      (libsource (lib "eagle-import") (part "PINHD-1X2"))
    )
    (comp (ref "FAN_0")
      (value "FAN_0")
      (footprint "eagle-import:1X02")
      (libsource (lib "eagle-import") (part "PINHD-1X2"))
    )
    (comp (ref "FAN_1")
      (value "FAN_1")
      (footprint "eagle-import:1X02")
      (libsource (lib "eagle-import") (part "PINHD-1X2"))
    )
    (comp (ref "FAN_2")
      (value "FAN_2")
      (footprint "eagle-import:1X02")
      (libsource (lib "eagle-import") (part "PINHD-1X2"))
    )
    (comp (ref "FAN_3")
      (value "FAN_3")
      (footprint "eagle-import:1X02")
      (libsource (lib "eagle-import") (part "PINHD-1X2"))
    )
    (comp (ref "NMOS2")
      (value "BSC340N08NS3G")
      (footprint "eagle-import:PG-TDSON-8")
      (libsource (lib "eagle-import") (part "BSC340N08NS3G"))
    )
    (comp (ref "NMOS3")
      (value "BSC340N08NS3G")
      (footprint "eagle-import:PG-TDSON-8")
      (libsource (lib "eagle-import") (part "BSC340N08NS3G"))
    )
    (comp (ref "NMOS4")
      (value "BSC340N08NS3G")
      (footprint "eagle-import:PG-TDSON-8")
      (libsource (lib "eagle-import") (part "BSC340N08NS3G"))
    )
    (comp (ref "NMOS5")
      (value "BSC340N08NS3G")
      (footprint "eagle-import:PG-TDSON-8")
      (libsource (lib "eagle-import") (part "BSC340N08NS3G"))
    )
    (comp (ref "NMOS6")
      (value "BSC340N08NS3G")
      (footprint "eagle-import:PG-TDSON-8")
      (libsource (lib "eagle-import") (part "BSC340N08NS3G"))
    )
    (comp (ref "R22")
      (value "200R")
      (footprint "eagle-import:R0805")
      (libsource (lib "eagle-import") (part "rcl_334_R-EU_R0805"))
    )
    (comp (ref "R51")
      (value "200R")
      (footprint "eagle-import:R0805")
      (libsource (lib "eagle-import") (part "rcl_334_R-EU_R0805"))
    )
    (comp (ref "R52")
      (value "200R")
      (footprint "eagle-import:R0805")
      (libsource (lib "eagle-import") (part "rcl_334_R-EU_R0805"))
    )
    (comp (ref "R53")
      (value "200R")
      (footprint "eagle-import:R0805")
      (libsource (lib "eagle-import") (part "rcl_334_R-EU_R0805"))
    )
    (comp (ref "R63")
      (value "1k")
      (footprint "eagle-import:R0805")
      (libsource (lib "eagle-import") (part "rcl_334_R-EU_R0805"))
    )
    (comp (ref "R65")
      (value "1k")
      (footprint "eagle-import:R0805")
      (libsource (lib "eagle-import") (part "rcl_334_R-EU_R0805"))
    )
    (comp (ref "R67")
      (value "1k")
      (footprint "eagle-import:R0805")
      (libsource (lib "eagle-import") (part "rcl_334_R-EU_R0805"))
    )
    (comp (ref "R68")
      (value "1k")
      (footprint "eagle-import:R0805")
      (libsource (lib "eagle-import") (part "rcl_334_R-EU_R0805"))
    )
    (comp (ref "R76")
      (value "1k")
      (footprint "eagle-import:R0805")
      (libsource (lib "eagle-import") (part "rcl_334_R-EU_R0805"))
    )
    (comp (ref "R119")
      (value "200R")
      (footprint "eagle-import:R0805")
      (libsource (lib "eagle-import") (part "rcl_334_R-EU_R0805"))
    )
    (comp (ref "U4")
      (value "140357145000")
      (footprint "eagle-import:WL-OCPT_SOP4")
      (libsource (lib "eagle-import") (part "WL-OCPT_SERIES_357_140357145000"))
    )
    (comp (ref "U6")
      (value "140357145000")
      (footprint "eagle-import:WL-OCPT_SOP4")
      (libsource (lib "eagle-import") (part "WL-OCPT_SERIES_357_140357145000"))
    )
    (comp (ref "U7")
      (value "140357145000")
      (footprint "eagle-import:WL-OCPT_SOP4")
      (libsource (lib "eagle-import") (part "WL-OCPT_SERIES_357_140357145000"))
    )
    (comp (ref "U8")
      (value "140357145000")
      (footprint "eagle-import:WL-OCPT_SOP4")
      (libsource (lib "eagle-import") (part "WL-OCPT_SERIES_357_140357145000"))
    )
    (comp (ref "U12")
      (value "140357145000")
      (footprint "eagle-import:WL-OCPT_SOP4")
      (libsource (lib "eagle-import") (part "WL-OCPT_SERIES_357_140357145000"))
    )
    (comp (ref "BUZZER")
      (value "BUZZER-PTH")
      (footprint "eagle-import:BUZZER-12MM")
      (libsource (lib "eagle-import") (part "BUZZER-PTH"))
    )
    (comp (ref "C7")
      (value "10u 6.3V")
      (footprint "eagle-import:C1206")
      (libsource (lib "eagle-import") (part "rcl_334_C-EUC1206"))
    )
    (comp (ref "C8")
      (value "100nF")
      (footprint "eagle-import:C0603")
      (libsource (lib "eagle-import") (part "rcl_334_C-EUC0603"))
    )
    (comp (ref "C9")
      (value "100nF")
      (footprint "eagle-import:C0603")
      (libsource (lib "eagle-import") (part "rcl_334_C-EUC0603"))
    )
    (comp (ref "C11")
      (value "100nF")
      (footprint "eagle-import:C0603")
      (libsource (lib "eagle-import") (part "rcl_334_C-EUC0603"))
    )
    (comp (ref "C79")
      (value "100n")
      (footprint "eagle-import:C1206")
      (libsource (lib "eagle-import") (part "rcl_334_C-EUC1206"))
    )
    (comp (ref "LED12")
      (value "LEDSML0805")
      (footprint "eagle-import:SML0805")
      (libsource (lib "eagle-import") (part "LEDSML0805"))
    )
    (comp (ref "LED13")
      (value "LEDSML0805")
      (footprint "eagle-import:SML0805")
      (libsource (lib "eagle-import") (part "LEDSML0805"))
    )
    (comp (ref "LED14")
      (value "LEDSML0805")
      (footprint "eagle-import:SML0805")
      (libsource (lib "eagle-import") (part "LEDSML0805"))
    )
    (comp (ref "LED16")
      (value "LEDSML0805")
      (footprint "eagle-import:SML0805")
      (libsource (lib "eagle-import") (part "LEDSML0805"))
    )
    (comp (ref "LED17")
      (value "LEDSML0805")
      (footprint "eagle-import:SML0805")
      (libsource (lib "eagle-import") (part "LEDSML0805"))
    )
    (comp (ref "LED18")
      (value "LEDSML0805")
      (footprint "eagle-import:SML0805")
      (libsource (lib "eagle-import") (part "LEDSML0805"))
    )
    (comp (ref "LED19")
      (value "LEDSML0805")
      (footprint "eagle-import:SML0805")
      (libsource (lib "eagle-import") (part "LEDSML0805"))
    )
    (comp (ref "LED20")
      (value "LEDSML0805")
      (footprint "eagle-import:SML0805")
      (libsource (lib "eagle-import") (part "LEDSML0805"))
    )
    (comp (ref "MCU_0")
      (value "BM05B-PASS_STANDARD")
      (footprint "eagle-import:BM05B-PASS")
      (libsource (lib "eagle-import") (part "BM05B-PASS_STANDARD"))
    )
    (comp (ref "R10")
      (value "10k")
      (footprint "eagle-import:R0805")
      (libsource (lib "eagle-import") (part "rcl_334_R-EU_R0805"))
    )
    (comp (ref "R11")
      (value "100R")
      (footprint "eagle-import:R0805")
      (libsource (lib "eagle-import") (part "rcl_334_R-EU_R0805"))
    )
    (comp (ref "R24")
      (value "100R")
      (footprint "eagle-import:R0805")
      (libsource (lib "eagle-import") (part "rcl_334_R-EU_R0805"))
    )
    (comp (ref "R25")
      (value "100R")
      (footprint "eagle-import:R0805")
      (libsource (lib "eagle-import") (part "rcl_334_R-EU_R0805"))
    )
    (comp (ref "R80")
      (value "130R")
      (footprint "eagle-import:R0603")
      (libsource (lib "eagle-import") (part "rcl_334_R-EU_R0603"))
    )
    (comp (ref "R82")
      (value "130R")
      (footprint "eagle-import:R0603")
      (libsource (lib "eagle-import") (part "rcl_334_R-EU_R0603"))
    )
    (comp (ref "R83")
      (value "130R")
      (footprint "eagle-import:R0603")
      (libsource (lib "eagle-import") (part "rcl_334_R-EU_R0603"))
    )
    (comp (ref "R85")
      (value "130R")
      (footprint "eagle-import:R0603")
      (libsource (lib "eagle-import") (part "rcl_334_R-EU_R0603"))
    )
    (comp (ref "R86")
      (value "130R")
      (footprint "eagle-import:R0603")
      (libsource (lib "eagle-import") (part "rcl_334_R-EU_R0603"))
    )
    (comp (ref "R87")
      (value "130R")
      (footprint "eagle-import:R0603")
      (libsource (lib "eagle-import") (part "rcl_334_R-EU_R0603"))
    )
    (comp (ref "R88")
      (value "130R")
      (footprint "eagle-import:R0603")
      (libsource (lib "eagle-import") (part "rcl_334_R-EU_R0603"))
    )
    (comp (ref "R89")
      (value "130R")
      (footprint "eagle-import:R0603")
      (libsource (lib "eagle-import") (part "rcl_334_R-EU_R0603"))
    )
    (comp (ref "R90")
      (value "10k")
      (footprint "eagle-import:R0603")
      (libsource (lib "eagle-import") (part "rcl_334_R-EU_R0603"))
    )
    (comp (ref "T2")
      (value "2N2222A")
      (footprint "eagle-import:TO92-CBE")
      (libsource (lib "eagle-import") (part "-NPN-TO92-CBEBC547"))
    )
    (comp (ref "TILT_SENSOR")
      (value "TILT SENSOR")
      (footprint "eagle-import:1X02")
      (libsource (lib "eagle-import") (part "PINHD-1X2"))
    )
    (comp (ref "U1")
      (value "PIC18F47J13-I/PT")
      (footprint "eagle-import:TQFP44_10X10MC_MCH")
      (fields
        (field (name "MANUFACTURER_PART_NUMBER") "pic18f47j13-i/pt")
        (field (name "COPYRIGHT") "Copyright (C) 2022 Ultra Librarian. All rights reserved.")
      )
      (libsource (lib "eagle-import") (part "PIC18F47J13-I/PT"))
    )
  )
  (nets
    (net (code "1") (name "3V3") (class "Default")
      (node (ref "3V3_REG0") (pin "3") (pinfunction "+VOUT_3") (pintype "output"))
      (node (ref "3V3_REG1") (pin "3") (pinfunction "+VOUT_3") (pintype "output"))
      (node (ref "3V3_REG2") (pin "3") (pinfunction "+VOUT_3") (pintype "output"))
      (node (ref "3V3_REG3") (pin "3") (pinfunction "+VOUT_3") (pintype "output"))
      (node (ref "C10") (pin "1") (pinfunction "1_1") (pintype "passive"))
      (node (ref "C12") (pin "2") (pinfunction "2_2") (pintype "passive"))
      (node (ref "C14") (pin "1") (pinfunction "1_1") (pintype "passive"))
      (node (ref "C18") (pin "1") (pinfunction "1_1") (pintype "passive"))
      (node (ref "C20") (pin "2") (pinfunction "2_2") (pintype "passive"))
      (node (ref "C21") (pin "1") (pinfunction "1_1") (pintype "passive"))
      (node (ref "C22") (pin "1") (pinfunction "1_1") (pintype "passive"))
      (node (ref "C23") (pin "1") (pinfunction "1_1") (pintype "passive"))
      (node (ref "C26") (pin "2") (pinfunction "2_2") (pintype "passive"))
      (node (ref "C29") (pin "2") (pinfunction "2_2") (pintype "passive"))
      (node (ref "C32") (pin "2") (pinfunction "2_2") (pintype "passive"))
      (node (ref "C39") (pin "1") (pinfunction "1_1") (pintype "passive"))
      (node (ref "C40") (pin "1") (pinfunction "1_1") (pintype "passive"))
      (node (ref "C44") (pin "1") (pinfunction "1_1") (pintype "passive"))
      (node (ref "C45") (pin "1") (pinfunction "1_1") (pintype "passive"))
      (node (ref "C49") (pin "1") (pinfunction "1_1") (pintype "passive"))
      (node (ref "C5") (pin "1") (pinfunction "1_1") (pintype "passive"))
      (node (ref "C63") (pin "2") (pinfunction "2_2") (pintype "passive"))
      (node (ref "C64") (pin "2") (pinfunction "2_2") (pintype "passive"))
      (node (ref "C65") (pin "2") (pinfunction "2_2") (pintype "passive"))
      (node (ref "C66") (pin "2") (pinfunction "2_2") (pintype "passive"))
      (node (ref "C67") (pin "2") (pinfunction "2_2") (pintype "passive"))
      (node (ref "C68") (pin "1") (pinfunction "1_1") (pintype "passive"))
      (node (ref "C70") (pin "1") (pinfunction "1_1") (pintype "passive"))
      (node (ref "C8") (pin "2") (pinfunction "2_2") (pintype "passive"))
      (node (ref "C82") (pin "1") (pinfunction "1_1") (pintype "passive"))
      (node (ref "C9") (pin "2") (pinfunction "2_2") (pintype "passive"))
      (node (ref "CAMERA") (pin "3") (pinfunction "3_3") (pintype "passive"))
      (node (ref "CP2102") (pin "6") (pinfunction "VDD_6") (pintype "power_in"))
      (node (ref "CURRENT_SENSOR_BATT") (pin "1") (pinfunction "VDD_1") (pintype "power_in"))
      (node (ref "GPS") (pin "1") (pinfunction "1_1") (pintype "passive"))
      (node (ref "IC1") (pin "13") (pinfunction "VDD_2_13") (pintype "passive"))
      (node (ref "IC1") (pin "28") (pinfunction "VDD_28") (pintype "passive"))
      (node (ref "L3") (pin "2") (pinfunction "2_2") (pintype "passive"))
      (node (ref "LIMIT_SWITCH_DOWN") (pin "1") (pinfunction "1_1") (pintype "passive"))
      (node (ref "LIMIT_SWITCH_UP") (pin "1") (pinfunction "1_1") (pintype "passive"))
      (node (ref "MAIN_MOTOR_CS") (pin "1") (pinfunction "VDD_1") (pintype "power_in"))
      (node (ref "MCU_0") (pin "P$5") (pinfunction "5_P$5") (pintype "bidirectional"))
      (node (ref "MCU_1") (pin "P$5") (pinfunction "5_P$5") (pintype "bidirectional"))
      (node (ref "MCU_2") (pin "P$5") (pinfunction "5_P$5") (pintype "bidirectional"))
      (node (ref "MCU_3_ESP32") (pin "2") (pinfunction "3V3_2") (pintype "power_in"))
      (node (ref "R10") (pin "2") (pinfunction "2_2") (pintype "passive"))
      (node (ref "R101") (pin "1") (pinfunction "1_1") (pintype "passive"))
      (node (ref "R102") (pin "1") (pinfunction "1_1") (pintype "passive"))
      (node (ref "R103") (pin "2") (pinfunction "2_2") (pintype "passive"))
      (node (ref "R104") (pin "2") (pinfunction "2_2") (pintype "passive"))
      (node (ref "R105") (pin "2") (pinfunction "2_2") (pintype "passive"))
      (node (ref "R106") (pin "2") (pinfunction "2_2") (pintype "passive"))
      (node (ref "R12") (pin "2") (pinfunction "2_2") (pintype "passive"))
      (node (ref "R14") (pin "1") (pinfunction "1_1") (pintype "passive"))
      (node (ref "R16") (pin "1") (pinfunction "1_1") (pintype "passive"))
      (node (ref "R18") (pin "1") (pinfunction "1_1") (pintype "passive"))
      (node (ref "R20") (pin "1") (pinfunction "1_1") (pintype "passive"))
      (node (ref "R26") (pin "1") (pinfunction "1_1") (pintype "passive"))
      (node (ref "R27") (pin "1") (pinfunction "1_1") (pintype "passive"))
      (node (ref "R28") (pin "1") (pinfunction "1_1") (pintype "passive"))
      (node (ref "R29") (pin "1") (pinfunction "1_1") (pintype "passive"))
      (node (ref "R30") (pin "1") (pinfunction "1_1") (pintype "passive"))
      (node (ref "R31") (pin "1") (pinfunction "1_1") (pintype "passive"))
      (node (ref "R34") (pin "1") (pinfunction "1_1") (pintype "passive"))
      (node (ref "R36") (pin "1") (pinfunction "1_1") (pintype "passive"))
      (node (ref "R37") (pin "1") (pinfunction "1_1") (pintype "passive"))
      (node (ref "R40") (pin "1") (pinfunction "1_1") (pintype "passive"))
      (node (ref "R45") (pin "1") (pinfunction "1_1") (pintype "passive"))
      (node (ref "R47") (pin "1") (pinfunction "1_1") (pintype "passive"))
      (node (ref "R5") (pin "1") (pinfunction "1_1") (pintype "passive"))
      (node (ref "R50") (pin "2") (pinfunction "2_2") (pintype "passive"))
      (node (ref "R55") (pin "1") (pinfunction "1_1") (pintype "passive"))
      (node (ref "R64") (pin "1") (pinfunction "1_1") (pintype "passive"))
      (node (ref "R69") (pin "2") (pinfunction "2_2") (pintype "passive"))
      (node (ref "R70") (pin "2") (pinfunction "2_2") (pintype "passive"))
      (node (ref "R71") (pin "2") (pinfunction "2_2") (pintype "passive"))
      (node (ref "R72") (pin "2") (pinfunction "2_2") (pintype "passive"))
      (node (ref "R73") (pin "1") (pinfunction "1_1") (pintype "passive"))
      (node (ref "R74") (pin "2") (pinfunction "2_2") (pintype "passive"))
      (node (ref "R8") (pin "2") (pinfunction "2_2") (pintype "passive"))
      (node (ref "R90") (pin "2") (pinfunction "2_2") (pintype "passive"))
      (node (ref "R98") (pin "2") (pinfunction "2_2") (pintype "passive"))
      (node (ref "R99") (pin "2") (pinfunction "2_2") (pintype "passive"))
      (node (ref "RTCC") (pin "1") (pinfunction "VDD_1") (pintype "bidirectional"))
      (node (ref "STEPPER_0_CS") (pin "1") (pinfunction "VDD_1") (pintype "power_in"))
      (node (ref "STEPPER_1_CS") (pin "1") (pinfunction "VDD_1") (pintype "power_in"))
      (node (ref "TEMP_SENSOR_0") (pin "1") (pinfunction "1_1") (pintype "passive"))
      (node (ref "TEMP_SENSOR_1") (pin "1") (pinfunction "1_1") (pintype "passive"))
      (node (ref "TEMP_SENSOR_2") (pin "1") (pinfunction "1_1") (pintype "passive"))
      (node (ref "TEMP_SENSOR_3") (pin "1") (pinfunction "1_1") (pintype "passive"))
      (node (ref "TP3") (pin "TP") (pinfunction "TP_TP") (pintype "input"))
      (node (ref "U1") (pin "28") (pinfunction "VDD2_28") (pintype "power_in"))
      (node (ref "U1") (pin "7") (pinfunction "VDD1_7") (pintype "power_in"))
      (node (ref "U15") (pin "10") (pinfunction "VDD_2_10") (pintype "power_in"))
      (node (ref "U15") (pin "19") (pinfunction "AVDD_19") (pintype "power_in"))
      (node (ref "U15") (pin "26") (pinfunction "VDD_3_26") (pintype "power_in"))
      (node (ref "U15") (pin "35") (pinfunction "VUSB3V3_35") (pintype "power_in"))
      (node (ref "U15") (pin "38") (pinfunction "VDD_4_38") (pintype "power_in"))
      (node (ref "U15") (pin "57") (pinfunction "VDD_57") (pintype "power_in"))
      (node (ref "U5") (pin "13") (pinfunction "VDD_13") (pintype "power_in"))
      (node (ref "U5") (pin "8") (pinfunction "VLOGIC_8") (pintype "power_in"))
      (node (ref "UNLIMITED_POWER") (pin "1") (pinfunction "1_1") (pintype "passive"))
    )
    (net (code "2") (name "5V") (class "Default")
      (node (ref "5V_REG0") (pin "3") (pinfunction "+VOUT_3") (pintype "output"))
      (node (ref "5V_REG1") (pin "3") (pinfunction "+VOUT_3") (pintype "output"))
      (node (ref "BUZZER") (pin "+") (pinfunction "1_+") (pintype "passive"))
      (node (ref "C84") (pin "1") (pinfunction "1_1") (pintype "passive"))
      (node (ref "C86") (pin "1") (pinfunction "1_1") (pintype "passive"))
      (node (ref "DISPLAY") (pin "3") (pinfunction "3_3") (pintype "passive"))
      (node (ref "LIDAR") (pin "2") (pinfunction "2_2") (pintype "passive"))
      (node (ref "PERIMETER_WIRE") (pin "1") (pinfunction "1_1") (pintype "passive"))
      (node (ref "R121") (pin "1") (pinfunction "1_1") (pintype "passive"))
      (node (ref "R61") (pin "1") (pinfunction "1_1") (pintype "passive"))
      (node (ref "TP2") (pin "TP") (pinfunction "TP_TP") (pintype "input"))
      (node (ref "U10") (pin "4") (pinfunction "4_4") (pintype "passive"))
      (node (ref "UNLIMITED_POWER") (pin "2") (pinfunction "2_2") (pintype "passive"))
    )
    (net (code "3") (name "12V_STEPPER_0_POS") (class "Default")
      (node (ref "C36") (pin "1") (pinfunction "1_1") (pintype "passive"))
      (node (ref "C41") (pin "1") (pinfunction "1_1") (pintype "passive"))
      (node (ref "C42") (pin "1") (pinfunction "1_1") (pintype "passive"))
      (node (ref "C43") (pin "1") (pinfunction "1_1") (pintype "passive"))
      (node (ref "SD1") (pin "10") (pinfunction "VIN_10") (pintype "bidirectional"))
      (node (ref "SD1") (pin "22") (pinfunction "VIN2_22") (pintype "bidirectional"))
      (node (ref "STEPPER_0_CS") (pin "7") (pinfunction "IP-_7") (pintype "input"))
    )
    (net (code "4") (name "12V_STEPPER_1_POS") (class "Default")
      (node (ref "C53") (pin "1") (pinfunction "1_1") (pintype "passive"))
      (node (ref "C54") (pin "1") (pinfunction "1_1") (pintype "passive"))
      (node (ref "C55") (pin "1") (pinfunction "1_1") (pintype "passive"))
      (node (ref "C56") (pin "1") (pinfunction "1_1") (pintype "passive"))
      (node (ref "SD2") (pin "10") (pinfunction "VIN_10") (pintype "bidirectional"))
      (node (ref "SD2") (pin "22") (pinfunction "VIN2_22") (pintype "bidirectional"))
      (node (ref "STEPPER_1_CS") (pin "7") (pinfunction "IP-_7") (pintype "input"))
    )
    (net (code "5") (name "BATT_ADC") (class "Default")
      (node (ref "R6") (pin "1") (pinfunction "1_1") (pintype "passive"))
      (node (ref "R7") (pin "2") (pinfunction "2_2") (pintype "passive"))
      (node (ref "U1") (pin "21") (pinfunction "RA2/AN2/C2INB/C1IND/C3INB/VREF-/CVREF_21") (pintype "bidirectional"))
    )
    (net (code "6") (name "BATT_DIRECT_POS_POLE") (class "Default")
      (node (ref "BATT") (pin "TP") (pinfunction "TP_TP") (pintype "input"))
      (node (ref "BATTERY_INPUT") (pin "2") (pinfunction "+_2") (pintype "passive"))
      (node (ref "MAIN_SWITCH") (pin "1") (pinfunction "1_1") (pintype "passive"))
      (node (ref "MAIN_SWITCH") (pin "2") (pinfunction "2_2") (pintype "passive"))
    )
    (net (code "7") (name "BATT_POS") (class "Default")
      (node (ref "3V3_REG0") (pin "1") (pinfunction "+VIN_1") (pintype "input"))
      (node (ref "3V3_REG1") (pin "1") (pinfunction "+VIN_1") (pintype "input"))
      (node (ref "3V3_REG2") (pin "1") (pinfunction "+VIN_1") (pintype "input"))
      (node (ref "3V3_REG3") (pin "1") (pinfunction "+VIN_1") (pintype "input"))
      (node (ref "5V_REG0") (pin "1") (pinfunction "+VIN_1") (pintype "input"))
      (node (ref "5V_REG1") (pin "1") (pinfunction "+VIN_1") (pintype "input"))
      (node (ref "BATT_POS") (pin "TP") (pinfunction "TP_TP") (pintype "input"))
      (node (ref "C48") (pin "1") (pinfunction "1_1") (pintype "passive"))
      (node (ref "C50") (pin "1") (pinfunction "1_1") (pintype "passive"))
      (node (ref "C59") (pin "1") (pinfunction "1_1") (pintype "passive"))
      (node (ref "C60") (pin "1") (pinfunction "1_1") (pintype "passive"))
      (node (ref "C61") (pin "1") (pinfunction "1_1") (pintype "passive"))
      (node (ref "C62") (pin "1") (pinfunction "1_1") (pintype "passive"))
      (node (ref "C69") (pin "1") (pinfunction "1_1") (pintype "passive"))
      (node (ref "C71") (pin "1") (pinfunction "1_1") (pintype "passive"))
      (node (ref "C85") (pin "1") (pinfunction "1_1") (pintype "passive"))
      (node (ref "C87") (pin "1") (pinfunction "1_1") (pintype "passive"))
      (node (ref "CURRENT_SENSOR_BATT") (pin "7") (pinfunction "IP-_7") (pintype "input"))
      (node (ref "EM_LIGHT") (pin "1") (pinfunction "1_1") (pintype "passive"))
      (node (ref "FAN_0") (pin "1") (pinfunction "1_1") (pintype "passive"))
      (node (ref "FAN_1") (pin "1") (pinfunction "1_1") (pintype "passive"))
      (node (ref "FAN_2") (pin "1") (pinfunction "1_1") (pintype "passive"))
      (node (ref "FAN_3") (pin "1") (pinfunction "1_1") (pintype "passive"))
      (node (ref "MAIN_MOTOR_CS") (pin "8") (pinfunction "IP+_8") (pintype "input"))
      (node (ref "SD3") (pin "10") (pinfunction "VIN_10") (pintype "bidirectional"))
      (node (ref "SD3") (pin "22") (pinfunction "VIN2_22") (pintype "bidirectional"))
      (node (ref "STEPPER_0_CS") (pin "8") (pinfunction "IP+_8") (pintype "input"))
      (node (ref "STEPPER_1_CS") (pin "8") (pinfunction "IP+_8") (pintype "input"))
      (node (ref "U12") (pin "4") (pinfunction "4_4") (pintype "passive"))
      (node (ref "U4") (pin "4") (pinfunction "4_4") (pintype "passive"))
      (node (ref "U6") (pin "4") (pinfunction "4_4") (pintype "passive"))
      (node (ref "U7") (pin "4") (pinfunction "4_4") (pintype "passive"))
      (node (ref "U8") (pin "4") (pinfunction "4_4") (pintype "passive"))
      (node (ref "UNLIMITED_POWER") (pin "3") (pinfunction "3_3") (pintype "passive"))
    )
    (net (code "8") (name "BATT_POS_POLE") (class "Default")
      (node (ref "CUTOFF_SWITCH") (pin "3") (pinfunction "3_3") (pintype "passive"))
      (node (ref "CUTOFF_SWITCH") (pin "4") (pinfunction "4_4") (pintype "passive"))
      (node (ref "PPTC") (pin "2") (pinfunction "2_2") (pintype "passive"))
      (node (ref "Q8") (pin "3") (pinfunction "D_3") (pintype "passive"))
    )
    (net (code "9") (name "BATT_POS_POLE_SWITCH") (class "Default")
      (node (ref "CUTOFF_SWITCH") (pin "1") (pinfunction "1_1") (pintype "passive"))
      (node (ref "CUTOFF_SWITCH") (pin "2") (pinfunction "2_2") (pintype "passive"))
      (node (ref "MAIN_SWITCH") (pin "3") (pinfunction "3_3") (pintype "passive"))
      (node (ref "MAIN_SWITCH") (pin "4") (pinfunction "4_4") (pintype "passive"))
    )
    (net (code "10") (name "BLADE_MOTOR_NEG_EXT") (class "Default")
      (node (ref "D11") (pin "C") (pinfunction "C_C") (pintype "passive"))
      (node (ref "D9") (pin "A") (pinfunction "A_A") (pintype "passive"))
      (node (ref "MAIN_MOTOR") (pin "3") (pinfunction "3_3") (pintype "passive"))
      (node (ref "MAIN_MOTOR") (pin "4") (pinfunction "4_4") (pintype "passive"))
      (node (ref "NMOS7") (pin "5") (pinfunction "D_5") (pintype "passive"))
      (node (ref "NMOS7") (pin "6") (pinfunction "D_6") (pintype "passive"))
      (node (ref "NMOS7") (pin "7") (pinfunction "D_7") (pintype "passive"))
      (node (ref "NMOS7") (pin "8") (pinfunction "D_8") (pintype "passive"))
      (node (ref "NMOS7") (pin "TH") (pinfunction "TH_TH") (pintype "passive"))
    )
    (net (code "11") (name "BLADE_MOTOR_POS") (class "Default")
      (node (ref "D10") (pin "A") (pinfunction "A_A") (pintype "passive"))
      (node (ref "MAIN_MOTOR_CS") (pin "7") (pinfunction "IP-_7") (pintype "input"))
      (node (ref "U11") (pin "4") (pinfunction "4_4") (pintype "passive"))
    )
    (net (code "12") (name "BLADE_MOTOR_POS_EXT") (class "Default")
      (node (ref "D10") (pin "C") (pinfunction "C_C") (pintype "passive"))
      (node (ref "D9") (pin "C") (pinfunction "C_C") (pintype "passive"))
      (node (ref "MAIN_MOTOR") (pin "1") (pinfunction "1_1") (pintype "passive"))
      (node (ref "MAIN_MOTOR") (pin "2") (pinfunction "2_2") (pintype "passive"))
    )
    (net (code "13") (name "CP2102_RXD") (class "Default")
      (node (ref "CP2102") (pin "25") (pinfunction "RXD_25") (pintype "input"))
      (node (ref "CP2102_RX") (pin "TP") (pinfunction "TP_TP") (pintype "input"))
      (node (ref "MCU_3_ESP32") (pin "35") (pinfunction "U0TXD_35") (pintype "bidirectional"))
    )
    (net (code "14") (name "CP2102_TXD") (class "Default")
      (node (ref "CP2102") (pin "26") (pinfunction "TXD_26") (pintype "output"))
      (node (ref "CP2102_TX") (pin "TP") (pinfunction "TP_TP") (pintype "input"))
      (node (ref "MCU_3_ESP32") (pin "34") (pinfunction "U0RXD_34") (pintype "bidirectional"))
    )
    (net (code "15") (name "CP_RST") (class "Default")
      (node (ref "CP2102") (pin "9") (pinfunction "~{RST}_9") (pintype "bidirectional"))
      (node (ref "R50") (pin "1") (pinfunction "1_1") (pintype "passive"))
    )
    (net (code "16") (name "CP_SUSPEND") (class "Default")
      (node (ref "CP2102") (pin "12") (pinfunction "SUSPEND_12") (pintype "output"))
    )
    (net (code "17") (name "CURRENT_SENSOR_3_POS") (class "Default")
      (node (ref "C2") (pin "+") (pinfunction "+_+") (pintype "passive"))
      (node (ref "C3") (pin "+") (pinfunction "+_+") (pintype "passive"))
      (node (ref "C72") (pin "+") (pinfunction "+_+") (pintype "passive"))
      (node (ref "CURRENT_SENSOR_BATT") (pin "8") (pinfunction "IP+_8") (pintype "input"))
      (node (ref "L1") (pin "1") (pinfunction "1_1") (pintype "bidirectional"))
      (node (ref "R6") (pin "2") (pinfunction "2_2") (pintype "passive"))
    )
    (net (code "18") (name "D_N") (class "Default")
      (node (ref "CP2102") (pin "5") (pinfunction "D-_5") (pintype "bidirectional"))
      (node (ref "D5") (pin "C") (pinfunction "C_C") (pintype "passive"))
      (node (ref "MICROUSB") (pin "2") (pinfunction "D-_2") (pintype "bidirectional"))
    )
    (net (code "19") (name "D_P") (class "Default")
      (node (ref "CP2102") (pin "4") (pinfunction "D+_4") (pintype "bidirectional"))
      (node (ref "D4") (pin "C") (pinfunction "C_C") (pintype "passive"))
      (node (ref "MICROUSB") (pin "3") (pinfunction "D+_3") (pintype "bidirectional"))
    )
    (net (code "20") (name "EP") (class "Default")
      (node (ref "U5") (pin "25") (pinfunction "EP_25") (pintype "power_in"))
    )
    (net (code "21") (name "EXTERNAL_GND") (class "Default")
      (node (ref "EXTERNAL_INPUT") (pin "1") (pinfunction "-_1") (pintype "passive"))
      (node (ref "U13") (pin "2") (pinfunction "2_2") (pintype "passive"))
      (node (ref "U9") (pin "3") (pinfunction "3_3") (pintype "passive"))
    )
    (net (code "22") (name "EXTERNAL_INPUT_SENSE") (class "Default")
      (node (ref "R79") (pin "1") (pinfunction "1_1") (pintype "passive"))
      (node (ref "U1") (pin "15") (pinfunction "RB5/CCP5/PMA0/KBI1/RP8_15") (pintype "bidirectional"))
      (node (ref "U13") (pin "3") (pinfunction "3_3") (pintype "passive"))
    )
    (net (code "23") (name "EXTERNAL_POS") (class "Default")
      (node (ref "EXTERNAL_INPUT") (pin "2") (pinfunction "+_2") (pintype "passive"))
      (node (ref "Q8") (pin "2") (pinfunction "S_2") (pintype "passive"))
      (node (ref "R77") (pin "1") (pinfunction "1_1") (pintype "passive"))
      (node (ref "R78") (pin "2") (pinfunction "2_2") (pintype "passive"))
    )
    (net (code "24") (name "GND") (class "Default")
      (node (ref "3V3_REG0") (pin "2") (pinfunction "GND_2") (pintype "power_in"))
      (node (ref "3V3_REG1") (pin "2") (pinfunction "GND_2") (pintype "power_in"))
      (node (ref "3V3_REG2") (pin "2") (pinfunction "GND_2") (pintype "power_in"))
      (node (ref "3V3_REG3") (pin "2") (pinfunction "GND_2") (pintype "power_in"))
      (node (ref "5V_REG0") (pin "2") (pinfunction "GND_2") (pintype "power_in"))
      (node (ref "5V_REG1") (pin "2") (pinfunction "GND_2") (pintype "power_in"))
      (node (ref "BATT1") (pin "MINUS") (pinfunction "MINUS_MINUS") (pintype "bidirectional"))
      (node (ref "BATTERY_INPUT") (pin "1") (pinfunction "-_1") (pintype "passive"))
      (node (ref "BOOT") (pin "3") (pinfunction "2_3") (pintype "passive"))
      (node (ref "BUTTONS") (pin "10") (pinfunction "10_10") (pintype "passive"))
      (node (ref "C1") (pin "2") (pinfunction "2_2") (pintype "passive"))
      (node (ref "C10") (pin "2") (pinfunction "2_2") (pintype "passive"))
      (node (ref "C11") (pin "2") (pinfunction "2_2") (pintype "passive"))
      (node (ref "C12") (pin "1") (pinfunction "1_1") (pintype "passive"))
      (node (ref "C13") (pin "2") (pinfunction "2_2") (pintype "passive"))
      (node (ref "C14") (pin "2") (pinfunction "2_2") (pintype "passive"))
      (node (ref "C15") (pin "2") (pinfunction "2_2") (pintype "passive"))
      (node (ref "C18") (pin "2") (pinfunction "2_2") (pintype "passive"))
      (node (ref "C19") (pin "2") (pinfunction "2_2") (pintype "passive"))
      (node (ref "C2") (pin "-") (pinfunction "-_-") (pintype "passive"))
      (node (ref "C20") (pin "1") (pinfunction "1_1") (pintype "passive"))
      (node (ref "C21") (pin "2") (pinfunction "2_2") (pintype "passive"))
      (node (ref "C22") (pin "2") (pinfunction "2_2") (pintype "passive"))
      (node (ref "C23") (pin "2") (pinfunction "2_2") (pintype "passive"))
      (node (ref "C24") (pin "2") (pinfunction "2_2") (pintype "passive"))
      (node (ref "C25") (pin "2") (pinfunction "2_2") (pintype "passive"))
      (node (ref "C26") (pin "1") (pinfunction "1_1") (pintype "passive"))
      (node (ref "C27") (pin "2") (pinfunction "2_2") (pintype "passive"))
      (node (ref "C28") (pin "2") (pinfunction "2_2") (pintype "passive"))
      (node (ref "C29") (pin "1") (pinfunction "1_1") (pintype "passive"))
      (node (ref "C3") (pin "-") (pinfunction "-_-") (pintype "passive"))
      (node (ref "C30") (pin "2") (pinfunction "2_2") (pintype "passive"))
      (node (ref "C31") (pin "2") (pinfunction "2_2") (pintype "passive"))
      (node (ref "C32") (pin "1") (pinfunction "1_1") (pintype "passive"))
      (node (ref "C33") (pin "2") (pinfunction "2_2") (pintype "passive"))
      (node (ref "C34") (pin "2") (pinfunction "2_2") (pintype "passive"))
      (node (ref "C37") (pin "1") (pinfunction "1_1") (pintype "passive"))
      (node (ref "C38") (pin "1") (pinfunction "1_1") (pintype "passive"))
      (node (ref "C39") (pin "2") (pinfunction "2_2") (pintype "passive"))
      (node (ref "C4") (pin "2") (pinfunction "2_2") (pintype "passive"))
      (node (ref "C40") (pin "2") (pinfunction "2_2") (pintype "passive"))
      (node (ref "C41") (pin "2") (pinfunction "2_2") (pintype "passive"))
      (node (ref "C42") (pin "2") (pinfunction "2_2") (pintype "passive"))
      (node (ref "C43") (pin "2") (pinfunction "2_2") (pintype "passive"))
      (node (ref "C44") (pin "2") (pinfunction "2_2") (pintype "passive"))
      (node (ref "C45") (pin "2") (pinfunction "2_2") (pintype "passive"))
      (node (ref "C46") (pin "1") (pinfunction "1_1") (pintype "passive"))
      (node (ref "C47") (pin "2") (pinfunction "2_2") (pintype "passive"))
      (node (ref "C48") (pin "2") (pinfunction "2_2") (pintype "passive"))
      (node (ref "C49") (pin "2") (pinfunction "2_2") (pintype "passive"))
      (node (ref "C5") (pin "2") (pinfunction "2_2") (pintype "passive"))
      (node (ref "C50") (pin "2") (pinfunction "2_2") (pintype "passive"))
      (node (ref "C51") (pin "2") (pinfunction "2_2") (pintype "passive"))
      (node (ref "C54") (pin "2") (pinfunction "2_2") (pintype "passive"))
      (node (ref "C55") (pin "2") (pinfunction "2_2") (pintype "passive"))
      (node (ref "C56") (pin "2") (pinfunction "2_2") (pintype "passive"))
      (node (ref "C57") (pin "2") (pinfunction "2_2") (pintype "passive"))
      (node (ref "C6") (pin "2") (pinfunction "2_2") (pintype "passive"))
      (node (ref "C60") (pin "2") (pinfunction "2_2") (pintype "passive"))
      (node (ref "C61") (pin "2") (pinfunction "2_2") (pintype "passive"))
      (node (ref "C62") (pin "2") (pinfunction "2_2") (pintype "passive"))
      (node (ref "C63") (pin "1") (pinfunction "1_1") (pintype "passive"))
      (node (ref "C64") (pin "1") (pinfunction "1_1") (pintype "passive"))
      (node (ref "C65") (pin "1") (pinfunction "1_1") (pintype "passive"))
      (node (ref "C66") (pin "1") (pinfunction "1_1") (pintype "passive"))
      (node (ref "C67") (pin "1") (pinfunction "1_1") (pintype "passive"))
      (node (ref "C68") (pin "2") (pinfunction "2_2") (pintype "passive"))
      (node (ref "C69") (pin "2") (pinfunction "2_2") (pintype "passive"))
      (node (ref "C7") (pin "2") (pinfunction "2_2") (pintype "passive"))
      (node (ref "C70") (pin "2") (pinfunction "2_2") (pintype "passive"))
      (node (ref "C71") (pin "2") (pinfunction "2_2") (pintype "passive"))
      (node (ref "C72") (pin "-") (pinfunction "-_-") (pintype "passive"))
      (node (ref "C73") (pin "2") (pinfunction "2_2") (pintype "passive"))
      (node (ref "C74") (pin "2") (pinfunction "2_2") (pintype "passive"))
      (node (ref "C75") (pin "2") (pinfunction "2_2") (pintype "passive"))
      (node (ref "C76") (pin "2") (pinfunction "2_2") (pintype "passive"))
      (node (ref "C77") (pin "2") (pinfunction "2_2") (pintype "passive"))
      (node (ref "C78") (pin "2") (pinfunction "2_2") (pintype "passive"))
      (node (ref "C79") (pin "2") (pinfunction "2_2") (pintype "passive"))
      (node (ref "C8") (pin "1") (pinfunction "1_1") (pintype "passive"))
      (node (ref "C80") (pin "-") (pinfunction "-_-") (pintype "passive"))
      (node (ref "C81") (pin "2") (pinfunction "2_2") (pintype "passive"))
      (node (ref "C82") (pin "2") (pinfunction "2_2") (pintype "passive"))
      (node (ref "C84") (pin "2") (pinfunction "2_2") (pintype "passive"))
      (node (ref "C85") (pin "2") (pinfunction "2_2") (pintype "passive"))
      (node (ref "C86") (pin "2") (pinfunction "2_2") (pintype "passive"))
      (node (ref "C87") (pin "2") (pinfunction "2_2") (pintype "passive"))
      (node (ref "C9") (pin "1") (pinfunction "1_1") (pintype "passive"))
      (node (ref "CAMERA") (pin "4") (pinfunction "4_4") (pintype "passive"))
      (node (ref "CP2102") (pin "1") (pinfunction "DCD_1") (pintype "input"))
      (node (ref "CP2102") (pin "2") (pinfunction "RI_2") (pintype "input"))
      (node (ref "CP2102") (pin "23") (pinfunction "CTS_23") (pintype "input"))
      (node (ref "CP2102") (pin "27") (pinfunction "DSR_27") (pintype "input"))
      (node (ref "CP2102") (pin "3") (pinfunction "GND_3") (pintype "power_in"))
      (node (ref "CP2102") (pin "EXP") (pinfunction "GND_EXP") (pintype "power_in"))
      (node (ref "CP2102") (pin "M") (pinfunction "GND_M") (pintype "power_in"))
      (node (ref "CURRENT_SENSOR_BATT") (pin "2") (pinfunction "GND_2") (pintype "power_in"))
      (node (ref "D11") (pin "A") (pinfunction "A_A") (pintype "passive"))
      (node (ref "D2") (pin "C") (pinfunction "C_C") (pintype "passive"))
      (node (ref "D3") (pin "A") (pinfunction "A_A") (pintype "passive"))
      (node (ref "D4") (pin "A") (pinfunction "A_A") (pintype "passive"))
      (node (ref "D5") (pin "A") (pinfunction "A_A") (pintype "passive"))
      (node (ref "DISPLAY") (pin "4") (pinfunction "4_4") (pintype "passive"))
      (node (ref "EN") (pin "3") (pinfunction "2_3") (pintype "passive"))
      (node (ref "GPS") (pin "2") (pinfunction "2_2") (pintype "passive"))
      (node (ref "IC1") (pin "27") (pinfunction "VSS_27") (pintype "passive"))
      (node (ref "IC1") (pin "8") (pinfunction "VSS_2_8") (pintype "passive"))
      (node (ref "L1") (pin "3") (pinfunction "3_3") (pintype "bidirectional"))
      (node (ref "LED1") (pin "C") (pinfunction "C_C") (pintype "passive"))
      (node (ref "LED12") (pin "C") (pinfunction "C_C") (pintype "passive"))
      (node (ref "LED13") (pin "C") (pinfunction "C_C") (pintype "passive"))
      (node (ref "LED14") (pin "C") (pinfunction "C_C") (pintype "passive"))
      (node (ref "LED15") (pin "C") (pinfunction "C_C") (pintype "passive"))
      (node (ref "LED16") (pin "C") (pinfunction "C_C") (pintype "passive"))
      (node (ref "LED17") (pin "C") (pinfunction "C_C") (pintype "passive"))
      (node (ref "LED18") (pin "C") (pinfunction "C_C") (pintype "passive"))
      (node (ref "LED19") (pin "C") (pinfunction "C_C") (pintype "passive"))
      (node (ref "LED2") (pin "C") (pinfunction "C_C") (pintype "passive"))
      (node (ref "LED20") (pin "C") (pinfunction "C_C") (pintype "passive"))
      (node (ref "LED21") (pin "C") (pinfunction "C_C") (pintype "passive"))
      (node (ref "LED22") (pin "C") (pinfunction "C_C") (pintype "passive"))
      (node (ref "LED23") (pin "C") (pinfunction "C_C") (pintype "passive"))
      (node (ref "LED24") (pin "C") (pinfunction "C_C") (pintype "passive"))
      (node (ref "LED25") (pin "C") (pinfunction "C_C") (pintype "passive"))
      (node (ref "LED26") (pin "C") (pinfunction "C_C") (pintype "passive"))
      (node (ref "LED27") (pin "C") (pinfunction "C_C") (pintype "passive"))
      (node (ref "LED3") (pin "C") (pinfunction "C_C") (pintype "passive"))
      (node (ref "LED4") (pin "C") (pinfunction "C_C") (pintype "passive"))
      (node (ref "LED5") (pin "C") (pinfunction "C_C") (pintype "passive"))
      (node (ref "LED7") (pin "C") (pinfunction "C_C") (pintype "passive"))
      (node (ref "LED8") (pin "C") (pinfunction "C_C") (pintype "passive"))
      (node (ref "LIDAR") (pin "1") (pinfunction "1_1") (pintype "passive"))
      (node (ref "LIGHT_SENSOR") (pin "2") (pinfunction "2_2") (pintype "passive"))
      (node (ref "LIMIT_SWITCH_DOWN") (pin "3") (pinfunction "3_3") (pintype "passive"))
      (node (ref "LIMIT_SWITCH_UP") (pin "3") (pinfunction "3_3") (pintype "passive"))
      (node (ref "MAIN_MOTOR_CS") (pin "2") (pinfunction "GND_2") (pintype "power_in"))
      (node (ref "MCU_0") (pin "P$1") (pinfunction "1_P$1") (pintype "bidirectional"))
      (node (ref "MCU_1") (pin "P$1") (pinfunction "1_P$1") (pintype "bidirectional"))
      (node (ref "MCU_2") (pin "P$1") (pinfunction "1_P$1") (pintype "bidirectional"))
      (node (ref "MCU_3_ESP32") (pin "1") (pinfunction "GND_1") (pintype "power_in"))
      (node (ref "MCU_3_ESP32") (pin "15") (pinfunction "GND_15") (pintype "power_in"))
      (node (ref "MCU_3_ESP32") (pin "38") (pinfunction "GND_38") (pintype "power_in"))
      (node (ref "MCU_3_ESP32") (pin "GND") (pinfunction "GND_GND") (pintype "power_in"))
      (node (ref "MICROUSB") (pin "4") (pinfunction "ID_4") (pintype "bidirectional"))
      (node (ref "MICROUSB") (pin "5") (pinfunction "GND_5") (pintype "power_in"))
      (node (ref "MICROUSB") (pin "S1") (pinfunction "SHIELD_S1") (pintype "power_in"))
      (node (ref "MICROUSB") (pin "S2") (pinfunction "SHIELD_S2") (pintype "power_in"))
      (node (ref "MICROUSB") (pin "S3") (pinfunction "SHIELD_S3") (pintype "power_in"))
      (node (ref "MICROUSB") (pin "S4") (pinfunction "SHIELD_S4") (pintype "power_in"))
      (node (ref "NMOS1") (pin "1") (pinfunction "S_1") (pintype "passive"))
      (node (ref "NMOS1") (pin "2") (pinfunction "S_2") (pintype "passive"))
      (node (ref "NMOS1") (pin "3") (pinfunction "S_3") (pintype "passive"))
      (node (ref "NMOS2") (pin "1") (pinfunction "S_1") (pintype "passive"))
      (node (ref "NMOS2") (pin "2") (pinfunction "S_2") (pintype "passive"))
      (node (ref "NMOS2") (pin "3") (pinfunction "S_3") (pintype "passive"))
      (node (ref "NMOS3") (pin "1") (pinfunction "S_1") (pintype "passive"))
      (node (ref "NMOS3") (pin "2") (pinfunction "S_2") (pintype "passive"))
      (node (ref "NMOS3") (pin "3") (pinfunction "S_3") (pintype "passive"))
      (node (ref "NMOS4") (pin "1") (pinfunction "S_1") (pintype "passive"))
      (node (ref "NMOS4") (pin "2") (pinfunction "S_2") (pintype "passive"))
      (node (ref "NMOS4") (pin "3") (pinfunction "S_3") (pintype "passive"))
      (node (ref "NMOS5") (pin "1") (pinfunction "S_1") (pintype "passive"))
      (node (ref "NMOS5") (pin "2") (pinfunction "S_2") (pintype "passive"))
      (node (ref "NMOS5") (pin "3") (pinfunction "S_3") (pintype "passive"))
      (node (ref "NMOS6") (pin "1") (pinfunction "S_1") (pintype "passive"))
      (node (ref "NMOS6") (pin "2") (pinfunction "S_2") (pintype "passive"))
      (node (ref "NMOS6") (pin "3") (pinfunction "S_3") (pintype "passive"))
      (node (ref "NMOS7") (pin "1") (pinfunction "S_1") (pintype "passive"))
      (node (ref "NMOS7") (pin "2") (pinfunction "S_2") (pintype "passive"))
      (node (ref "NMOS7") (pin "3") (pinfunction "S_3") (pintype "passive"))
      (node (ref "PERIMETER_WIRE") (pin "3") (pinfunction "3_3") (pintype "passive"))
      (node (ref "PERIMETER_WIRE") (pin "4") (pinfunction "4_4") (pintype "passive"))
      (node (ref "R1") (pin "1") (pinfunction "1_1") (pintype "passive"))
      (node (ref "R100") (pin "2") (pinfunction "2_2") (pintype "passive"))
      (node (ref "R109") (pin "1") (pinfunction "1_1") (pintype "passive"))
      (node (ref "R110") (pin "1") (pinfunction "1_1") (pintype "passive"))
      (node (ref "R111") (pin "2") (pinfunction "2_2") (pintype "passive"))
      (node (ref "R112") (pin "2") (pinfunction "2_2") (pintype "passive"))
      (node (ref "R113") (pin "2") (pinfunction "2_2") (pintype "passive"))
      (node (ref "R114") (pin "2") (pinfunction "2_2") (pintype "passive"))
      (node (ref "R115") (pin "2") (pinfunction "2_2") (pintype "passive"))
      (node (ref "R116") (pin "2") (pinfunction "2_2") (pintype "passive"))
      (node (ref "R117") (pin "2") (pinfunction "2_2") (pintype "passive"))
      (node (ref "R118") (pin "2") (pinfunction "2_2") (pintype "passive"))
      (node (ref "R2") (pin "1") (pinfunction "1_1") (pintype "passive"))
      (node (ref "R23") (pin "2") (pinfunction "2_2") (pintype "passive"))
      (node (ref "R3") (pin "1") (pinfunction "1_1") (pintype "passive"))
      (node (ref "R35") (pin "2") (pinfunction "2_2") (pintype "passive"))
      (node (ref "R41") (pin "2") (pinfunction "2_2") (pintype "passive"))
      (node (ref "R42") (pin "1") (pinfunction "1_1") (pintype "passive"))
      (node (ref "R46") (pin "2") (pinfunction "2_2") (pintype "passive"))
      (node (ref "R49") (pin "1") (pinfunction "1_1") (pintype "passive"))
      (node (ref "R54") (pin "2") (pinfunction "2_2") (pintype "passive"))
      (node (ref "R63") (pin "2") (pinfunction "2_2") (pintype "passive"))
      (node (ref "R65") (pin "2") (pinfunction "2_2") (pintype "passive"))
      (node (ref "R67") (pin "2") (pinfunction "2_2") (pintype "passive"))
      (node (ref "R68") (pin "2") (pinfunction "2_2") (pintype "passive"))
      (node (ref "R7") (pin "1") (pinfunction "1_1") (pintype "passive"))
      (node (ref "R76") (pin "2") (pinfunction "2_2") (pintype "passive"))
      (node (ref "R79") (pin "2") (pinfunction "2_2") (pintype "passive"))
      (node (ref "RAIN_SENSOR") (pin "2") (pinfunction "2_2") (pintype "passive"))
      (node (ref "RGB_LED") (pin "4") (pinfunction "4_4") (pintype "passive"))
      (node (ref "RTCC") (pin "7") (pinfunction "VSS_7") (pintype "bidirectional"))
      (node (ref "SD1") (pin "12") (pinfunction "GND2_12") (pintype "bidirectional"))
      (node (ref "SD1") (pin "20") (pinfunction "GND3_20") (pintype "bidirectional"))
      (node (ref "SD1") (pin "24") (pinfunction "GND4_24") (pintype "bidirectional"))
      (node (ref "SD1") (pin "25") (pinfunction "PAD_25") (pintype "bidirectional"))
      (node (ref "SD1") (pin "4") (pinfunction "AGND_4") (pintype "bidirectional"))
      (node (ref "SD1") (pin "8") (pinfunction "GND_8") (pintype "bidirectional"))
      (node (ref "SD2") (pin "12") (pinfunction "GND2_12") (pintype "bidirectional"))
      (node (ref "SD2") (pin "20") (pinfunction "GND3_20") (pintype "bidirectional"))
      (node (ref "SD2") (pin "24") (pinfunction "GND4_24") (pintype "bidirectional"))
      (node (ref "SD2") (pin "25") (pinfunction "PAD_25") (pintype "bidirectional"))
      (node (ref "SD2") (pin "4") (pinfunction "AGND_4") (pintype "bidirectional"))
      (node (ref "SD2") (pin "8") (pinfunction "GND_8") (pintype "bidirectional"))
      (node (ref "SD3") (pin "12") (pinfunction "GND2_12") (pintype "bidirectional"))
      (node (ref "SD3") (pin "20") (pinfunction "GND3_20") (pintype "bidirectional"))
      (node (ref "SD3") (pin "24") (pinfunction "GND4_24") (pintype "bidirectional"))
      (node (ref "SD3") (pin "25") (pinfunction "PAD_25") (pintype "bidirectional"))
      (node (ref "SD3") (pin "4") (pinfunction "AGND_4") (pintype "bidirectional"))
      (node (ref "SD3") (pin "8") (pinfunction "GND_8") (pintype "bidirectional"))
      (node (ref "STEPPER_0_CS") (pin "2") (pinfunction "GND_2") (pintype "power_in"))
      (node (ref "STEPPER_1_CS") (pin "2") (pinfunction "GND_2") (pintype "power_in"))
      (node (ref "T2") (pin "E") (pinfunction "E_E") (pintype "passive"))
      (node (ref "TEMP_SENSOR_0") (pin "3") (pinfunction "3_3") (pintype "passive"))
      (node (ref "TEMP_SENSOR_1") (pin "3") (pinfunction "3_3") (pintype "passive"))
      (node (ref "TEMP_SENSOR_2") (pin "3") (pinfunction "3_3") (pintype "passive"))
      (node (ref "TEMP_SENSOR_3") (pin "3") (pinfunction "3_3") (pintype "passive"))
      (node (ref "TILT_SENSOR") (pin "1") (pinfunction "1_1") (pintype "passive"))
      (node (ref "TVS25V") (pin "A") (pinfunction "A_A") (pintype "passive"))
      (node (ref "U1") (pin "29") (pinfunction "VSS2_29") (pintype "power_in"))
      (node (ref "U1") (pin "6") (pinfunction "VSS1_6") (pintype "power_in"))
      (node (ref "U10") (pin "2") (pinfunction "2_2") (pintype "passive"))
      (node (ref "U11") (pin "2") (pinfunction "2_2") (pintype "passive"))
      (node (ref "U12") (pin "2") (pinfunction "2_2") (pintype "passive"))
      (node (ref "U15") (pin "20") (pinfunction "AVSS_20") (pintype "passive"))
      (node (ref "U15") (pin "25") (pinfunction "VSS_3_25") (pintype "passive"))
      (node (ref "U15") (pin "41") (pinfunction "VSS_4_41") (pintype "passive"))
      (node (ref "U15") (pin "56") (pinfunction "VSS_56") (pintype "passive"))
      (node (ref "U15") (pin "9") (pinfunction "VSS_2_9") (pintype "passive"))
      (node (ref "U4") (pin "2") (pinfunction "2_2") (pintype "passive"))
      (node (ref "U5") (pin "11") (pinfunction "FSYNC_11") (pintype "input"))
      (node (ref "U5") (pin "18") (pinfunction "GND_18") (pintype "power_in"))
      (node (ref "U5") (pin "9") (pinfunction "AD0_9") (pintype "bidirectional"))
      (node (ref "U6") (pin "2") (pinfunction "2_2") (pintype "passive"))
      (node (ref "U7") (pin "2") (pinfunction "2_2") (pintype "passive"))
      (node (ref "U8") (pin "2") (pinfunction "2_2") (pintype "passive"))
      (node (ref "U9") (pin "2") (pinfunction "2_2") (pintype "passive"))
      (node (ref "UNLIMITED_POWER") (pin "4") (pinfunction "4_4") (pintype "passive"))
      (node (ref "UNLIMITED_POWER") (pin "5") (pinfunction "5_5") (pintype "passive"))
      (node (ref "X5") (pin "3") (pinfunction "3_3") (pintype "input"))
      (node (ref "X5") (pin "6") (pinfunction "6_6") (pintype "input"))
      (node (ref "X5") (pin "COM_TERM") (pinfunction "COM_TERM_COM_TERM") (pintype "input"))
    )
    (net (code "25") (name "GPS_PPS") (class "Default")
      (node (ref "GPS") (pin "5") (pinfunction "5_5") (pintype "passive"))
    )
    (net (code "26") (name "GPS_RXD") (class "Default")
      (node (ref "GPS") (pin "4") (pinfunction "4_4") (pintype "passive"))
      (node (ref "GPS_RX") (pin "TP") (pinfunction "TP_TP") (pintype "input"))
      (node (ref "U15") (pin "22") (pinfunction "OA3IN-/AN7/CVD7/C3IN1-/C4IN1-/RPC1/PMA7/RC1_22") (pintype "bidirectional"))
    )
    (net (code "27") (name "GPS_TXD") (class "Default")
      (node (ref "GPS") (pin "3") (pinfunction "3_3") (pintype "passive"))
      (node (ref "GPS_TX") (pin "TP") (pinfunction "TP_TP") (pintype "input"))
      (node (ref "U15") (pin "21") (pinfunction "OA3OUT/AN6/CVD6/C3IN4-/C4IN1+/C4IN4-/RPC0/RC0_21") (pintype "bidirectional"))
    )
    (net (code "28") (name "LIDAR_RX") (class "Default")
      (node (ref "LIDAR") (pin "4") (pinfunction "4_4") (pintype "passive"))
      (node (ref "LIDAR_RX") (pin "TP") (pinfunction "TP_TP") (pintype "input"))
      (node (ref "U15") (pin "60") (pinfunction "RPB10/PWM3H/PMD0/RB10_60") (pintype "bidirectional"))
    )
    (net (code "29") (name "LIDAR_TX") (class "Default")
      (node (ref "LIDAR") (pin "7") (pinfunction "7_7") (pintype "passive"))
      (node (ref "LIDAR_TX") (pin "TP") (pinfunction "TP_TP") (pintype "input"))
      (node (ref "U15") (pin "43") (pinfunction "PGD2/RPB5/SDA3/USBID1/RB5_43") (pintype "bidirectional"))
    )
    (net (code "30") (name "LIMIT_SWITCH_BOTTOM") (class "Default")
      (node (ref "IC1") (pin "23") (pinfunction "AN12/RP12/CN14/PMD0/RB12_23") (pintype "passive"))
      (node (ref "R108") (pin "1") (pinfunction "1_1") (pintype "passive"))
    )
    (net (code "31") (name "LIMIT_SWITCH_UPPER") (class "Default")
      (node (ref "IC1") (pin "24") (pinfunction "AN11/RP13/CN13/PMRD/RB13_24") (pintype "passive"))
      (node (ref "R107") (pin "1") (pinfunction "1_1") (pintype "passive"))
    )
    (net (code "32") (name "MCU_0_BUZZER") (class "Default")
      (node (ref "R24") (pin "1") (pinfunction "1_1") (pintype "passive"))
      (node (ref "U1") (pin "35") (pinfunction "RC1/CCP8/T1OSI/RP12_35") (pintype "bidirectional"))
    )
    (net (code "33") (name "MCU_0_CHARGING_INPUT_ENABLE") (class "Default")
      (node (ref "R120") (pin "1") (pinfunction "1_1") (pintype "passive"))
      (node (ref "R85") (pin "1") (pinfunction "1_1") (pintype "passive"))
      (node (ref "U1") (pin "41") (pinfunction "RD3/PMD3/RP20_41") (pintype "bidirectional"))
    )
    (net (code "34") (name "MCU_0_CURRENT_SENSOR_0") (class "Default")
      (node (ref "CS_STEP0") (pin "TP") (pinfunction "TP_TP") (pintype "input"))
      (node (ref "R15") (pin "2") (pinfunction "2_2") (pintype "passive"))
      (node (ref "U1") (pin "19") (pinfunction "RA0/AN0/C1INA/ULPWU/PMA6/RP0_19") (pintype "bidirectional"))
    )
    (net (code "35") (name "MCU_0_CURRENT_SENSOR_1") (class "Default")
      (node (ref "CS_STEP1") (pin "TP") (pinfunction "TP_TP") (pintype "input"))
      (node (ref "R17") (pin "2") (pinfunction "2_2") (pintype "passive"))
      (node (ref "U1") (pin "20") (pinfunction "RA1/AN1/C2INA/VBG/CTDIN/PMA7/RP1_20") (pintype "bidirectional"))
    )
    (net (code "36") (name "MCU_0_CURRENT_SENSOR_2") (class "Default")
      (node (ref "CS_MAIN_MOT") (pin "TP") (pinfunction "TP_TP") (pintype "input"))
      (node (ref "R19") (pin "2") (pinfunction "2_2") (pintype "passive"))
      (node (ref "U1") (pin "25") (pinfunction "RE0/AN5/PMRD_25") (pintype "bidirectional"))
    )
    (net (code "37") (name "MCU_0_CURRENT_SENSOR_3") (class "Default")
      (node (ref "CS_BATT") (pin "TP") (pinfunction "TP_TP") (pintype "input"))
      (node (ref "R21") (pin "2") (pinfunction "2_2") (pintype "passive"))
      (node (ref "U1") (pin "26") (pinfunction "RE1/AN6/PMWR_26") (pintype "bidirectional"))
    )
    (net (code "38") (name "MCU_0_EMERGENCY_LIGHT") (class "Default")
      (node (ref "R119") (pin "1") (pinfunction "1_1") (pintype "passive"))
      (node (ref "U1") (pin "32") (pinfunction "RC0/T1OSO/T1CKI/RP11_32") (pintype "bidirectional"))
    )
    (net (code "39") (name "MCU_0_FAN_0") (class "Default")
      (node (ref "R22") (pin "1") (pinfunction "1_1") (pintype "passive"))
      (node (ref "R86") (pin "1") (pinfunction "1_1") (pintype "passive"))
      (node (ref "U1") (pin "2") (pinfunction "RD4/PMD4/RP21_2") (pintype "bidirectional"))
    )
    (net (code "40") (name "MCU_0_FAN_1") (class "Default")
      (node (ref "R51") (pin "1") (pinfunction "1_1") (pintype "passive"))
      (node (ref "R87") (pin "1") (pinfunction "1_1") (pintype "passive"))
      (node (ref "U1") (pin "3") (pinfunction "RD5/PMD5/RP22_3") (pintype "bidirectional"))
    )
    (net (code "41") (name "MCU_0_FAN_2") (class "Default")
      (node (ref "R53") (pin "1") (pinfunction "1_1") (pintype "passive"))
      (node (ref "R88") (pin "1") (pinfunction "1_1") (pintype "passive"))
      (node (ref "U1") (pin "4") (pinfunction "RD6/PMD6/RP23_4") (pintype "bidirectional"))
    )
    (net (code "42") (name "MCU_0_FAN_3") (class "Default")
      (node (ref "R52") (pin "1") (pinfunction "1_1") (pintype "passive"))
      (node (ref "R89") (pin "1") (pinfunction "1_1") (pintype "passive"))
      (node (ref "U1") (pin "5") (pinfunction "RD7/PMD7/RP24_5") (pintype "bidirectional"))
    )
    (net (code "43") (name "MCU_0_LED0") (class "Default")
      (node (ref "R82") (pin "1") (pinfunction "1_1") (pintype "passive"))
      (node (ref "U1") (pin "38") (pinfunction "RD0/PMD0/SCL2_38") (pintype "bidirectional"))
    )
    (net (code "44") (name "MCU_0_LED1") (class "Default")
      (node (ref "R83") (pin "1") (pinfunction "1_1") (pintype "passive"))
      (node (ref "U1") (pin "39") (pinfunction "RD1/PMD1/SDA2_39") (pintype "bidirectional"))
    )
    (net (code "45") (name "MCU_0_LED2") (class "Default")
      (node (ref "R80") (pin "1") (pinfunction "1_1") (pintype "passive"))
      (node (ref "U1") (pin "40") (pinfunction "RD2/PMD2/RP1_40") (pintype "bidirectional"))
    )
    (net (code "46") (name "MCU_0_LIGHT_SENSOR") (class "Default")
      (node (ref "R66") (pin "1") (pinfunction "1_1") (pintype "passive"))
      (node (ref "U1") (pin "24") (pinfunction "RA5/AN4/C1INC/SS1~{/HLVDIN/RP2}_24") (pintype "bidirectional"))
    )
    (net (code "47") (name "MCU_0_MCLR") (class "Default")
      (node (ref "MCU_0") (pin "P$4") (pinfunction "4_P$4") (pintype "bidirectional"))
      (node (ref "R11") (pin "1") (pinfunction "1_1") (pintype "passive"))
      (node (ref "U1") (pin "18") (pinfunction "~_18") (pintype "input"))
    )
    (net (code "48") (name "MCU_0_PGC") (class "Default")
      (node (ref "MCU_0") (pin "P$3") (pinfunction "3_P$3") (pintype "bidirectional"))
      (node (ref "U1") (pin "16") (pinfunction "RB6/CCP6/KBI2/PGC/RP9_16") (pintype "bidirectional"))
    )
    (net (code "49") (name "MCU_0_PGD") (class "Default")
      (node (ref "MCU_0") (pin "P$2") (pinfunction "2_P$2") (pintype "bidirectional"))
      (node (ref "U1") (pin "17") (pinfunction "RB7/CCP7/KBI3/PGD/RP10_17") (pintype "bidirectional"))
    )
    (net (code "50") (name "MCU_0_RAIN_SENSOR") (class "Default")
      (node (ref "R57") (pin "1") (pinfunction "1_1") (pintype "passive"))
      (node (ref "U1") (pin "27") (pinfunction "RE2/AN7/PMCS_27") (pintype "bidirectional"))
    )
    (net (code "51") (name "MCU_0_TEMP_SENSOR_0") (class "Default")
      (node (ref "R69") (pin "1") (pinfunction "1_1") (pintype "passive"))
      (node (ref "TEMP_SENSOR_0") (pin "2") (pinfunction "2_2") (pintype "passive"))
      (node (ref "U1") (pin "10") (pinfunction "RB2/AN8/C2INC/CTED1/PMA3/REFO/RP5_10") (pintype "bidirectional"))
    )
    (net (code "52") (name "MCU_0_TEMP_SENSOR_1") (class "Default")
      (node (ref "R70") (pin "1") (pinfunction "1_1") (pintype "passive"))
      (node (ref "TEMP_SENSOR_1") (pin "2") (pinfunction "2_2") (pintype "passive"))
      (node (ref "U1") (pin "11") (pinfunction "RB3/AN9/C3INA/CTED2/PMA2/RP6_11") (pintype "bidirectional"))
    )
    (net (code "53") (name "MCU_0_TEMP_SENSOR_2") (class "Default")
      (node (ref "R71") (pin "1") (pinfunction "1_1") (pintype "passive"))
      (node (ref "TEMP_SENSOR_2") (pin "2") (pinfunction "2_2") (pintype "passive"))
      (node (ref "U1") (pin "9") (pinfunction "RB1/AN10/C3INC/PMBE/RTCC/RP4_9") (pintype "bidirectional"))
    )
    (net (code "54") (name "MCU_0_TEMP_SENSOR_3") (class "Default")
      (node (ref "R72") (pin "1") (pinfunction "1_1") (pintype "passive"))
      (node (ref "TEMP_SENSOR_3") (pin "2") (pinfunction "2_2") (pintype "passive"))
      (node (ref "U1") (pin "8") (pinfunction "RB0/AN12/C3IND/INT0/RP3_8") (pintype "bidirectional"))
    )
    (net (code "55") (name "MCU_0_TILT_SENSOR") (class "Default")
      (node (ref "C79") (pin "1") (pinfunction "1_1") (pintype "passive"))
      (node (ref "R90") (pin "1") (pinfunction "1_1") (pintype "passive"))
      (node (ref "TILT") (pin "TP") (pinfunction "TP_TP") (pintype "input"))
      (node (ref "TILT_SENSOR") (pin "2") (pinfunction "2_2") (pintype "passive"))
      (node (ref "U1") (pin "36") (pinfunction "RC2/AN11/C2IND/CTPLS/RP13_36") (pintype "bidirectional"))
    )
    (net (code "56") (name "MCU_0_UART_RX") (class "Default")
      (node (ref "MCU0_RX") (pin "TP") (pinfunction "TP_TP") (pintype "input"))
      (node (ref "U1") (pin "1") (pinfunction "RC7/CCP10/PMA4/RX1/DT1/RP18_1") (pintype "bidirectional"))
      (node (ref "U15") (pin "40") (pinfunction "OSCO/CLKO/RPC15/RC15_40") (pintype "bidirectional"))
    )
    (net (code "57") (name "MCU_0_UART_TX") (class "Default")
      (node (ref "MCU0_TX") (pin "TP") (pinfunction "TP_TP") (pintype "input"))
      (node (ref "U1") (pin "44") (pinfunction "RC6/CCP9/PMA5/TX1/CK1/RP17_44") (pintype "bidirectional"))
      (node (ref "U15") (pin "46") (pinfunction "OA5OUT/AN25/CVD25/C5IN4-/RPB7/SCK1/INT0/RB7_46") (pintype "bidirectional"))
    )
    (net (code "58") (name "MCU_1_BLADE_MOTOR_PWM") (class "Default")
      (node (ref "IC1") (pin "18") (pinfunction "TDO/RP9/SDA1/CN21/PMD3/RB9_18") (pintype "passive"))
      (node (ref "R48") (pin "1") (pinfunction "1_1") (pintype "passive"))
      (node (ref "R97") (pin "1") (pinfunction "1_1") (pintype "passive"))
    )
    (net (code "59") (name "MCU_1_MCLR") (class "Default")
      (node (ref "IC1") (pin "1") (pinfunction "*MCLR_1") (pintype "passive"))
      (node (ref "MCU_1") (pin "P$4") (pinfunction "4_P$4") (pintype "bidirectional"))
      (node (ref "R9") (pin "1") (pinfunction "1_1") (pintype "passive"))
    )
    (net (code "60") (name "MCU_1_PGC") (class "Default")
      (node (ref "IC1") (pin "5") (pinfunction "PGC1/EMUC1/AN3/C2IN+/RP1/CN5/RB1_5") (pintype "passive"))
      (node (ref "MCU_1") (pin "P$3") (pinfunction "3_P$3") (pintype "bidirectional"))
    )
    (net (code "61") (name "MCU_1_PGD") (class "Default")
      (node (ref "IC1") (pin "4") (pinfunction "PGD1/EMUD1/AN2/C2IN-/RP0/CN4/RB0_4") (pintype "passive"))
      (node (ref "MCU_1") (pin "P$2") (pinfunction "2_P$2") (pintype "bidirectional"))
    )
    (net (code "62") (name "MCU_1_STEP_DRV_0_DIR") (class "Default")
      (node (ref "IC1") (pin "2") (pinfunction "AN0/VREF+/CN2/RA0_2") (pintype "passive"))
      (node (ref "SD1") (pin "1") (pinfunction "DIR_1") (pintype "bidirectional"))
    )
    (net (code "63") (name "MCU_1_STEP_DRV_0_ENABLE") (class "Default")
      (node (ref "IC1") (pin "6") (pinfunction "AN4/C1IN-/RP2/SDA2/CN6/RB2_6") (pintype "passive"))
      (node (ref "R94") (pin "1") (pinfunction "1_1") (pintype "passive"))
      (node (ref "SD1") (pin "18") (pinfunction "~{ENBL}_18") (pintype "bidirectional"))
    )
    (net (code "64") (name "MCU_1_STEP_DRV_0_MS1") (class "Default")
      (node (ref "IC1") (pin "7") (pinfunction "AN5/C1IN+/RP3/SCL2/CN7/RB3_7") (pintype "passive"))
      (node (ref "SD1") (pin "7") (pinfunction "MS1_7") (pintype "bidirectional"))
    )
    (net (code "65") (name "MCU_1_STEP_DRV_0_MS2") (class "Default")
      (node (ref "IC1") (pin "9") (pinfunction "OSCI/CLKI/CN30/RA2_9") (pintype "passive"))
      (node (ref "SD1") (pin "6") (pinfunction "MS2_6") (pintype "bidirectional"))
    )
    (net (code "66") (name "MCU_1_STEP_DRV_0_STEP") (class "Default")
      (node (ref "IC1") (pin "3") (pinfunction "AN1/VREF-/CN3/RA1_3") (pintype "passive"))
      (node (ref "SD1") (pin "13") (pinfunction "STEP_13") (pintype "bidirectional"))
    )
    (net (code "67") (name "MCU_1_STEP_DRV_1_DIR") (class "Default")
      (node (ref "IC1") (pin "10") (pinfunction "OSCO/CLKO/CN29/PMA0/RA3_10") (pintype "passive"))
      (node (ref "SD2") (pin "1") (pinfunction "DIR_1") (pintype "bidirectional"))
    )
    (net (code "68") (name "MCU_1_STEP_DRV_1_ENABLE") (class "Default")
      (node (ref "IC1") (pin "12") (pinfunction "SOSCO/T1CK/CN0/PMA1/RA4_12") (pintype "passive"))
      (node (ref "R95") (pin "1") (pinfunction "1_1") (pintype "passive"))
      (node (ref "SD2") (pin "18") (pinfunction "~{ENBL}_18") (pintype "bidirectional"))
    )
    (net (code "69") (name "MCU_1_STEP_DRV_1_MS1") (class "Default")
      (node (ref "IC1") (pin "14") (pinfunction "PGD3/EMUD3/RP5/ASDA1/CN27/PMD7/RB5_14") (pintype "passive"))
      (node (ref "SD2") (pin "7") (pinfunction "MS1_7") (pintype "bidirectional"))
    )
    (net (code "70") (name "MCU_1_STEP_DRV_1_MS2") (class "Default")
      (node (ref "IC1") (pin "15") (pinfunction "PGC3/EMUC3/RP6/ASCL1/CN24/PMD6/RB6_15") (pintype "passive"))
      (node (ref "SD2") (pin "6") (pinfunction "MS2_6") (pintype "bidirectional"))
    )
    (net (code "71") (name "MCU_1_STEP_DRV_1_STEP") (class "Default")
      (node (ref "IC1") (pin "11") (pinfunction "SOSCI/RP4/PMBE/CN1/RB4_11") (pintype "passive"))
      (node (ref "SD2") (pin "13") (pinfunction "STEP_13") (pintype "bidirectional"))
    )
    (net (code "72") (name "MCU_1_STEP_DRV_2_DIR") (class "Default")
      (node (ref "IC1") (pin "16") (pinfunction "RP7/INT0/CN23/PMD5/RB7_16") (pintype "passive"))
      (node (ref "SD3") (pin "1") (pinfunction "DIR_1") (pintype "bidirectional"))
    )
    (net (code "73") (name "MCU_1_STEP_DRV_2_ENABLE") (class "Default")
      (node (ref "IC1") (pin "19") (pinfunction "DISVREG_19") (pintype "passive"))
      (node (ref "R96") (pin "1") (pinfunction "1_1") (pintype "passive"))
      (node (ref "SD3") (pin "18") (pinfunction "~{ENBL}_18") (pintype "bidirectional"))
    )
    (net (code "74") (name "MCU_1_STEP_DRV_2_MS1") (class "Default")
      (node (ref "IC1") (pin "21") (pinfunction "PGD2/EMUD2/TDI/RP10/CN16/PMD2/RB10_21") (pintype "passive"))
      (node (ref "SD3") (pin "7") (pinfunction "MS1_7") (pintype "bidirectional"))
    )
    (net (code "75") (name "MCU_1_STEP_DRV_2_MS2") (class "Default")
      (node (ref "IC1") (pin "22") (pinfunction "PGC2/EMUC2/TMS/RP11/CN15/PMD1/RB11_22") (pintype "passive"))
      (node (ref "SD3") (pin "6") (pinfunction "MS2_6") (pintype "bidirectional"))
    )
    (net (code "76") (name "MCU_1_STEP_DRV_2_STEP") (class "Default")
      (node (ref "IC1") (pin "17") (pinfunction "TCK/RP8/SCL1/CN22/PMD4/RB8_17") (pintype "passive"))
      (node (ref "SD3") (pin "13") (pinfunction "STEP_13") (pintype "bidirectional"))
    )
    (net (code "77") (name "MCU_1_UART1_RX") (class "Default")
      (node (ref "IC1") (pin "26") (pinfunction "AN9/RP15/CN11/PMCS1/RB15_26") (pintype "passive"))
      (node (ref "MCU1_RX") (pin "TP") (pinfunction "TP_TP") (pintype "input"))
      (node (ref "MCU_1_UART_RX_SWITCH") (pin "2") (pinfunction "2_2") (pintype "passive"))
    )
    (net (code "78") (name "MCU_1_UART1_TX") (class "Default")
      (node (ref "IC1") (pin "25") (pinfunction "AN10/CVREF/RTCC/RP14/CN12/PMWR/RB14_25") (pintype "passive"))
      (node (ref "MCU1_TX") (pin "TP") (pinfunction "TP_TP") (pintype "input"))
      (node (ref "MCU_1_UART_TX_SWITCH") (pin "2") (pinfunction "2_2") (pintype "passive"))
    )
    (net (code "79") (name "MCU_2_LED0") (class "Default")
      (node (ref "R84") (pin "1") (pinfunction "1_1") (pintype "passive"))
      (node (ref "U15") (pin "51") (pinfunction "TRD0/RPC7/PWM12H/PWM6L/RC7_51") (pintype "bidirectional"))
    )
    (net (code "80") (name "MCU_2_LED1") (class "Default")
      (node (ref "R91") (pin "1") (pinfunction "1_1") (pintype "passive"))
      (node (ref "U15") (pin "52") (pinfunction "TRD1/RPC8/PWM5H/PMWR/RC8_52") (pintype "bidirectional"))
    )
    (net (code "81") (name "MCU_2_LED2") (class "Default")
      (node (ref "R92") (pin "1") (pinfunction "1_1") (pintype "passive"))
      (node (ref "U15") (pin "53") (pinfunction "TRD2/RPD5/PWM12H/PMRD/RD5_53") (pintype "bidirectional"))
    )
    (net (code "82") (name "MCU_2_LED3") (class "Default")
      (node (ref "R93") (pin "1") (pinfunction "1_1") (pintype "passive"))
      (node (ref "U15") (pin "54") (pinfunction "TRD3/RPD6/PWM12L/RD6_54") (pintype "bidirectional"))
    )
    (net (code "83") (name "MCU_2_LIDAR_ENABLE") (class "Default")
      (node (ref "R62") (pin "1") (pinfunction "1_1") (pintype "passive"))
      (node (ref "U15") (pin "42") (pinfunction "RD8_42") (pintype "bidirectional"))
    )
    (net (code "84") (name "MCU_2_MCLR") (class "Default")
      (node (ref "MCU_2") (pin "P$4") (pinfunction "4_P$4") (pintype "bidirectional"))
      (node (ref "R13") (pin "1") (pinfunction "1_1") (pintype "passive"))
      (node (ref "U15") (pin "7") (pinfunction "~{MCLR}_7") (pintype "input"))
    )
    (net (code "85") (name "MCU_2_PGC") (class "Default")
      (node (ref "MCU_2") (pin "P$3") (pinfunction "3_P$3") (pintype "bidirectional"))
      (node (ref "U15") (pin "17") (pinfunction "PGC1/OA1IN+/AN4/C1IN1+/C1IN3-/C2IN3-/RPB2/RB2_17") (pintype "bidirectional"))
    )
    (net (code "86") (name "MCU_2_PGD") (class "Default")
      (node (ref "MCU_2") (pin "P$2") (pinfunction "2_P$2") (pintype "bidirectional"))
      (node (ref "U15") (pin "18") (pinfunction "PGD1/OA1IN-/AN5/CTCMP/C1IN1-/RTCC/RPB3/RB3_18") (pintype "bidirectional"))
    )
    (net (code "87") (name "MCU_2_UART3_RX") (class "Default")
      (node (ref "MCU_1_UART_TX_SWITCH") (pin "1") (pinfunction "1_1") (pintype "passive"))
      (node (ref "U15") (pin "1") (pinfunction "TCK/RPA7/PWM10H/PWM4L/PMD5/RA7_1") (pintype "bidirectional"))
    )
    (net (code "88") (name "MCU_2_UART3_TX") (class "Default")
      (node (ref "MCU_1_UART_RX_SWITCH") (pin "1") (pinfunction "1_1") (pintype "passive"))
      (node (ref "U15") (pin "2") (pinfunction "RPB14/PWM1H/VBUSON1/PMD6/RB14_2") (pintype "bidirectional"))
    )
    (net (code "89") (name "MCU_3_BUTTON_0") (class "Default")
      (node (ref "BUTTONS") (pin "1") (pinfunction "1_1") (pintype "passive"))
      (node (ref "C1") (pin "1") (pinfunction "1_1") (pintype "passive"))
      (node (ref "MCU_3_ESP32") (pin "6") (pinfunction "IO34_6") (pintype "bidirectional"))
      (node (ref "R111") (pin "1") (pinfunction "1_1") (pintype "passive"))
    )
    (net (code "90") (name "MCU_3_BUTTON_1") (class "Default")
      (node (ref "BUTTONS") (pin "2") (pinfunction "2_2") (pintype "passive"))
      (node (ref "C4") (pin "1") (pinfunction "1_1") (pintype "passive"))
      (node (ref "MCU_3_ESP32") (pin "7") (pinfunction "IO35_7") (pintype "bidirectional"))
      (node (ref "R112") (pin "1") (pinfunction "1_1") (pintype "passive"))
    )
    (net (code "91") (name "MCU_3_BUTTON_2") (class "Default")
      (node (ref "BUTTONS") (pin "3") (pinfunction "3_3") (pintype "passive"))
      (node (ref "C73") (pin "1") (pinfunction "1_1") (pintype "passive"))
      (node (ref "MCU_3_ESP32") (pin "8") (pinfunction "IO32_8") (pintype "bidirectional"))
      (node (ref "R113") (pin "1") (pinfunction "1_1") (pintype "passive"))
    )
    (net (code "92") (name "MCU_3_BUTTON_3") (class "Default")
      (node (ref "BUTTONS") (pin "4") (pinfunction "4_4") (pintype "passive"))
      (node (ref "C74") (pin "1") (pinfunction "1_1") (pintype "passive"))
      (node (ref "MCU_3_ESP32") (pin "9") (pinfunction "IO33_9") (pintype "bidirectional"))
      (node (ref "R114") (pin "1") (pinfunction "1_1") (pintype "passive"))
    )
    (net (code "93") (name "MCU_3_BUTTON_4") (class "Default")
      (node (ref "BUTTONS") (pin "5") (pinfunction "5_5") (pintype "passive"))
      (node (ref "C75") (pin "1") (pinfunction "1_1") (pintype "passive"))
      (node (ref "MCU_3_ESP32") (pin "10") (pinfunction "IO25_10") (pintype "bidirectional"))
      (node (ref "R115") (pin "1") (pinfunction "1_1") (pintype "passive"))
    )
    (net (code "94") (name "MCU_3_BUTTON_5") (class "Default")
      (node (ref "BUTTONS") (pin "6") (pinfunction "6_6") (pintype "passive"))
      (node (ref "C76") (pin "1") (pinfunction "1_1") (pintype "passive"))
      (node (ref "MCU_3_ESP32") (pin "11") (pinfunction "IO26_11") (pintype "bidirectional"))
      (node (ref "R116") (pin "1") (pinfunction "1_1") (pintype "passive"))
    )
    (net (code "95") (name "MCU_3_BUTTON_6") (class "Default")
      (node (ref "BUTTONS") (pin "7") (pinfunction "7_7") (pintype "passive"))
      (node (ref "C77") (pin "1") (pinfunction "1_1") (pintype "passive"))
      (node (ref "MCU_3_ESP32") (pin "12") (pinfunction "IO27_12") (pintype "bidirectional"))
      (node (ref "R117") (pin "1") (pinfunction "1_1") (pintype "passive"))
    )
    (net (code "96") (name "MCU_3_BUTTON_7") (class "Default")
      (node (ref "BUTTONS") (pin "8") (pinfunction "8_8") (pintype "passive"))
      (node (ref "C78") (pin "1") (pinfunction "1_1") (pintype "passive"))
      (node (ref "MCU_3_ESP32") (pin "13") (pinfunction "IO14_13") (pintype "bidirectional"))
      (node (ref "R118") (pin "1") (pinfunction "1_1") (pintype "passive"))
    )
    (net (code "97") (name "MCU_3_I2C_SCL") (class "Default")
      (node (ref "DISPLAY") (pin "1") (pinfunction "1_1") (pintype "passive"))
      (node (ref "MCU3_SCL") (pin "TP") (pinfunction "TP_TP") (pintype "input"))
      (node (ref "MCU_3_ESP32") (pin "36") (pinfunction "IO22_36") (pintype "bidirectional"))
      (node (ref "R105") (pin "1") (pinfunction "1_1") (pintype "passive"))
      (node (ref "R5") (pin "2") (pinfunction "2_2") (pintype "passive"))
      (node (ref "RTCC") (pin "3") (pinfunction "SCL_3") (pintype "bidirectional"))
    )
    (net (code "98") (name "MCU_3_I2C_SDA") (class "Default")
      (node (ref "DISPLAY") (pin "2") (pinfunction "2_2") (pintype "passive"))
      (node (ref "MCU3_SDA") (pin "TP") (pinfunction "TP_TP") (pintype "input"))
      (node (ref "MCU_3_ESP32") (pin "33") (pinfunction "IO21_33") (pintype "bidirectional"))
      (node (ref "R106") (pin "1") (pinfunction "1_1") (pintype "passive"))
      (node (ref "R26") (pin "2") (pinfunction "2_2") (pintype "passive"))
      (node (ref "RTCC") (pin "4") (pinfunction "SDA_4") (pintype "bidirectional"))
    )
    (net (code "99") (name "MCU_3_LED_B") (class "Default")
      (node (ref "MCU_3_ESP32") (pin "23") (pinfunction "IO15_23") (pintype "bidirectional"))
      (node (ref "RGB_LED") (pin "3") (pinfunction "3_3") (pintype "passive"))
    )
    (net (code "100") (name "MCU_3_LED_G") (class "Default")
      (node (ref "MCU_3_ESP32") (pin "24") (pinfunction "IO2_24") (pintype "bidirectional"))
      (node (ref "RGB_LED") (pin "2") (pinfunction "2_2") (pintype "passive"))
    )
    (net (code "101") (name "MCU_3_LED_R") (class "Default")
      (node (ref "MCU_3_ESP32") (pin "26") (pinfunction "IO4_26") (pintype "bidirectional"))
      (node (ref "RGB_LED") (pin "1") (pinfunction "1_1") (pintype "passive"))
    )
    (net (code "102") (name "MCU_3_SD_DET") (class "Default")
      (node (ref "MCU_3_ESP32") (pin "22") (pinfunction "SD1_22") (pintype "bidirectional"))
      (node (ref "R103") (pin "1") (pinfunction "1_1") (pintype "passive"))
      (node (ref "X5") (pin "DETECT") (pinfunction "DETECT_DETECT") (pintype "input"))
    )
    (net (code "103") (name "MCU_3_SD_WRTPT") (class "Default")
      (node (ref "MCU_3_ESP32") (pin "21") (pinfunction "SD0_21") (pintype "bidirectional"))
      (node (ref "R104") (pin "1") (pinfunction "1_1") (pintype "passive"))
      (node (ref "X5") (pin "WRITE_PROT") (pinfunction "WRITE_PROT_WRITE_PROT") (pintype "input"))
    )
    (net (code "104") (name "MCU_3_SPI_MISO") (class "Default")
      (node (ref "MCU_3_ESP32") (pin "31") (pinfunction "IO19_31") (pintype "bidirectional"))
      (node (ref "R99") (pin "1") (pinfunction "1_1") (pintype "passive"))
      (node (ref "X5") (pin "7") (pinfunction "7_7") (pintype "input"))
    )
    (net (code "105") (name "MCU_3_SPI_MOSI") (class "Default")
      (node (ref "MCU_3_ESP32") (pin "37") (pinfunction "IO23_37") (pintype "bidirectional"))
      (node (ref "R98") (pin "1") (pinfunction "1_1") (pintype "passive"))
      (node (ref "X5") (pin "2") (pinfunction "2_2") (pintype "input"))
    )
    (net (code "106") (name "MCU_3_SPI_SCK") (class "Default")
      (node (ref "MCU_3_ESP32") (pin "30") (pinfunction "IO18_30") (pintype "bidirectional"))
      (node (ref "X5") (pin "5") (pinfunction "5_5") (pintype "input"))
    )
    (net (code "107") (name "MCU_3_SPI_SS") (class "Default")
      (node (ref "MCU_3_ESP32") (pin "29") (pinfunction "IO5_29") (pintype "bidirectional"))
      (node (ref "R100") (pin "1") (pinfunction "1_1") (pintype "passive"))
      (node (ref "X5") (pin "1") (pinfunction "1_1") (pintype "input"))
    )
    (net (code "108") (name "MCU_3_TRIGGER_CAMERA") (class "Default")
      (node (ref "CAMERA") (pin "1") (pinfunction "1_1") (pintype "passive"))
      (node (ref "MCU_3_ESP32") (pin "14") (pinfunction "IO12_14") (pintype "bidirectional"))
    )
    (net (code "109") (name "MCU_3_UART1_RX") (class "Default")
      (node (ref "MCU3_RX") (pin "TP") (pinfunction "TP_TP") (pintype "input"))
      (node (ref "MCU_1_UART_TX_SWITCH") (pin "3") (pinfunction "3_3") (pintype "passive"))
      (node (ref "MCU_3_ESP32") (pin "17") (pinfunction "SD2_17") (pintype "bidirectional"))
    )
    (net (code "110") (name "MCU_3_UART1_TX") (class "Default")
      (node (ref "MCU3_TX") (pin "TP") (pinfunction "TP_TP") (pintype "input"))
      (node (ref "MCU_1_UART_RX_SWITCH") (pin "3") (pinfunction "3_3") (pintype "passive"))
      (node (ref "MCU_3_ESP32") (pin "18") (pinfunction "SD3_18") (pintype "bidirectional"))
    )
    (net (code "111") (name "MCU_3_UART2_RX") (class "Default")
      (node (ref "MCU_3_ESP32") (pin "27") (pinfunction "IO16_27") (pintype "bidirectional"))
      (node (ref "NAVIGATION_UART") (pin "1") (pinfunction "1_1") (pintype "passive"))
      (node (ref "U15") (pin "12") (pinfunction "AN9/CVD9/RPA11/RA11_12") (pintype "bidirectional"))
    )
    (net (code "112") (name "MCU_3_UART2_TX") (class "Default")
      (node (ref "MCU_3_ESP32") (pin "28") (pinfunction "IO17_28") (pintype "bidirectional"))
      (node (ref "NAVIGATION_UART") (pin "2") (pinfunction "2_2") (pintype "passive"))
      (node (ref "U15") (pin "33") (pinfunction "OA5IN+/DAC1/AN24/CVD24/C5IN1+/C5IN3-/RPA4/RA4_33") (pintype "bidirectional"))
    )
    (net (code "113") (name "MPU6050_INT") (class "Default")
      (node (ref "U5") (pin "12") (pinfunction "INT_12") (pintype "output"))
    )
    (net (code "114") (name "MPU6050_SCL") (class "Default")
      (node (ref "MPU6050_SCL") (pin "TP") (pinfunction "TP_TP") (pintype "input"))
      (node (ref "R37") (pin "2") (pinfunction "2_2") (pintype "passive"))
      (node (ref "U15") (pin "28") (pinfunction "AN13/CVD13/C3IN2-/FLT6/SCL4/PMA10/RE13_28") (pintype "bidirectional"))
      (node (ref "U5") (pin "23") (pinfunction "SCL_23") (pintype "bidirectional"))
    )
    (net (code "115") (name "MPU6050_SDA") (class "Default")
      (node (ref "MPU6050_SDA") (pin "TP") (pinfunction "TP_TP") (pintype "input"))
      (node (ref "R36") (pin "2") (pinfunction "2_2") (pintype "passive"))
      (node (ref "U15") (pin "27") (pinfunction "AN12/CVD12/C2IN2-/C5IN2-/SDA4/FLT5/PMA11/RE12_27") (pintype "bidirectional"))
      (node (ref "U5") (pin "24") (pinfunction "SDA_24") (pintype "bidirectional"))
    )
    (net (code "116") (name "Net-(BUTTONS-Pad9)") (class "Default")
      (node (ref "BUTTONS") (pin "9") (pinfunction "9_9") (pintype "passive"))
      (node (ref "R27") (pin "2") (pinfunction "2_2") (pintype "passive"))
    )
    (net (code "117") (name "Net-(BUZZER-2)") (class "Default")
      (node (ref "BUZZER") (pin "-") (pinfunction "2_-") (pintype "passive"))
      (node (ref "R25") (pin "2") (pinfunction "2_2") (pintype "passive"))
    )
    (net (code "118") (name "Net-(C6-Pad1)") (class "Default")
      (node (ref "C6") (pin "1") (pinfunction "1_1") (pintype "passive"))
      (node (ref "R8") (pin "1") (pinfunction "1_1") (pintype "passive"))
      (node (ref "R9") (pin "2") (pinfunction "2_2") (pintype "passive"))
    )
    (net (code "119") (name "Net-(C11-Pad1)") (class "Default")
      (node (ref "C11") (pin "1") (pinfunction "1_1") (pintype "passive"))
      (node (ref "R10") (pin "1") (pinfunction "1_1") (pintype "passive"))
      (node (ref "R11") (pin "2") (pinfunction "2_2") (pintype "passive"))
    )
    (net (code "120") (name "Net-(C15-Pad1)") (class "Default")
      (node (ref "C15") (pin "1") (pinfunction "1_1") (pintype "passive"))
      (node (ref "R12") (pin "1") (pinfunction "1_1") (pintype "passive"))
      (node (ref "R13") (pin "2") (pinfunction "2_2") (pintype "passive"))
    )
    (net (code "121") (name "Net-(C81-Pad1)") (class "Default")
      (node (ref "C81") (pin "1") (pinfunction "1_1") (pintype "passive"))
      (node (ref "L3") (pin "1") (pinfunction "1_1") (pintype "passive"))
      (node (ref "X5") (pin "4") (pinfunction "4_4") (pintype "input"))
    )
    (net (code "122") (name "Net-(CP2102-REGIN)") (class "Default")
      (node (ref "C37") (pin "2") (pinfunction "2_2") (pintype "passive"))
      (node (ref "C38") (pin "2") (pinfunction "2_2") (pintype "passive"))
      (node (ref "CP2102") (pin "7") (pinfunction "REGIN_7") (pintype "passive"))
      (node (ref "CP2102") (pin "8") (pinfunction "VBUS_8") (pintype "input"))
      (node (ref "D3") (pin "C") (pinfunction "C_C") (pintype "passive"))
      (node (ref "MICROUSB") (pin "1") (pinfunction "VBUS_1") (pintype "power_in"))
    )
    (net (code "123") (name "Net-(CURRENT_SENSOR_BATT-AOUT)") (class "Default")
      (node (ref "C31") (pin "1") (pinfunction "1_1") (pintype "passive"))
      (node (ref "CURRENT_SENSOR_BATT") (pin "4") (pinfunction "AOUT_4") (pintype "output"))
      (node (ref "R21") (pin "1") (pinfunction "1_1") (pintype "passive"))
    )
    (net (code "124") (name "Net-(CURRENT_SENSOR_BATT-VREF)") (class "Default")
      (node (ref "C33") (pin "1") (pinfunction "1_1") (pintype "passive"))
      (node (ref "CURRENT_SENSOR_BATT") (pin "3") (pinfunction "VREF_3") (pintype "bidirectional"))
      (node (ref "R20") (pin "2") (pinfunction "2_2") (pintype "passive"))
    )
    (net (code "125") (name "Net-(EM_LIGHT-Pad2)") (class "Default")
      (node (ref "EM_LIGHT") (pin "2") (pinfunction "2_2") (pintype "passive"))
      (node (ref "NMOS6") (pin "5") (pinfunction "D_5") (pintype "passive"))
      (node (ref "NMOS6") (pin "6") (pinfunction "D_6") (pintype "passive"))
      (node (ref "NMOS6") (pin "7") (pinfunction "D_7") (pintype "passive"))
      (node (ref "NMOS6") (pin "8") (pinfunction "D_8") (pintype "passive"))
      (node (ref "NMOS6") (pin "TH") (pinfunction "TH_TH") (pintype "passive"))
    )
    (net (code "126") (name "Net-(FAN_0-Pad2)") (class "Default")
      (node (ref "FAN_0") (pin "2") (pinfunction "2_2") (pintype "passive"))
      (node (ref "NMOS2") (pin "5") (pinfunction "D_5") (pintype "passive"))
      (node (ref "NMOS2") (pin "6") (pinfunction "D_6") (pintype "passive"))
      (node (ref "NMOS2") (pin "7") (pinfunction "D_7") (pintype "passive"))
      (node (ref "NMOS2") (pin "8") (pinfunction "D_8") (pintype "passive"))
      (node (ref "NMOS2") (pin "TH") (pinfunction "TH_TH") (pintype "passive"))
    )
    (net (code "127") (name "Net-(FAN_1-Pad2)") (class "Default")
      (node (ref "FAN_1") (pin "2") (pinfunction "2_2") (pintype "passive"))
      (node (ref "NMOS3") (pin "5") (pinfunction "D_5") (pintype "passive"))
      (node (ref "NMOS3") (pin "6") (pinfunction "D_6") (pintype "passive"))
      (node (ref "NMOS3") (pin "7") (pinfunction "D_7") (pintype "passive"))
      (node (ref "NMOS3") (pin "8") (pinfunction "D_8") (pintype "passive"))
      (node (ref "NMOS3") (pin "TH") (pinfunction "TH_TH") (pintype "passive"))
    )
    (net (code "128") (name "Net-(FAN_2-Pad2)") (class "Default")
      (node (ref "FAN_2") (pin "2") (pinfunction "2_2") (pintype "passive"))
      (node (ref "NMOS4") (pin "5") (pinfunction "D_5") (pintype "passive"))
      (node (ref "NMOS4") (pin "6") (pinfunction "D_6") (pintype "passive"))
      (node (ref "NMOS4") (pin "7") (pinfunction "D_7") (pintype "passive"))
      (node (ref "NMOS4") (pin "8") (pinfunction "D_8") (pintype "passive"))
      (node (ref "NMOS4") (pin "TH") (pinfunction "TH_TH") (pintype "passive"))
    )
    (net (code "129") (name "Net-(FAN_3-Pad2)") (class "Default")
      (node (ref "FAN_3") (pin "2") (pinfunction "2_2") (pintype "passive"))
      (node (ref "NMOS5") (pin "5") (pinfunction "D_5") (pintype "passive"))
      (node (ref "NMOS5") (pin "6") (pinfunction "D_6") (pintype "passive"))
      (node (ref "NMOS5") (pin "7") (pinfunction "D_7") (pintype "passive"))
      (node (ref "NMOS5") (pin "8") (pinfunction "D_8") (pintype "passive"))
      (node (ref "NMOS5") (pin "TH") (pinfunction "TH_TH") (pintype "passive"))
    )
    (net (code "130") (name "Net-(IC1-VCAP{slash}VDDCORE)") (class "Default")
      (node (ref "C13") (pin "1") (pinfunction "1_1") (pintype "passive"))
      (node (ref "IC1") (pin "20") (pinfunction "VCAP/VDDCORE_20") (pintype "passive"))
    )
    (net (code "131") (name "Net-(LED1-PadA)") (class "Default")
      (node (ref "LED1") (pin "A") (pinfunction "A_A") (pintype "passive"))
      (node (ref "R75") (pin "1") (pinfunction "1_1") (pintype "passive"))
    )
    (net (code "132") (name "Net-(LED2-PadA)") (class "Default")
      (node (ref "LED2") (pin "A") (pinfunction "A_A") (pintype "passive"))
      (node (ref "R28") (pin "2") (pinfunction "2_2") (pintype "passive"))
    )
    (net (code "133") (name "Net-(LED3-PadA)") (class "Default")
      (node (ref "LED3") (pin "A") (pinfunction "A_A") (pintype "passive"))
      (node (ref "R29") (pin "2") (pinfunction "2_2") (pintype "passive"))
    )
    (net (code "134") (name "Net-(LED4-PadA)") (class "Default")
      (node (ref "LED4") (pin "A") (pinfunction "A_A") (pintype "passive"))
      (node (ref "R30") (pin "2") (pinfunction "2_2") (pintype "passive"))
    )
    (net (code "135") (name "Net-(LED5-PadA)") (class "Default")
      (node (ref "LED5") (pin "A") (pinfunction "A_A") (pintype "passive"))
      (node (ref "R31") (pin "2") (pinfunction "2_2") (pintype "passive"))
    )
    (net (code "136") (name "Net-(LED7-PadA)") (class "Default")
      (node (ref "LED7") (pin "A") (pinfunction "A_A") (pintype "passive"))
      (node (ref "R61") (pin "2") (pinfunction "2_2") (pintype "passive"))
    )
    (net (code "137") (name "Net-(LED8-PadA)") (class "Default")
      (node (ref "LED8") (pin "A") (pinfunction "A_A") (pintype "passive"))
      (node (ref "R121") (pin "2") (pinfunction "2_2") (pintype "passive"))
    )
    (net (code "138") (name "Net-(LED12-PadA)") (class "Default")
      (node (ref "LED12") (pin "A") (pinfunction "A_A") (pintype "passive"))
      (node (ref "R80") (pin "2") (pinfunction "2_2") (pintype "passive"))
    )
    (net (code "139") (name "Net-(LED13-PadA)") (class "Default")
      (node (ref "LED13") (pin "A") (pinfunction "A_A") (pintype "passive"))
      (node (ref "R82") (pin "2") (pinfunction "2_2") (pintype "passive"))
    )
    (net (code "140") (name "Net-(LED14-PadA)") (class "Default")
      (node (ref "LED14") (pin "A") (pinfunction "A_A") (pintype "passive"))
      (node (ref "R83") (pin "2") (pinfunction "2_2") (pintype "passive"))
    )
    (net (code "141") (name "Net-(LED15-PadA)") (class "Default")
      (node (ref "LED15") (pin "A") (pinfunction "A_A") (pintype "passive"))
      (node (ref "R84") (pin "2") (pinfunction "2_2") (pintype "passive"))
    )
    (net (code "142") (name "Net-(LED16-PadA)") (class "Default")
      (node (ref "LED16") (pin "A") (pinfunction "A_A") (pintype "passive"))
      (node (ref "R85") (pin "2") (pinfunction "2_2") (pintype "passive"))
    )
    (net (code "143") (name "Net-(LED17-PadA)") (class "Default")
      (node (ref "LED17") (pin "A") (pinfunction "A_A") (pintype "passive"))
      (node (ref "R86") (pin "2") (pinfunction "2_2") (pintype "passive"))
    )
    (net (code "144") (name "Net-(LED18-PadA)") (class "Default")
      (node (ref "LED18") (pin "A") (pinfunction "A_A") (pintype "passive"))
      (node (ref "R87") (pin "2") (pinfunction "2_2") (pintype "passive"))
    )
    (net (code "145") (name "Net-(LED19-PadA)") (class "Default")
      (node (ref "LED19") (pin "A") (pinfunction "A_A") (pintype "passive"))
      (node (ref "R88") (pin "2") (pinfunction "2_2") (pintype "passive"))
    )
    (net (code "146") (name "Net-(LED20-PadA)") (class "Default")
      (node (ref "LED20") (pin "A") (pinfunction "A_A") (pintype "passive"))
      (node (ref "R89") (pin "2") (pinfunction "2_2") (pintype "passive"))
    )
    (net (code "147") (name "Net-(LED21-PadA)") (class "Default")
      (node (ref "LED21") (pin "A") (pinfunction "A_A") (pintype "passive"))
      (node (ref "R91") (pin "2") (pinfunction "2_2") (pintype "passive"))
    )
    (net (code "148") (name "Net-(LED22-PadA)") (class "Default")
      (node (ref "LED22") (pin "A") (pinfunction "A_A") (pintype "passive"))
      (node (ref "R92") (pin "2") (pinfunction "2_2") (pintype "passive"))
    )
    (net (code "149") (name "Net-(LED23-PadA)") (class "Default")
      (node (ref "LED23") (pin "A") (pinfunction "A_A") (pintype "passive"))
      (node (ref "R93") (pin "2") (pinfunction "2_2") (pintype "passive"))
    )
    (net (code "150") (name "Net-(LED24-PadA)") (class "Default")
      (node (ref "LED24") (pin "A") (pinfunction "A_A") (pintype "passive"))
      (node (ref "R94") (pin "2") (pinfunction "2_2") (pintype "passive"))
    )
    (net (code "151") (name "Net-(LED25-PadA)") (class "Default")
      (node (ref "LED25") (pin "A") (pinfunction "A_A") (pintype "passive"))
      (node (ref "R95") (pin "2") (pinfunction "2_2") (pintype "passive"))
    )
    (net (code "152") (name "Net-(LED26-PadA)") (class "Default")
      (node (ref "LED26") (pin "A") (pinfunction "A_A") (pintype "passive"))
      (node (ref "R96") (pin "2") (pinfunction "2_2") (pintype "passive"))
    )
    (net (code "153") (name "Net-(LED27-PadA)") (class "Default")
      (node (ref "LED27") (pin "A") (pinfunction "A_A") (pintype "passive"))
      (node (ref "R97") (pin "2") (pinfunction "2_2") (pintype "passive"))
    )
    (net (code "154") (name "Net-(LIDAR-Pad5)") (class "Default")
      (node (ref "LIDAR") (pin "5") (pinfunction "5_5") (pintype "passive"))
      (node (ref "NMOS1") (pin "5") (pinfunction "D_5") (pintype "passive"))
      (node (ref "NMOS1") (pin "6") (pinfunction "D_6") (pintype "passive"))
      (node (ref "NMOS1") (pin "7") (pinfunction "D_7") (pintype "passive"))
      (node (ref "NMOS1") (pin "8") (pinfunction "D_8") (pintype "passive"))
      (node (ref "NMOS1") (pin "TH") (pinfunction "TH_TH") (pintype "passive"))
    )
    (net (code "155") (name "Net-(LIGHT_SENSOR-Pad1)") (class "Default")
      (node (ref "LIGHT_SENSOR") (pin "1") (pinfunction "1_1") (pintype "passive"))
      (node (ref "R64") (pin "2") (pinfunction "2_2") (pintype "passive"))
      (node (ref "R66") (pin "2") (pinfunction "2_2") (pintype "passive"))
    )
    (net (code "156") (name "Net-(LIMIT_SWITCH_DOWN-Pad2)") (class "Default")
      (node (ref "LIMIT_SWITCH_DOWN") (pin "2") (pinfunction "2_2") (pintype "passive"))
      (node (ref "R108") (pin "2") (pinfunction "2_2") (pintype "passive"))
      (node (ref "R109") (pin "2") (pinfunction "2_2") (pintype "passive"))
    )
    (net (code "157") (name "Net-(LIMIT_SWITCH_UP-Pad2)") (class "Default")
      (node (ref "LIMIT_SWITCH_UP") (pin "2") (pinfunction "2_2") (pintype "passive"))
      (node (ref "R107") (pin "2") (pinfunction "2_2") (pintype "passive"))
      (node (ref "R110") (pin "2") (pinfunction "2_2") (pintype "passive"))
    )
    (net (code "158") (name "Net-(MAIN_MOTOR_CS-AOUT)") (class "Default")
      (node (ref "C28") (pin "1") (pinfunction "1_1") (pintype "passive"))
      (node (ref "MAIN_MOTOR_CS") (pin "4") (pinfunction "AOUT_4") (pintype "output"))
      (node (ref "R19") (pin "1") (pinfunction "1_1") (pintype "passive"))
    )
    (net (code "159") (name "Net-(MAIN_MOTOR_CS-VREF)") (class "Default")
      (node (ref "C30") (pin "1") (pinfunction "1_1") (pintype "passive"))
      (node (ref "MAIN_MOTOR_CS") (pin "3") (pinfunction "VREF_3") (pintype "bidirectional"))
      (node (ref "R18") (pin "2") (pinfunction "2_2") (pintype "passive"))
    )
    (net (code "160") (name "Net-(MCU_3_ESP32-EN)") (class "Default")
      (node (ref "EN") (pin "1") (pinfunction "1_1") (pintype "passive"))
      (node (ref "MCU_3_ESP32") (pin "3") (pinfunction "EN_3") (pintype "input"))
      (node (ref "R73") (pin "2") (pinfunction "2_2") (pintype "passive"))
    )
    (net (code "161") (name "Net-(MCU_3_ESP32-IO0)") (class "Default")
      (node (ref "BOOT") (pin "1") (pinfunction "1_1") (pintype "passive"))
      (node (ref "MCU_3_ESP32") (pin "25") (pinfunction "IO0_25") (pintype "bidirectional"))
      (node (ref "R74") (pin "1") (pinfunction "1_1") (pintype "passive"))
    )
    (net (code "162") (name "Net-(MCU_3_ESP32-IO13)") (class "Default")
      (node (ref "MCU_3_ESP32") (pin "16") (pinfunction "IO13_16") (pintype "bidirectional"))
      (node (ref "R75") (pin "2") (pinfunction "2_2") (pintype "passive"))
    )
    (net (code "163") (name "Net-(NMOS1A-G)") (class "Default")
      (node (ref "NMOS1") (pin "4") (pinfunction "G_4") (pintype "passive"))
      (node (ref "R54") (pin "1") (pinfunction "1_1") (pintype "passive"))
      (node (ref "U10") (pin "3") (pinfunction "3_3") (pintype "passive"))
    )
    (net (code "164") (name "Net-(NMOS2A-G)") (class "Default")
      (node (ref "NMOS2") (pin "4") (pinfunction "G_4") (pintype "passive"))
      (node (ref "R76") (pin "1") (pinfunction "1_1") (pintype "passive"))
      (node (ref "U4") (pin "3") (pinfunction "3_3") (pintype "passive"))
    )
    (net (code "165") (name "Net-(NMOS3A-G)") (class "Default")
      (node (ref "NMOS3") (pin "4") (pinfunction "G_4") (pintype "passive"))
      (node (ref "R63") (pin "1") (pinfunction "1_1") (pintype "passive"))
      (node (ref "U6") (pin "3") (pinfunction "3_3") (pintype "passive"))
    )
    (net (code "166") (name "Net-(NMOS4A-G)") (class "Default")
      (node (ref "NMOS4") (pin "4") (pinfunction "G_4") (pintype "passive"))
      (node (ref "R65") (pin "1") (pinfunction "1_1") (pintype "passive"))
      (node (ref "U7") (pin "3") (pinfunction "3_3") (pintype "passive"))
    )
    (net (code "167") (name "Net-(NMOS5A-G)") (class "Default")
      (node (ref "NMOS5") (pin "4") (pinfunction "G_4") (pintype "passive"))
      (node (ref "R67") (pin "1") (pinfunction "1_1") (pintype "passive"))
      (node (ref "U8") (pin "3") (pinfunction "3_3") (pintype "passive"))
    )
    (net (code "168") (name "Net-(NMOS6A-G)") (class "Default")
      (node (ref "NMOS6") (pin "4") (pinfunction "G_4") (pintype "passive"))
      (node (ref "R68") (pin "1") (pinfunction "1_1") (pintype "passive"))
      (node (ref "U12") (pin "3") (pinfunction "3_3") (pintype "passive"))
    )
    (net (code "169") (name "Net-(NMOS7A-G)") (class "Default")
      (node (ref "NMOS7") (pin "4") (pinfunction "G_4") (pintype "passive"))
      (node (ref "R23") (pin "1") (pinfunction "1_1") (pintype "passive"))
      (node (ref "U11") (pin "3") (pinfunction "3_3") (pintype "passive"))
    )
    (net (code "170") (name "Net-(PERIMETER_WIRE-Pad2)") (class "Default")
      (node (ref "PERIMETER_WIRE") (pin "2") (pinfunction "2_2") (pintype "passive"))
      (node (ref "R4") (pin "2") (pinfunction "2_2") (pintype "passive"))
    )
    (net (code "171") (name "Net-(Q1-D)") (class "Default")
      (node (ref "C80") (pin "+") (pinfunction "+_+") (pintype "passive"))
      (node (ref "D6") (pin "C") (pinfunction "C_C") (pintype "passive"))
      (node (ref "L1") (pin "2") (pinfunction "2_2") (pintype "bidirectional"))
      (node (ref "Q1") (pin "3") (pinfunction "D_3") (pintype "passive"))
    )
    (net (code "172") (name "Net-(Q1-G)") (class "Default")
      (node (ref "D6") (pin "A") (pinfunction "A_A") (pintype "passive"))
      (node (ref "Q1") (pin "1") (pinfunction "G_1") (pintype "passive"))
      (node (ref "R1") (pin "2") (pinfunction "2_2") (pintype "passive"))
    )
    (net (code "173") (name "Net-(Q1-S)") (class "Default")
      (node (ref "PPTC") (pin "1") (pinfunction "1_1") (pintype "passive"))
      (node (ref "Q1") (pin "2") (pinfunction "S_2") (pintype "passive"))
      (node (ref "TVS25V") (pin "C") (pinfunction "C_C") (pintype "passive"))
    )
    (net (code "174") (name "Net-(Q8-G)") (class "Default")
      (node (ref "Q8") (pin "1") (pinfunction "G_1") (pintype "passive"))
      (node (ref "R77") (pin "2") (pinfunction "2_2") (pintype "passive"))
      (node (ref "R81") (pin "1") (pinfunction "1_1") (pintype "passive"))
    )
    (net (code "175") (name "Net-(R22-Pad2)") (class "Default")
      (node (ref "R22") (pin "2") (pinfunction "2_2") (pintype "passive"))
      (node (ref "U4") (pin "1") (pinfunction "1_1") (pintype "passive"))
    )
    (net (code "176") (name "Net-(R24-Pad2)") (class "Default")
      (node (ref "R24") (pin "2") (pinfunction "2_2") (pintype "passive"))
      (node (ref "T2") (pin "B") (pinfunction "B_B") (pintype "passive"))
    )
    (net (code "177") (name "Net-(R25-Pad1)") (class "Default")
      (node (ref "R25") (pin "1") (pinfunction "1_1") (pintype "passive"))
      (node (ref "T2") (pin "C") (pinfunction "C_C") (pintype "passive"))
    )
    (net (code "178") (name "Net-(R47-Pad2)") (class "Default")
      (node (ref "R47") (pin "2") (pinfunction "2_2") (pintype "passive"))
      (node (ref "U13") (pin "4") (pinfunction "4_4") (pintype "passive"))
    )
    (net (code "179") (name "Net-(R48-Pad2)") (class "Default")
      (node (ref "R48") (pin "2") (pinfunction "2_2") (pintype "passive"))
      (node (ref "U11") (pin "1") (pinfunction "1_1") (pintype "passive"))
    )
    (net (code "180") (name "Net-(R51-Pad2)") (class "Default")
      (node (ref "R51") (pin "2") (pinfunction "2_2") (pintype "passive"))
      (node (ref "U6") (pin "1") (pinfunction "1_1") (pintype "passive"))
    )
    (net (code "181") (name "Net-(R52-Pad2)") (class "Default")
      (node (ref "R52") (pin "2") (pinfunction "2_2") (pintype "passive"))
      (node (ref "U8") (pin "1") (pinfunction "1_1") (pintype "passive"))
    )
    (net (code "182") (name "Net-(R53-Pad2)") (class "Default")
      (node (ref "R53") (pin "2") (pinfunction "2_2") (pintype "passive"))
      (node (ref "U7") (pin "1") (pinfunction "1_1") (pintype "passive"))
    )
    (net (code "183") (name "Net-(R55-Pad2)") (class "Default")
      (node (ref "R55") (pin "2") (pinfunction "2_2") (pintype "passive"))
      (node (ref "R57") (pin "2") (pinfunction "2_2") (pintype "passive"))
      (node (ref "RAIN_SENSOR") (pin "1") (pinfunction "1_1") (pintype "passive"))
    )
    (net (code "184") (name "Net-(R62-Pad2)") (class "Default")
      (node (ref "R62") (pin "2") (pinfunction "2_2") (pintype "passive"))
      (node (ref "U10") (pin "1") (pinfunction "1_1") (pintype "passive"))
    )
    (net (code "185") (name "Net-(R78-Pad1)") (class "Default")
      (node (ref "R78") (pin "1") (pinfunction "1_1") (pintype "passive"))
      (node (ref "U13") (pin "1") (pinfunction "1_1") (pintype "passive"))
    )
    (net (code "186") (name "Net-(R81-Pad2)") (class "Default")
      (node (ref "R81") (pin "2") (pinfunction "2_2") (pintype "passive"))
      (node (ref "U9") (pin "4") (pinfunction "4_4") (pintype "passive"))
    )
    (net (code "187") (name "Net-(R101-Pad2)") (class "Default")
      (node (ref "R101") (pin "2") (pinfunction "2_2") (pintype "passive"))
      (node (ref "X5") (pin "8") (pinfunction "8_8") (pintype "input"))
    )
    (net (code "188") (name "Net-(R102-Pad2)") (class "Default")
      (node (ref "R102") (pin "2") (pinfunction "2_2") (pintype "passive"))
      (node (ref "X5") (pin "9") (pinfunction "9_9") (pintype "input"))
    )
    (net (code "189") (name "Net-(R119-Pad2)") (class "Default")
      (node (ref "R119") (pin "2") (pinfunction "2_2") (pintype "passive"))
      (node (ref "U12") (pin "1") (pinfunction "1_1") (pintype "passive"))
    )
    (net (code "190") (name "Net-(R120-Pad2)") (class "Default")
      (node (ref "R120") (pin "2") (pinfunction "2_2") (pintype "passive"))
      (node (ref "U9") (pin "1") (pinfunction "1_1") (pintype "passive"))
    )
    (net (code "191") (name "Net-(RTCC-VBAT)") (class "Default")
      (node (ref "BATT1") (pin "PLUS") (pinfunction "PLUS_PLUS") (pintype "bidirectional"))
      (node (ref "RTCC") (pin "8") (pinfunction "VBAT_8") (pintype "bidirectional"))
    )
    (net (code "192") (name "Net-(SD1-CP1)") (class "Default")
      (node (ref "C35") (pin "1") (pinfunction "1_1") (pintype "passive"))
      (node (ref "SD1") (pin "16") (pinfunction "CP1_16") (pintype "bidirectional"))
    )
    (net (code "193") (name "Net-(SD1-CP2)") (class "Default")
      (node (ref "C35") (pin "2") (pinfunction "2_2") (pintype "passive"))
      (node (ref "SD1") (pin "15") (pinfunction "CP2_15") (pintype "bidirectional"))
    )
    (net (code "194") (name "Net-(SD1-ISET)") (class "Default")
      (node (ref "R35") (pin "1") (pinfunction "1_1") (pintype "passive"))
      (node (ref "SD1") (pin "3") (pinfunction "ISET_3") (pintype "bidirectional"))
    )
    (net (code "195") (name "Net-(SD1-ROSC)") (class "Default")
      (node (ref "R3") (pin "2") (pinfunction "2_2") (pintype "passive"))
      (node (ref "SD1") (pin "5") (pinfunction "ROSC_5") (pintype "bidirectional"))
    )
    (net (code "196") (name "Net-(SD1-VCP)") (class "Default")
      (node (ref "C36") (pin "2") (pinfunction "2_2") (pintype "passive"))
      (node (ref "SD1") (pin "14") (pinfunction "VCP_14") (pintype "bidirectional"))
    )
    (net (code "197") (name "Net-(SD1-VG)") (class "Default")
      (node (ref "C34") (pin "1") (pinfunction "1_1") (pintype "passive"))
      (node (ref "SD1") (pin "17") (pinfunction "VG_17") (pintype "bidirectional"))
    )
    (net (code "198") (name "Net-(SD1-~{FAULT})") (class "Default")
      (node (ref "R32") (pin "2") (pinfunction "2_2") (pintype "passive"))
      (node (ref "SD1") (pin "2") (pinfunction "~{FAULT}_2") (pintype "bidirectional"))
    )
    (net (code "199") (name "Net-(SD2-CP1)") (class "Default")
      (node (ref "C52") (pin "1") (pinfunction "1_1") (pintype "passive"))
      (node (ref "SD2") (pin "16") (pinfunction "CP1_16") (pintype "bidirectional"))
    )
    (net (code "200") (name "Net-(SD2-CP2)") (class "Default")
      (node (ref "C52") (pin "2") (pinfunction "2_2") (pintype "passive"))
      (node (ref "SD2") (pin "15") (pinfunction "CP2_15") (pintype "bidirectional"))
    )
    (net (code "201") (name "Net-(SD2-ISET)") (class "Default")
      (node (ref "R41") (pin "1") (pinfunction "1_1") (pintype "passive"))
      (node (ref "SD2") (pin "3") (pinfunction "ISET_3") (pintype "bidirectional"))
    )
    (net (code "202") (name "Net-(SD2-ROSC)") (class "Default")
      (node (ref "R2") (pin "2") (pinfunction "2_2") (pintype "passive"))
      (node (ref "SD2") (pin "5") (pinfunction "ROSC_5") (pintype "bidirectional"))
    )
    (net (code "203") (name "Net-(SD2-VCP)") (class "Default")
      (node (ref "C53") (pin "2") (pinfunction "2_2") (pintype "passive"))
      (node (ref "SD2") (pin "14") (pinfunction "VCP_14") (pintype "bidirectional"))
    )
    (net (code "204") (name "Net-(SD2-VG)") (class "Default")
      (node (ref "C51") (pin "1") (pinfunction "1_1") (pintype "passive"))
      (node (ref "SD2") (pin "17") (pinfunction "VG_17") (pintype "bidirectional"))
    )
    (net (code "205") (name "Net-(SD2-~{FAULT})") (class "Default")
      (node (ref "R38") (pin "2") (pinfunction "2_2") (pintype "passive"))
      (node (ref "SD2") (pin "2") (pinfunction "~{FAULT}_2") (pintype "bidirectional"))
    )
    (net (code "206") (name "Net-(SD3-CP1)") (class "Default")
      (node (ref "C58") (pin "1") (pinfunction "1_1") (pintype "passive"))
      (node (ref "SD3") (pin "16") (pinfunction "CP1_16") (pintype "bidirectional"))
    )
    (net (code "207") (name "Net-(SD3-CP2)") (class "Default")
      (node (ref "C58") (pin "2") (pinfunction "2_2") (pintype "passive"))
      (node (ref "SD3") (pin "15") (pinfunction "CP2_15") (pintype "bidirectional"))
    )
    (net (code "208") (name "Net-(SD3-ISET)") (class "Default")
      (node (ref "R46") (pin "1") (pinfunction "1_1") (pintype "passive"))
      (node (ref "SD3") (pin "3") (pinfunction "ISET_3") (pintype "bidirectional"))
    )
    (net (code "209") (name "Net-(SD3-ROSC)") (class "Default")
      (node (ref "R42") (pin "2") (pinfunction "2_2") (pintype "passive"))
      (node (ref "SD3") (pin "5") (pinfunction "ROSC_5") (pintype "bidirectional"))
    )
    (net (code "210") (name "Net-(SD3-VCP)") (class "Default")
      (node (ref "C59") (pin "2") (pinfunction "2_2") (pintype "passive"))
      (node (ref "SD3") (pin "14") (pinfunction "VCP_14") (pintype "bidirectional"))
    )
    (net (code "211") (name "Net-(SD3-VG)") (class "Default")
      (node (ref "C57") (pin "1") (pinfunction "1_1") (pintype "passive"))
      (node (ref "SD3") (pin "17") (pinfunction "VG_17") (pintype "bidirectional"))
    )
    (net (code "212") (name "Net-(SD3-~{FAULT})") (class "Default")
      (node (ref "R43") (pin "2") (pinfunction "2_2") (pintype "passive"))
      (node (ref "SD3") (pin "2") (pinfunction "~{FAULT}_2") (pintype "bidirectional"))
    )
    (net (code "213") (name "Net-(STEPPER_0_CS-AOUT)") (class "Default")
      (node (ref "C19") (pin "1") (pinfunction "1_1") (pintype "passive"))
      (node (ref "R15") (pin "1") (pinfunction "1_1") (pintype "passive"))
      (node (ref "STEPPER_0_CS") (pin "4") (pinfunction "AOUT_4") (pintype "output"))
    )
    (net (code "214") (name "Net-(STEPPER_0_CS-VREF)") (class "Default")
      (node (ref "C24") (pin "1") (pinfunction "1_1") (pintype "passive"))
      (node (ref "R14") (pin "2") (pinfunction "2_2") (pintype "passive"))
      (node (ref "STEPPER_0_CS") (pin "3") (pinfunction "VREF_3") (pintype "bidirectional"))
    )
    (net (code "215") (name "Net-(STEPPER_1_CS-AOUT)") (class "Default")
      (node (ref "C25") (pin "1") (pinfunction "1_1") (pintype "passive"))
      (node (ref "R17") (pin "1") (pinfunction "1_1") (pintype "passive"))
      (node (ref "STEPPER_1_CS") (pin "4") (pinfunction "AOUT_4") (pintype "output"))
    )
    (net (code "216") (name "Net-(STEPPER_1_CS-VREF)") (class "Default")
      (node (ref "C27") (pin "1") (pinfunction "1_1") (pintype "passive"))
      (node (ref "R16") (pin "2") (pinfunction "2_2") (pintype "passive"))
      (node (ref "STEPPER_1_CS") (pin "3") (pinfunction "VREF_3") (pintype "bidirectional"))
    )
    (net (code "217") (name "Net-(U1-VDDCORE{slash}VCAP)") (class "Default")
      (node (ref "C7") (pin "1") (pinfunction "1_1") (pintype "passive"))
      (node (ref "U1") (pin "23") (pinfunction "VDDCORE/VCAP_23") (pintype "bidirectional"))
    )
    (net (code "218") (name "Net-(U5-CPOUT)") (class "Default")
      (node (ref "C46") (pin "2") (pinfunction "2_2") (pintype "passive"))
      (node (ref "U5") (pin "20") (pinfunction "CPOUT_20") (pintype "output"))
    )
    (net (code "219") (name "Net-(U5-REGOUT)") (class "Default")
      (node (ref "C47") (pin "1") (pinfunction "1_1") (pintype "passive"))
      (node (ref "U5") (pin "10") (pinfunction "REGOUT_10") (pintype "passive"))
    )
    (net (code "220") (name "PERIMETER_WIRE_SENSE") (class "Default")
      (node (ref "D2") (pin "A") (pinfunction "A_A") (pintype "passive"))
      (node (ref "PERIM") (pin "TP") (pinfunction "TP_TP") (pintype "input"))
      (node (ref "R4") (pin "1") (pinfunction "1_1") (pintype "passive"))
      (node (ref "U15") (pin "4") (pinfunction "AN19/CVD19/RPG6/PWM10L/PMA5/RG6_4") (pintype "bidirectional"))
    )
    (net (code "221") (name "STEP_DRV_0_A1") (class "Default")
      (node (ref "SD1") (pin "23") (pinfunction "AOUT1_23") (pintype "bidirectional"))
      (node (ref "STEPPER_0") (pin "1") (pinfunction "1_1") (pintype "passive"))
    )
    (net (code "222") (name "STEP_DRV_0_A2") (class "Default")
      (node (ref "SD1") (pin "21") (pinfunction "AOUT2_21") (pintype "bidirectional"))
      (node (ref "STEPPER_0") (pin "2") (pinfunction "2_2") (pintype "passive"))
    )
    (net (code "223") (name "STEP_DRV_0_B1") (class "Default")
      (node (ref "SD1") (pin "9") (pinfunction "BOUT1_9") (pintype "bidirectional"))
      (node (ref "STEPPER_0") (pin "3") (pinfunction "3_3") (pintype "passive"))
    )
    (net (code "224") (name "STEP_DRV_0_B2") (class "Default")
      (node (ref "SD1") (pin "11") (pinfunction "BOUT2_11") (pintype "bidirectional"))
      (node (ref "STEPPER_0") (pin "4") (pinfunction "4_4") (pintype "passive"))
    )
    (net (code "225") (name "STEP_DRV_0_FAULT") (class "Default")
      (node (ref "R32") (pin "1") (pinfunction "1_1") (pintype "passive"))
      (node (ref "R33") (pin "2") (pinfunction "2_2") (pintype "passive"))
    )
    (net (code "226") (name "STEP_DRV_0_SLEEP") (class "Default")
      (node (ref "R33") (pin "1") (pinfunction "1_1") (pintype "passive"))
      (node (ref "R34") (pin "2") (pinfunction "2_2") (pintype "passive"))
      (node (ref "SD1") (pin "19") (pinfunction "~{SLEEP}_19") (pintype "bidirectional"))
    )
    (net (code "227") (name "STEP_DRV_1_A1") (class "Default")
      (node (ref "SD2") (pin "23") (pinfunction "AOUT1_23") (pintype "bidirectional"))
      (node (ref "STEPPER_1") (pin "1") (pinfunction "1_1") (pintype "passive"))
    )
    (net (code "228") (name "STEP_DRV_1_A2") (class "Default")
      (node (ref "SD2") (pin "21") (pinfunction "AOUT2_21") (pintype "bidirectional"))
      (node (ref "STEPPER_1") (pin "2") (pinfunction "2_2") (pintype "passive"))
    )
    (net (code "229") (name "STEP_DRV_1_B1") (class "Default")
      (node (ref "SD2") (pin "9") (pinfunction "BOUT1_9") (pintype "bidirectional"))
      (node (ref "STEPPER_1") (pin "3") (pinfunction "3_3") (pintype "passive"))
    )
    (net (code "230") (name "STEP_DRV_1_B2") (class "Default")
      (node (ref "SD2") (pin "11") (pinfunction "BOUT2_11") (pintype "bidirectional"))
      (node (ref "STEPPER_1") (pin "4") (pinfunction "4_4") (pintype "passive"))
    )
    (net (code "231") (name "STEP_DRV_1_FAULT") (class "Default")
      (node (ref "R38") (pin "1") (pinfunction "1_1") (pintype "passive"))
      (node (ref "R39") (pin "2") (pinfunction "2_2") (pintype "passive"))
    )
    (net (code "232") (name "STEP_DRV_1_SLEEP") (class "Default")
      (node (ref "R39") (pin "1") (pinfunction "1_1") (pintype "passive"))
      (node (ref "R40") (pin "2") (pinfunction "2_2") (pintype "passive"))
      (node (ref "SD2") (pin "19") (pinfunction "~{SLEEP}_19") (pintype "bidirectional"))
    )
    (net (code "233") (name "STEP_DRV_2_A1") (class "Default")
      (node (ref "SD3") (pin "23") (pinfunction "AOUT1_23") (pintype "bidirectional"))
      (node (ref "STEPPER_2") (pin "1") (pinfunction "1_1") (pintype "passive"))
    )
    (net (code "234") (name "STEP_DRV_2_A2") (class "Default")
      (node (ref "SD3") (pin "21") (pinfunction "AOUT2_21") (pintype "bidirectional"))
      (node (ref "STEPPER_2") (pin "2") (pinfunction "2_2") (pintype "passive"))
    )
    (net (code "235") (name "STEP_DRV_2_B1") (class "Default")
      (node (ref "SD3") (pin "9") (pinfunction "BOUT1_9") (pintype "bidirectional"))
      (node (ref "STEPPER_2") (pin "3") (pinfunction "3_3") (pintype "passive"))
    )
    (net (code "236") (name "STEP_DRV_2_B2") (class "Default")
      (node (ref "SD3") (pin "11") (pinfunction "BOUT2_11") (pintype "bidirectional"))
      (node (ref "STEPPER_2") (pin "4") (pinfunction "4_4") (pintype "passive"))
    )
    (net (code "237") (name "STEP_DRV_2_FAULT") (class "Default")
      (node (ref "R43") (pin "1") (pinfunction "1_1") (pintype "passive"))
      (node (ref "R44") (pin "2") (pinfunction "2_2") (pintype "passive"))
    )
    (net (code "238") (name "STEP_DRV_2_SLEEP") (class "Default")
      (node (ref "R44") (pin "1") (pinfunction "1_1") (pintype "passive"))
      (node (ref "R45") (pin "2") (pinfunction "2_2") (pintype "passive"))
      (node (ref "SD3") (pin "19") (pinfunction "~{SLEEP}_19") (pintype "bidirectional"))
    )
    (net (code "239") (name "VBUS") (class "Default")
      (node (ref "U15") (pin "34") (pinfunction "VBUS_34") (pintype "power_in"))
    )
    (net (code "240") (name "unconnected-(CAMERA-Pad2)") (class "Default")
      (node (ref "CAMERA") (pin "2") (pinfunction "2_2") (pintype "passive"))
    )
    (net (code "241") (name "unconnected-(CP2102-DTR-Pad28)") (class "Default")
      (node (ref "CP2102") (pin "28") (pinfunction "DTR_28") (pintype "output"))
    )
    (net (code "242") (name "unconnected-(CP2102-RTS-Pad24)") (class "Default")
      (node (ref "CP2102") (pin "24") (pinfunction "RTS_24") (pintype "output"))
    )
    (net (code "243") (name "unconnected-(CURRENT_SENSOR_BATT-OCD1-Pad5)") (class "Default")
      (node (ref "CURRENT_SENSOR_BATT") (pin "5") (pinfunction "OCD1_5") (pintype "output"))
    )
    (net (code "244") (name "unconnected-(CURRENT_SENSOR_BATT-OCD2-Pad6)") (class "Default")
      (node (ref "CURRENT_SENSOR_BATT") (pin "6") (pinfunction "OCD2_6") (pintype "output"))
    )
    (net (code "245") (name "unconnected-(H1-MOUNT-PadB3,0)") (class "Default")
      (node (ref "H1") (pin "B3,0") (pinfunction "MOUNT_B3,0") (pintype "passive"))
    )
    (net (code "246") (name "unconnected-(H2-MOUNT-PadB3,0)") (class "Default")
      (node (ref "H2") (pin "B3,0") (pinfunction "MOUNT_B3,0") (pintype "passive"))
    )
    (net (code "247") (name "unconnected-(H3-MOUNT-PadB3,0)") (class "Default")
      (node (ref "H3") (pin "B3,0") (pinfunction "MOUNT_B3,0") (pintype "passive"))
    )
    (net (code "248") (name "unconnected-(H4-MOUNT-PadB3,0)") (class "Default")
      (node (ref "H4") (pin "B3,0") (pinfunction "MOUNT_B3,0") (pintype "passive"))
    )
    (net (code "249") (name "unconnected-(H5-MOUNT-PadB3,0)") (class "Default")
      (node (ref "H5") (pin "B3,0") (pinfunction "MOUNT_B3,0") (pintype "passive"))
    )
    (net (code "250") (name "unconnected-(H6-MOUNT-PadB3,0)") (class "Default")
      (node (ref "H6") (pin "B3,0") (pinfunction "MOUNT_B3,0") (pintype "passive"))
    )
    (net (code "251") (name "unconnected-(LIDAR-Pad3)") (class "Default")
      (node (ref "LIDAR") (pin "3") (pinfunction "3_3") (pintype "passive"))
    )
    (net (code "252") (name "unconnected-(LIDAR-Pad6)") (class "Default")
      (node (ref "LIDAR") (pin "6") (pinfunction "6_6") (pintype "passive"))
    )
    (net (code "253") (name "unconnected-(LIDAR-Pad8)") (class "Default")
      (node (ref "LIDAR") (pin "8") (pinfunction "8_8") (pintype "passive"))
    )
    (net (code "254") (name "unconnected-(MAIN_MOTOR_CS-OCD1-Pad5)") (class "Default")
      (node (ref "MAIN_MOTOR_CS") (pin "5") (pinfunction "OCD1_5") (pintype "output"))
    )
    (net (code "255") (name "unconnected-(MAIN_MOTOR_CS-OCD2-Pad6)") (class "Default")
      (node (ref "MAIN_MOTOR_CS") (pin "6") (pinfunction "OCD2_6") (pintype "output"))
    )
    (net (code "256") (name "unconnected-(MCU_0-NC1-PadA)") (class "Default")
      (node (ref "MCU_0") (pin "A") (pinfunction "NC1_A") (pintype "bidirectional"))
    )
    (net (code "257") (name "unconnected-(MCU_0-NC2-PadB)") (class "Default")
      (node (ref "MCU_0") (pin "B") (pinfunction "NC2_B") (pintype "bidirectional"))
    )
    (net (code "258") (name "unconnected-(MCU_1-NC1-PadA)") (class "Default")
      (node (ref "MCU_1") (pin "A") (pinfunction "NC1_A") (pintype "bidirectional"))
    )
    (net (code "259") (name "unconnected-(MCU_1-NC2-PadB)") (class "Default")
      (node (ref "MCU_1") (pin "B") (pinfunction "NC2_B") (pintype "bidirectional"))
    )
    (net (code "260") (name "unconnected-(MCU_2-NC1-PadA)") (class "Default")
      (node (ref "MCU_2") (pin "A") (pinfunction "NC1_A") (pintype "bidirectional"))
    )
    (net (code "261") (name "unconnected-(MCU_2-NC2-PadB)") (class "Default")
      (node (ref "MCU_2") (pin "B") (pinfunction "NC2_B") (pintype "bidirectional"))
    )
    (net (code "262") (name "unconnected-(MCU_3_ESP32-CLK-Pad20)") (class "Default")
      (node (ref "MCU_3_ESP32") (pin "20") (pinfunction "CLK_20") (pintype "bidirectional"))
    )
    (net (code "263") (name "unconnected-(MCU_3_ESP32-CMD-Pad19)") (class "Default")
      (node (ref "MCU_3_ESP32") (pin "19") (pinfunction "CMD_19") (pintype "bidirectional"))
    )
    (net (code "264") (name "unconnected-(MCU_3_ESP32-SVN-Pad5)") (class "Default")
      (node (ref "MCU_3_ESP32") (pin "5") (pinfunction "SVN_5") (pintype "bidirectional"))
    )
    (net (code "265") (name "unconnected-(MCU_3_ESP32-SVP-Pad4)") (class "Default")
      (node (ref "MCU_3_ESP32") (pin "4") (pinfunction "SVP_4") (pintype "bidirectional"))
    )
    (net (code "266") (name "unconnected-(RTCC-CLKOUT-Pad5)") (class "Default")
      (node (ref "RTCC") (pin "5") (pinfunction "CLKOUT_5") (pintype "bidirectional"))
    )
    (net (code "267") (name "unconnected-(RTCC-NC-Pad9)") (class "Default")
      (node (ref "RTCC") (pin "9") (pinfunction "NC_9") (pintype "bidirectional"))
    )
    (net (code "268") (name "unconnected-(RTCC-NC-Pad10)") (class "Default")
      (node (ref "RTCC") (pin "10") (pinfunction "NC_10") (pintype "bidirectional"))
    )
    (net (code "269") (name "unconnected-(RTCC-~{INT_1}-Pad2)") (class "Default")
      (node (ref "RTCC") (pin "2") (pinfunction "~{INT_1}_2") (pintype "bidirectional"))
    )
    (net (code "270") (name "unconnected-(RTCC-~{INT_2}-Pad6)") (class "Default")
      (node (ref "RTCC") (pin "6") (pinfunction "~{INT_2}_6") (pintype "bidirectional"))
    )
    (net (code "271") (name "unconnected-(STEPPER_0_CS-OCD1-Pad5)") (class "Default")
      (node (ref "STEPPER_0_CS") (pin "5") (pinfunction "OCD1_5") (pintype "output"))
    )
    (net (code "272") (name "unconnected-(STEPPER_0_CS-OCD2-Pad6)") (class "Default")
      (node (ref "STEPPER_0_CS") (pin "6") (pinfunction "OCD2_6") (pintype "output"))
    )
    (net (code "273") (name "unconnected-(STEPPER_1_CS-OCD1-Pad5)") (class "Default")
      (node (ref "STEPPER_1_CS") (pin "5") (pinfunction "OCD1_5") (pintype "output"))
    )
    (net (code "274") (name "unconnected-(STEPPER_1_CS-OCD2-Pad6)") (class "Default")
      (node (ref "STEPPER_1_CS") (pin "6") (pinfunction "OCD2_6") (pintype "output"))
    )
    (net (code "275") (name "unconnected-(U1-NC-Pad34)") (class "Default")
      (node (ref "U1") (pin "34") (pinfunction "NC_34") (pintype "no_connect"))
    )
    (net (code "276") (name "unconnected-(U1-NC_2-Pad12)") (class "Default")
      (node (ref "U1") (pin "12") (pinfunction "NC_2_12") (pintype "no_connect"))
    )
    (net (code "277") (name "unconnected-(U1-NC_3-Pad13)") (class "Default")
      (node (ref "U1") (pin "13") (pinfunction "NC_3_13") (pintype "no_connect"))
    )
    (net (code "278") (name "unconnected-(U1-NC_4-Pad33)") (class "Default")
      (node (ref "U1") (pin "33") (pinfunction "NC_4_33") (pintype "no_connect"))
    )
    (net (code "279") (name "unconnected-(U1-OSC1{slash}CLKI{slash}RA7-Pad30)") (class "Default")
      (node (ref "U1") (pin "30") (pinfunction "OSC1/CLKI/RA7_30") (pintype "bidirectional"))
    )
    (net (code "280") (name "unconnected-(U1-OSC2{slash}CLKO{slash}RA6-Pad31)") (class "Default")
      (node (ref "U1") (pin "31") (pinfunction "OSC2/CLKO/RA6_31") (pintype "bidirectional"))
    )
    (net (code "281") (name "unconnected-(U1-RA3{slash}AN3{slash}C1INB{slash}VREF+-Pad22)") (class "Default")
      (node (ref "U1") (pin "22") (pinfunction "RA3/AN3/C1INB/VREF+_22") (pintype "bidirectional"))
    )
    (net (code "282") (name "unconnected-(U1-RB4{slash}CCP4{slash}PMA1{slash}KBI0{slash}RP7-Pad14)") (class "Default")
      (node (ref "U1") (pin "14") (pinfunction "RB4/CCP4/PMA1/KBI0/RP7_14") (pintype "bidirectional"))
    )
    (net (code "283") (name "unconnected-(U1-RC3{slash}SCK1{slash}SCL1{slash}RP14-Pad37)") (class "Default")
      (node (ref "U1") (pin "37") (pinfunction "RC3/SCK1/SCL1/RP14_37") (pintype "bidirectional"))
    )
    (net (code "284") (name "unconnected-(U1-RC4{slash}SDI1{slash}SDA1{slash}RP15-Pad42)") (class "Default")
      (node (ref "U1") (pin "42") (pinfunction "RC4/SDI1/SDA1/RP15_42") (pintype "bidirectional"))
    )
    (net (code "285") (name "unconnected-(U1-RC5{slash}SDO1{slash}RP16-Pad43)") (class "Default")
      (node (ref "U1") (pin "43") (pinfunction "RC5/SDO1/RP16_43") (pintype "bidirectional"))
    )
    (net (code "286") (name "unconnected-(U5-AUX_CL-Pad7)") (class "Default")
      (node (ref "U5") (pin "7") (pinfunction "AUX_CL_7") (pintype "bidirectional"))
    )
    (net (code "287") (name "unconnected-(U5-AUX_DA-Pad6)") (class "Default")
      (node (ref "U5") (pin "6") (pinfunction "AUX_DA_6") (pintype "bidirectional"))
    )
    (net (code "288") (name "unconnected-(U5-CLKIN-Pad1)") (class "Default")
      (node (ref "U5") (pin "1") (pinfunction "CLKIN_1") (pintype "input"))
    )
    (net (code "289") (name "unconnected-(U5-NC_2-Pad2)") (class "Default")
      (node (ref "U5") (pin "2") (pinfunction "NC_2_2") (pintype "passive"))
    )
    (net (code "290") (name "unconnected-(U5-NC_3-Pad3)") (class "Default")
      (node (ref "U5") (pin "3") (pinfunction "NC_3_3") (pintype "passive"))
    )
    (net (code "291") (name "unconnected-(U5-NC_4-Pad4)") (class "Default")
      (node (ref "U5") (pin "4") (pinfunction "NC_4_4") (pintype "passive"))
    )
    (net (code "292") (name "unconnected-(U5-NC_5-Pad5)") (class "Default")
      (node (ref "U5") (pin "5") (pinfunction "NC_5_5") (pintype "passive"))
    )
    (net (code "293") (name "unconnected-(U5-NC_14-Pad14)") (class "Default")
      (node (ref "U5") (pin "14") (pinfunction "NC_14_14") (pintype "passive"))
    )
    (net (code "294") (name "unconnected-(U5-NC_15-Pad15)") (class "Default")
      (node (ref "U5") (pin "15") (pinfunction "NC_15_15") (pintype "passive"))
    )
    (net (code "295") (name "unconnected-(U5-NC_16-Pad16)") (class "Default")
      (node (ref "U5") (pin "16") (pinfunction "NC_16_16") (pintype "passive"))
    )
    (net (code "296") (name "unconnected-(U5-NC_17-Pad17)") (class "Default")
      (node (ref "U5") (pin "17") (pinfunction "NC_17_17") (pintype "passive"))
    )
    (net (code "297") (name "unconnected-(U5-RESV_19-Pad19)") (class "Default")
      (node (ref "U5") (pin "19") (pinfunction "RESV_19_19") (pintype "passive"))
    )
    (net (code "298") (name "unconnected-(U5-RESV_21-Pad21)") (class "Default")
      (node (ref "U5") (pin "21") (pinfunction "RESV_21_21") (pintype "passive"))
    )
    (net (code "299") (name "unconnected-(U5-RESV_22-Pad22)") (class "Default")
      (node (ref "U5") (pin "22") (pinfunction "RESV_22_22") (pintype "passive"))
    )
    (net (code "300") (name "unconnected-(U15-AN10{slash}CVD10{slash}RPA12{slash}RA12-Pad11)") (class "Default")
      (node (ref "U15") (pin "11") (pinfunction "AN10/CVD10/RPA12/RA12_11") (pintype "bidirectional"))
    )
    (net (code "301") (name "unconnected-(U15-AN11{slash}CVD11{slash}C1IN2-{slash}FLT4{slash}PMA12{slash}RC11-Pad24)") (class "Default")
      (node (ref "U15") (pin "24") (pinfunction "AN11/CVD11/C1IN2-/FLT4/PMA12/RC11_24") (pintype "bidirectional"))
    )
    (net (code "302") (name "unconnected-(U15-AN14{slash}CVD14{slash}RPE14{slash}FLT7{slash}PMA1{slash}RE14-Pad29)") (class "Default")
      (node (ref "U15") (pin "29") (pinfunction "AN14/CVD14/RPE14/FLT7/PMA1/RE14_29") (pintype "bidirectional"))
    )
    (net (code "303") (name "unconnected-(U15-AN15{slash}CVD15{slash}RPE15{slash}FLT8{slash}PMA0{slash}RE15-Pad30)") (class "Default")
      (node (ref "U15") (pin "30") (pinfunction "AN15/CVD15/RPE15/FLT8/PMA0/RE15_30") (pintype "bidirectional"))
    )
    (net (code "304") (name "unconnected-(U15-AN16{slash}CVD16{slash}RPG9{slash}PMA2{slash}RG9-Pad8)") (class "Default")
      (node (ref "U15") (pin "8") (pinfunction "AN16/CVD16/RPG9/PMA2/RG9_8") (pintype "bidirectional"))
    )
    (net (code "305") (name "unconnected-(U15-AN17{slash}CVD17{slash}RPG8{slash}SDA1{slash}PMA3{slash}RG8-Pad6)") (class "Default")
      (node (ref "U15") (pin "6") (pinfunction "AN17/CVD17/RPG8/SDA1/PMA3/RG8_6") (pintype "bidirectional"))
    )
    (net (code "306") (name "unconnected-(U15-AN18{slash}CVD18{slash}RPG7{slash}PWM10H{slash}SCL1{slash}PMA4{slash}RG7-Pad5)") (class "Default")
      (node (ref "U15") (pin "5") (pinfunction "AN18/CVD18/RPG7/PWM10H/SCL1/PMA4/RG7_5") (pintype "bidirectional"))
    )
    (net (code "307") (name "unconnected-(U15-D+-Pad37)") (class "Default")
      (node (ref "U15") (pin "37") (pinfunction "D+_37") (pintype "bidirectional"))
    )
    (net (code "308") (name "unconnected-(U15-D--Pad36)") (class "Default")
      (node (ref "U15") (pin "36") (pinfunction "D-_36") (pintype "bidirectional"))
    )
    (net (code "309") (name "unconnected-(U15-DAC2{slash}AN48{slash}CVD48{slash}RPC10{slash}PMA14{slash}PMCS{slash}RC10-Pad45)") (class "Default")
      (node (ref "U15") (pin "45") (pinfunction "DAC2/AN48/CVD48/RPC10/PMA14/PMCS/RC10_45") (pintype "bidirectional"))
    )
    (net (code "310") (name "unconnected-(U15-FLT15{slash}RPB4{slash}SCL2{slash}PMA8{slash}RB4-Pad32)") (class "Default")
      (node (ref "U15") (pin "32") (pinfunction "FLT15/RPB4/SCL2/PMA8/RB4_32") (pintype "bidirectional"))
    )
    (net (code "311") (name "unconnected-(U15-OA2IN+{slash}AN1{slash}C2IN1+{slash}RPA1{slash}RA1-Pad14)") (class "Default")
      (node (ref "U15") (pin "14") (pinfunction "OA2IN+/AN1/C2IN1+/RPA1/RA1_14") (pintype "bidirectional"))
    )
    (net (code "312") (name "unconnected-(U15-OA2OUT{slash}AN0{slash}C2IN4-{slash}C4IN3-{slash}RPA0{slash}RA0-Pad13)") (class "Default")
      (node (ref "U15") (pin "13") (pinfunction "OA2OUT/AN0/C2IN4-/C4IN3-/RPA0/RA0_13") (pintype "bidirectional"))
    )
    (net (code "313") (name "unconnected-(U15-OA3IN+{slash}AN8{slash}CVD8{slash}C3IN1+{slash}C3IN3-{slash}RPC2{slash}FLT3{slash}PMA13{slash}RC2-Pad23)") (class "Default")
      (node (ref "U15") (pin "23") (pinfunction "OA3IN+/AN8/CVD8/C3IN1+/C3IN3-/RPC2/FLT3/PMA13/RC2_23") (pintype "bidirectional"))
    )
    (net (code "314") (name "unconnected-(U15-OSCI{slash}CLKI{slash}AN49{slash}CVD49{slash}RPC12{slash}RC12-Pad39)") (class "Default")
      (node (ref "U15") (pin "39") (pinfunction "OSCI/CLKI/AN49/CVD49/RPC12/RC12_39") (pintype "bidirectional"))
    )
    (net (code "315") (name "unconnected-(U15-PGC2{slash}RPB6{slash}SCL3{slash}SCK2{slash}PMA15{slash}RB6-Pad44)") (class "Default")
      (node (ref "U15") (pin "44") (pinfunction "PGC2/RPB6/SCL3/SCK2/PMA15/RB6_44") (pintype "bidirectional"))
    )
    (net (code "316") (name "unconnected-(U15-PGC3{slash}OA1OUT{slash}VREF+{slash}AN3{slash}C1IN4-{slash}C4IN2-{slash}RPB1{slash}CTED1{slash}PMA6{slash}RB1-Pad16)") (class "Default")
      (node (ref "U15") (pin "16") (pinfunction "PGC3/OA1OUT/VREF+/AN3/C1IN4-/C4IN2-/RPB1/CTED1/PMA6/RB1_16") (pintype "bidirectional"))
    )
    (net (code "317") (name "unconnected-(U15-PGD3{slash}VREF-{slash}OA2IN-{slash}AN2{slash}C2IN1-{slash}RPB0{slash}CTED2{slash}RB0-Pad15)") (class "Default")
      (node (ref "U15") (pin "15") (pinfunction "PGD3/VREF-/OA2IN-/AN2/C2IN1-/RPB0/CTED2/RB0_15") (pintype "bidirectional"))
    )
    (net (code "318") (name "unconnected-(U15-RPB11{slash}PWM9H{slash}PWM3L{slash}PMD1{slash}RB11-Pad61)") (class "Default")
      (node (ref "U15") (pin "61") (pinfunction "RPB11/PWM9H/PWM3L/PMD1/RB11_61") (pintype "bidirectional"))
    )
    (net (code "319") (name "unconnected-(U15-RPB12{slash}PWM2H{slash}PMD2{slash}RB12-Pad62)") (class "Default")
      (node (ref "U15") (pin "62") (pinfunction "RPB12/PWM2H/PMD2/RB12_62") (pintype "bidirectional"))
    )
    (net (code "320") (name "unconnected-(U15-RPB13{slash}PWM8H{slash}PWM2L{slash}CTPLS{slash}PMD3{slash}RB13-Pad63)") (class "Default")
      (node (ref "U15") (pin "63") (pinfunction "RPB13/PWM8H/PWM2L/CTPLS/PMD3/RB13_63") (pintype "bidirectional"))
    )
    (net (code "321") (name "unconnected-(U15-RPB15{slash}PWM7H{slash}PWM1L{slash}PMD7{slash}RB15-Pad3)") (class "Default")
      (node (ref "U15") (pin "3") (pinfunction "RPB15/PWM7H/PWM1L/PMD7/RB15_3") (pintype "bidirectional"))
    )
    (net (code "322") (name "unconnected-(U15-RPC9{slash}PWM11H{slash}PWM5L{slash}RC9-Pad55)") (class "Default")
      (node (ref "U15") (pin "55") (pinfunction "RPC9/PWM11H/PWM5L/RC9_55") (pintype "bidirectional"))
    )
    (net (code "323") (name "unconnected-(U15-RPF0{slash}PWM11H{slash}RF0-Pad58)") (class "Default")
      (node (ref "U15") (pin "58") (pinfunction "RPF0/PWM11H/RF0_58") (pintype "bidirectional"))
    )
    (net (code "324") (name "unconnected-(U15-RPF1{slash}PWM11L{slash}RF1-Pad59)") (class "Default")
      (node (ref "U15") (pin "59") (pinfunction "RPF1/PWM11L/RF1_59") (pintype "bidirectional"))
    )
    (net (code "325") (name "unconnected-(U15-SOSCI{slash}RPC13{slash}RC13-Pad47)") (class "Default")
      (node (ref "U15") (pin "47") (pinfunction "SOSCI/RPC13/RC13_47") (pintype "bidirectional"))
    )
    (net (code "326") (name "unconnected-(U15-SOSCO{slash}T1CK{slash}RPB8{slash}RB8-Pad48)") (class "Default")
      (node (ref "U15") (pin "48") (pinfunction "SOSCO/T1CK/RPB8/RB8_48") (pintype "bidirectional"))
    )
    (net (code "327") (name "unconnected-(U15-TDI{slash}DAC3{slash}AN26{slash}CVD26{slash}RPA8{slash}SDA2{slash}PMA9{slash}RA8-Pad31)") (class "Default")
      (node (ref "U15") (pin "31") (pinfunction "TDI/DAC3/AN26/CVD26/RPA8/SDA2/PMA9/RA8_31") (pintype "bidirectional"))
    )
    (net (code "328") (name "unconnected-(U15-TDO{slash}PWM4H{slash}PMD4{slash}RA10-Pad64)") (class "Default")
      (node (ref "U15") (pin "64") (pinfunction "TDO/PWM4H/PMD4/RA10_64") (pintype "bidirectional"))
    )
    (net (code "329") (name "unconnected-(U15-TMS{slash}OA5IN-{slash}AN27{slash}CVD27{slash}LVDIN{slash}C5IN1-{slash}RPB9{slash}RB9-Pad49)") (class "Default")
      (node (ref "U15") (pin "49") (pinfunction "TMS/OA5IN-/AN27/CVD27/LVDIN/C5IN1-/RPB9/RB9_49") (pintype "bidirectional"))
    )
    (net (code "330") (name "unconnected-(U15-TRCLK{slash}RPC6{slash}PWM6H{slash}RC6-Pad50)") (class "Default")
      (node (ref "U15") (pin "50") (pinfunction "TRCLK/RPC6/PWM6H/RC6_50") (pintype "bidirectional"))
    )
    (net (code "331") (name "~{CP_SUSPEND}") (class "Default")
      (node (ref "CP2102") (pin "11") (pinfunction "~{SUSPEND}_11") (pintype "output"))
      (node (ref "R49") (pin "2") (pinfunction "2_2") (pintype "passive"))
    )
  )
)
